# STM32-PROX.net
KiCad netlist of a schematic drawn in EAGLE
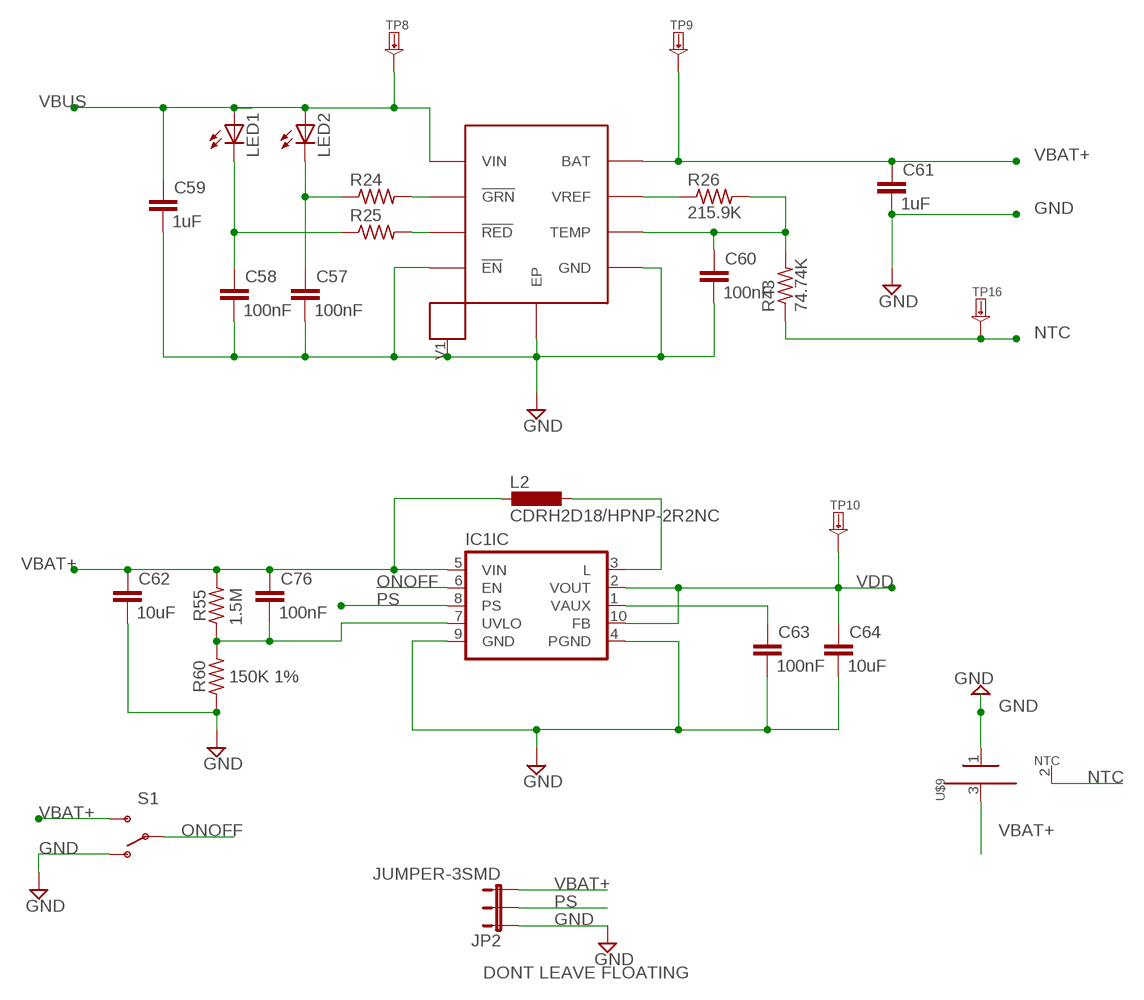
[diagram p0: schematic, sheet 1]
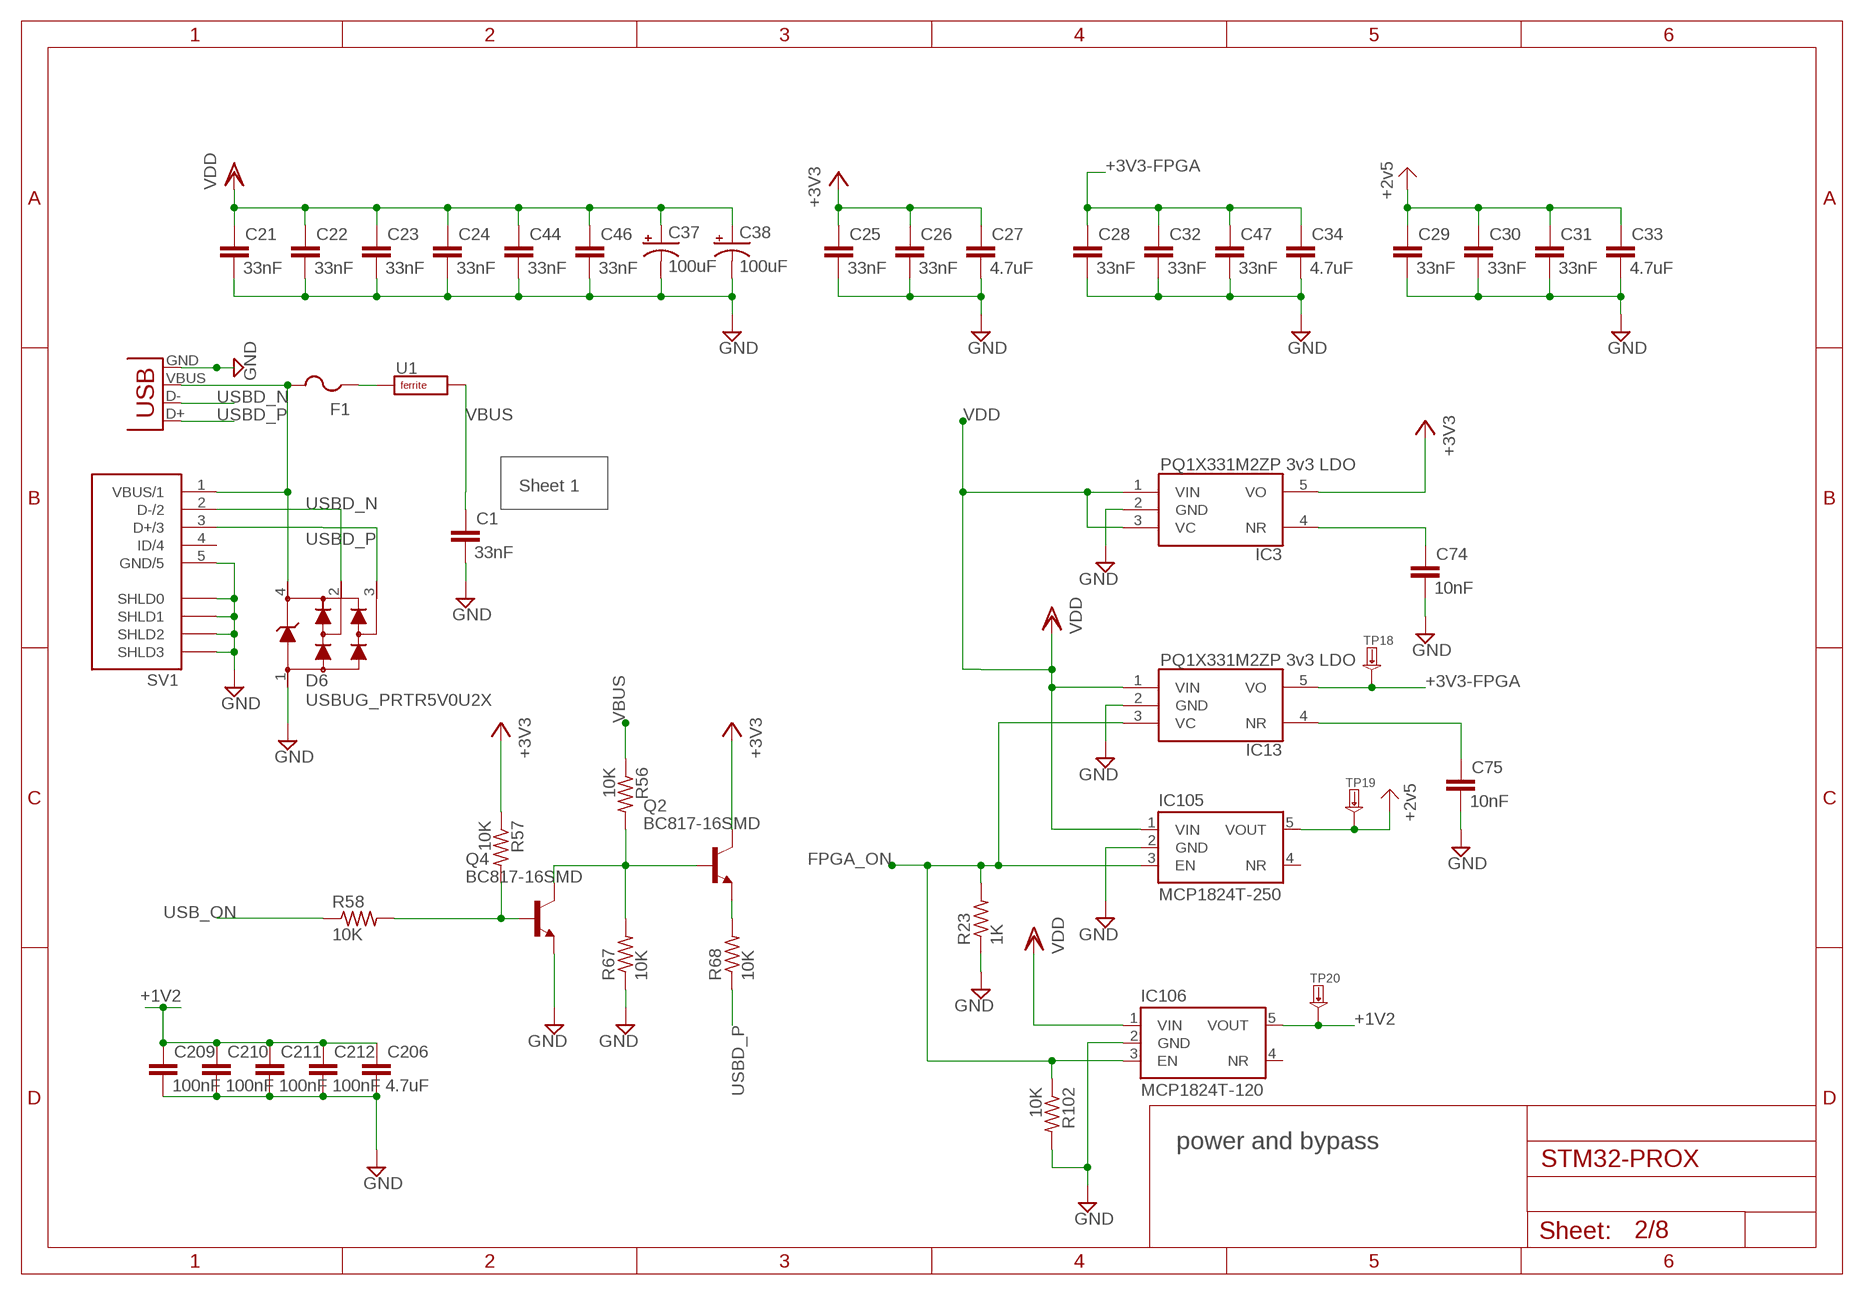
[diagram p1: schematic, sheet 2]
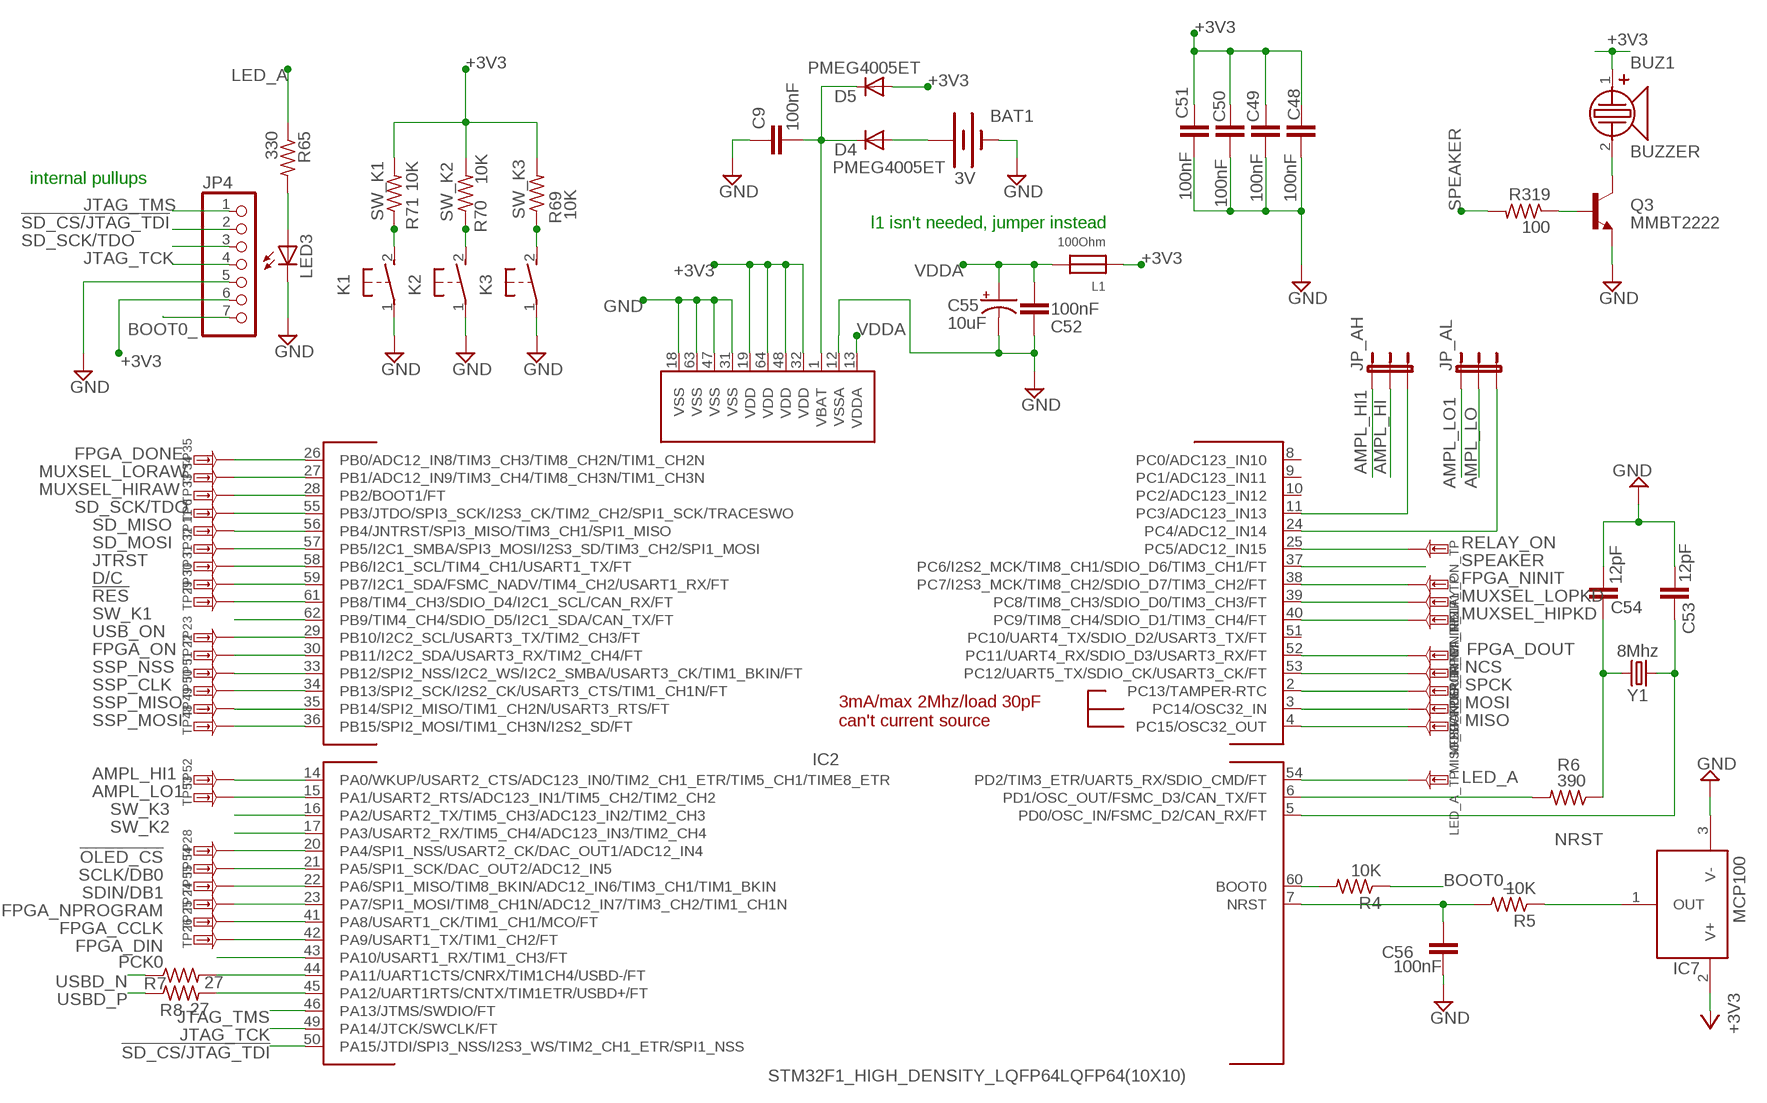
[diagram p2: schematic, sheet 3]
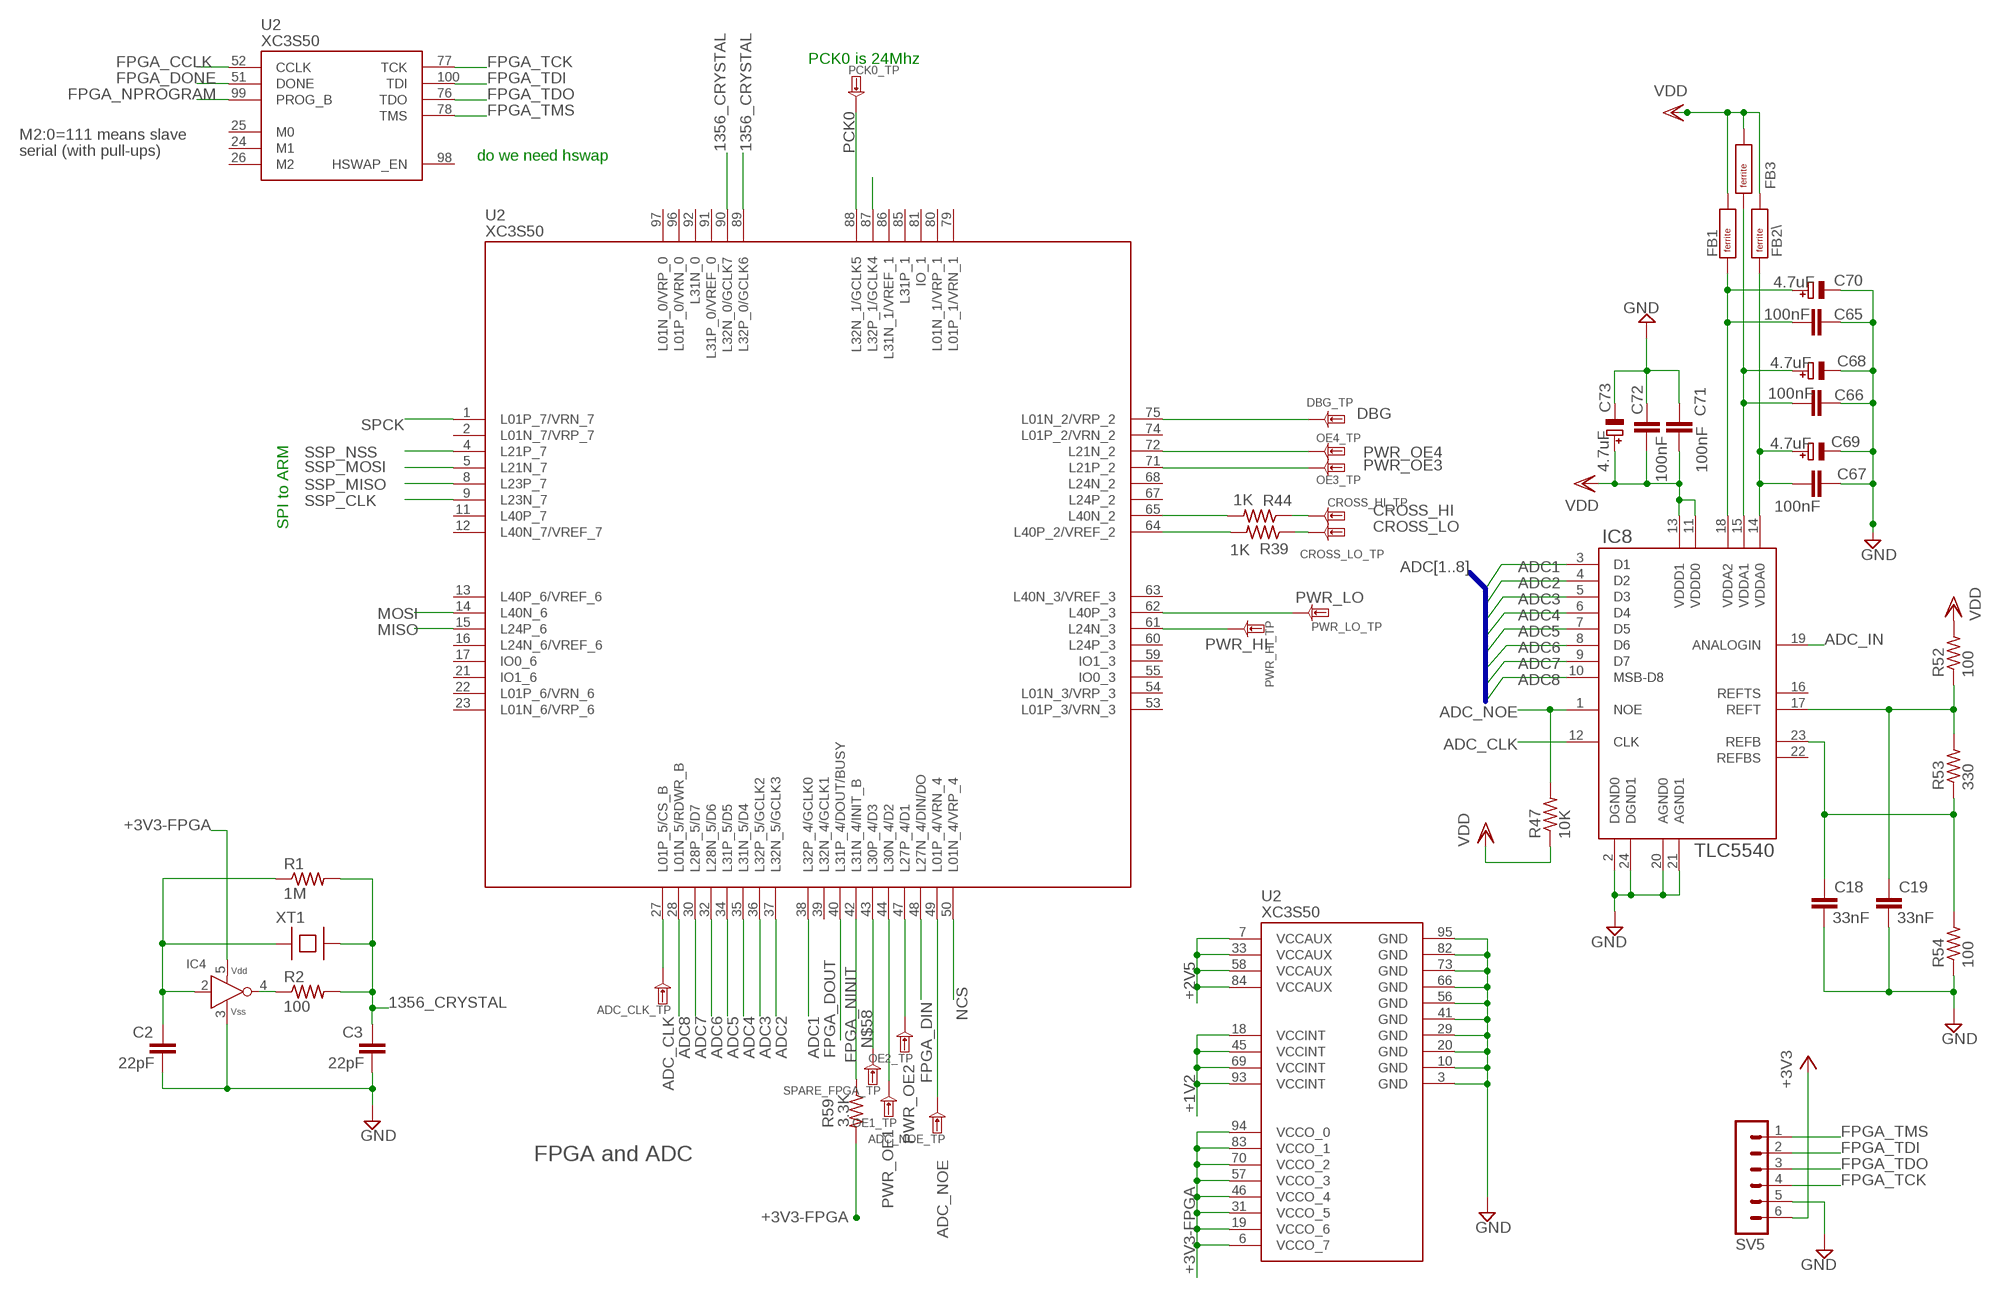
[diagram p3: schematic, sheet 4]
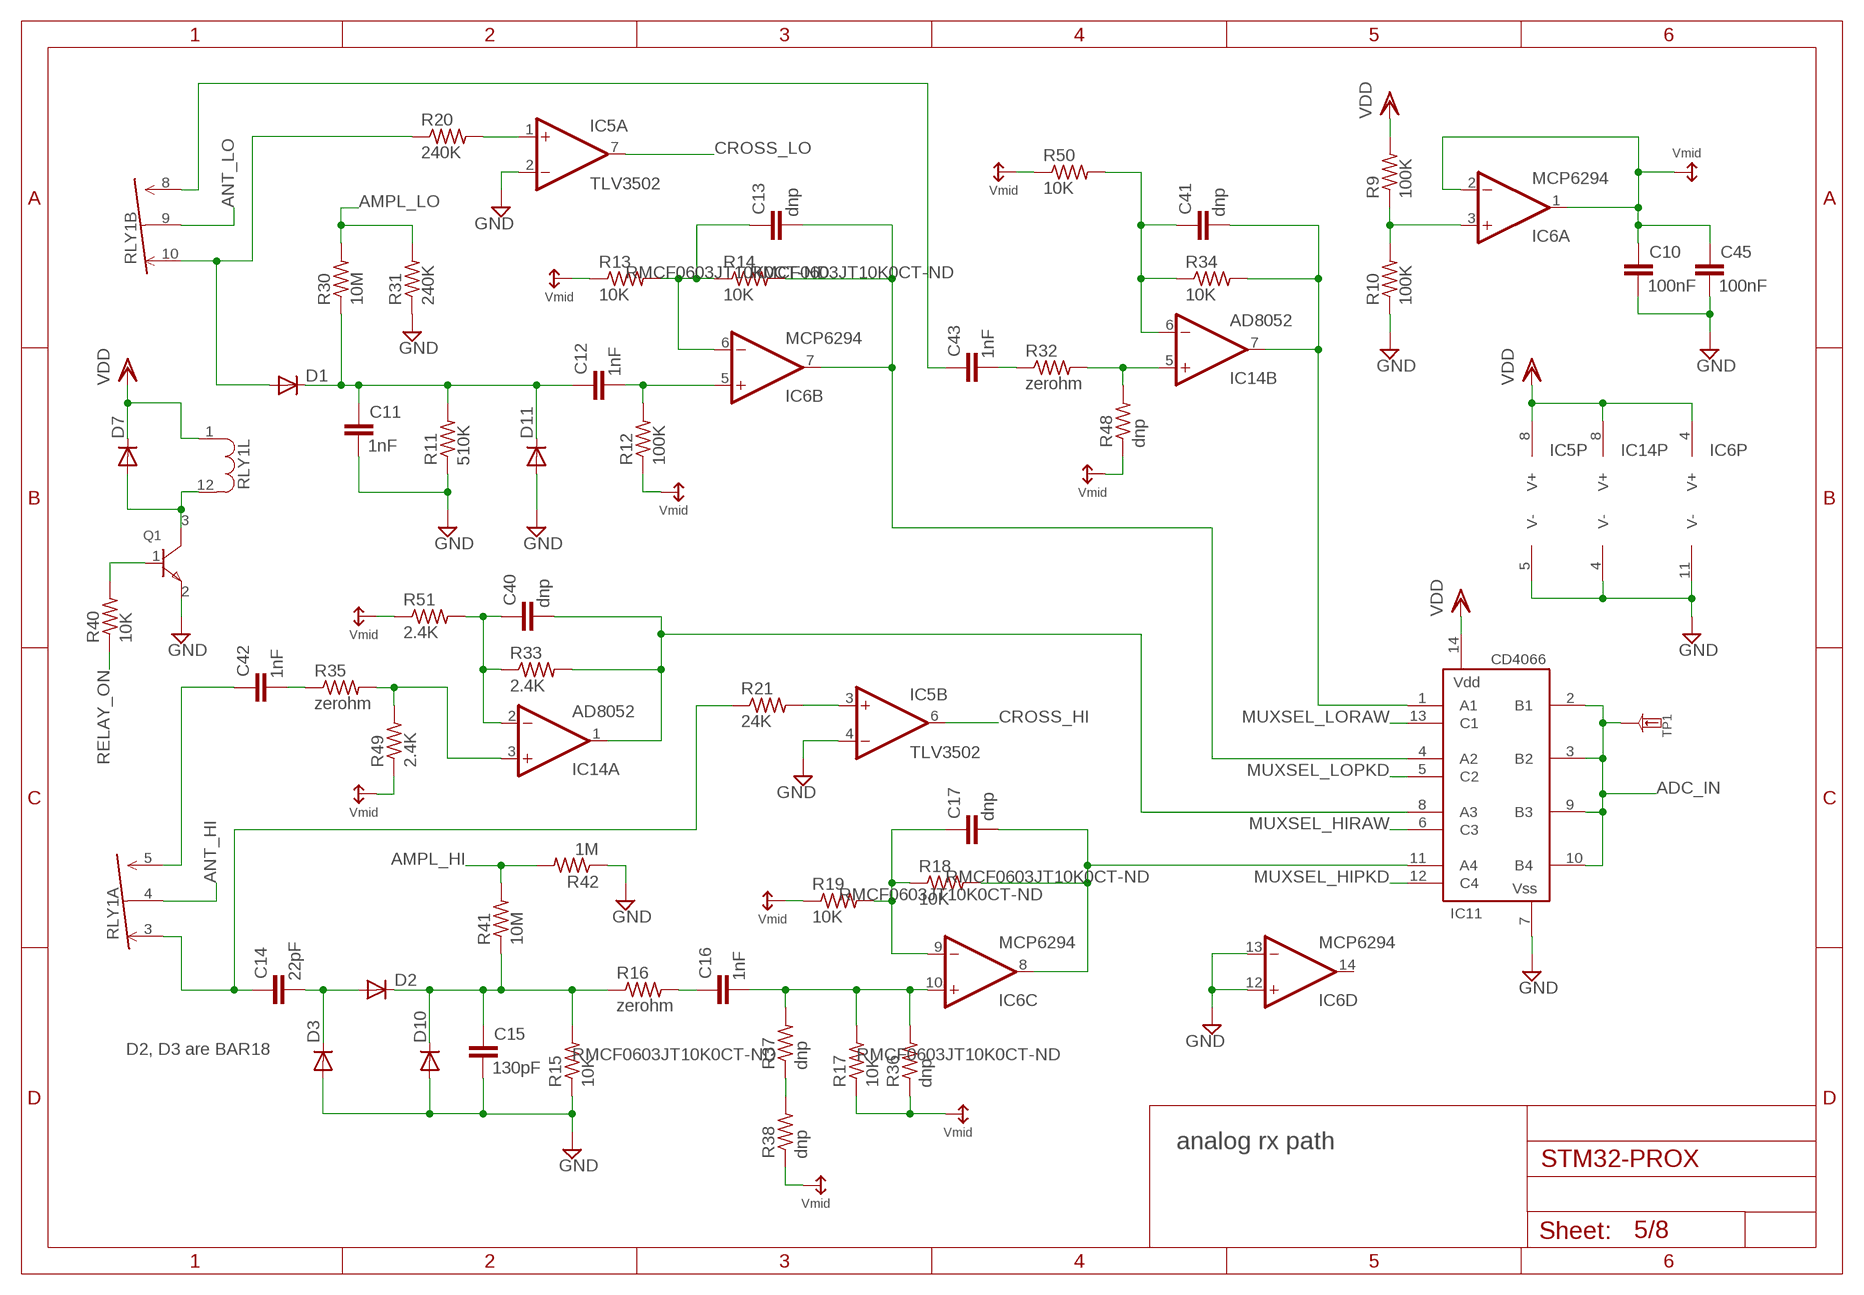
[diagram p4: schematic, sheet 5]
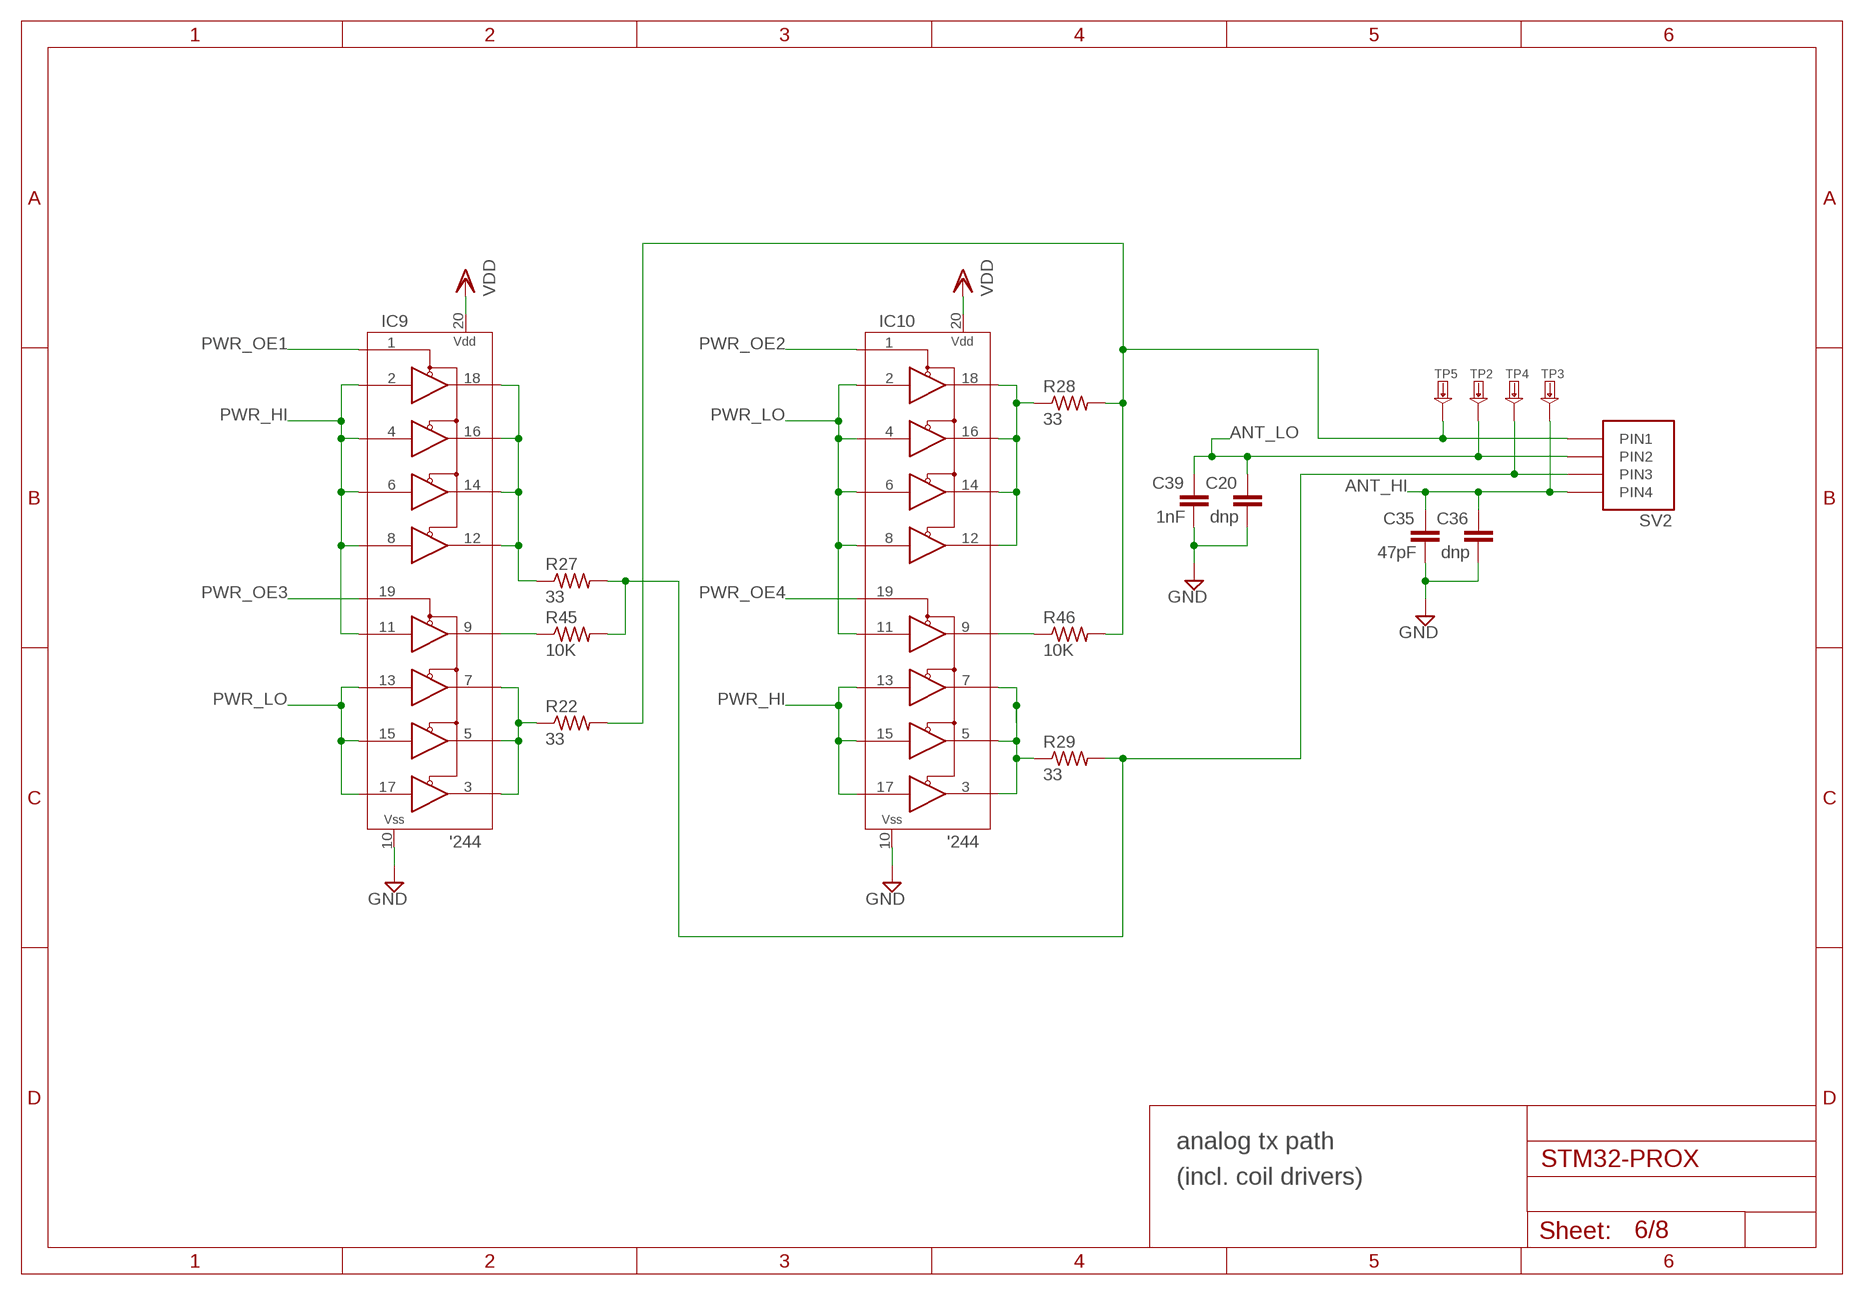
[diagram p5: schematic, sheet 6]
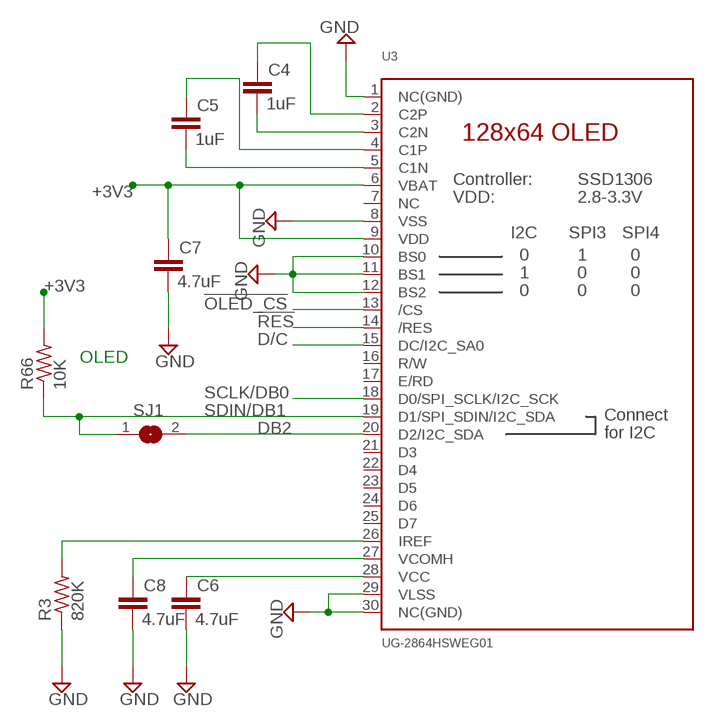
[diagram p6: schematic, sheet 7]
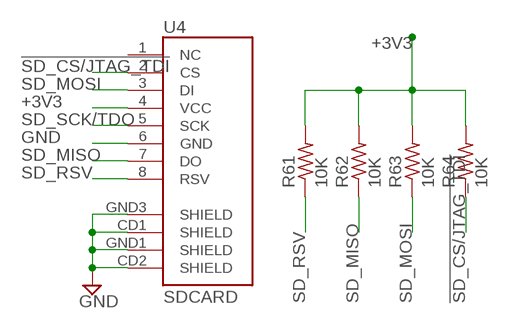
[diagram p7: schematic, sheet 8]

(export (version "E")
  (design (tool "Eeschema 10.0.6"))
  (components
    (comp (ref "C57")
      (value "100nF")
      (footprint "eagle-import:RLC_0603")
      (fields (field (name "MPN") "CL10B104KO8NNNC"))
      (libsource (lib "eagle-import") (part "CAPACITORRLC_0603"))
    )
    (comp (ref "C58")
      (value "100nF")
      (footprint "eagle-import:RLC_0603")
      (fields (field (name "MPN") "CL10B104KO8NNNC"))
      (libsource (lib "eagle-import") (part "CAPACITORRLC_0603"))
    )
    (comp (ref "C59")
      (value "1uF")
      (footprint "eagle-import:RLC_0603")
      (fields (field (name "MPN") "CC0603ZRY5V7BB105"))
      (libsource (lib "eagle-import") (part "CAPACITORRLC_0603"))
    )
    (comp (ref "C60")
      (value "100nF")
      (footprint "eagle-import:RLC_0603")
      (fields (field (name "MPN") "CL10B104KO8NNNC"))
      (libsource (lib "eagle-import") (part "CAPACITORRLC_0603"))
    )
    (comp (ref "C61")
      (value "1uF")
      (footprint "eagle-import:RLC_0603")
      (fields (field (name "MPN") "CC0603ZRY5V7BB105"))
      (libsource (lib "eagle-import") (part "CAPACITORRLC_0603"))
    )
    (comp (ref "C62")
      (value "10uF")
      (footprint "eagle-import:RLC_0603")
      (fields (field (name "MPN") "C1608X5R1C106M080AB"))
      (libsource (lib "eagle-import") (part "CAPACITORRLC_0603"))
    )
    (comp (ref "C63")
      (value "100nF")
      (footprint "eagle-import:RLC_0603")
      (fields (field (name "MPN") "CL10B104KO8NNNC"))
      (libsource (lib "eagle-import") (part "CAPACITORRLC_0603"))
    )
    (comp (ref "C64")
      (value "10uF")
      (footprint "eagle-import:RLC_0603")
      (fields (field (name "MPN") "C1608X5R1C106M080AB"))
      (libsource (lib "eagle-import") (part "CAPACITORRLC_0603"))
    )
    (comp (ref "C76")
      (value "100nF")
      (footprint "eagle-import:RLC_0603")
      (fields (field (name "MPN") "CL10B104KO8NNNC"))
      (libsource (lib "eagle-import") (part "CAPACITORRLC_0603"))
    )
    (comp (ref "IC1")
      (value "IC_TPS6120XQFN10")
      (footprint "eagle-import:QFN-10")
      (fields (field (name "MPN") "TPS61202DRCT"))
      (libsource (lib "eagle-import") (part "IC_TPS6120XQFN10"))
    )
    (comp (ref "JP2")
      (value "JUMPER-3SMD")
      (footprint "eagle-import:SJ_3")
      (fields (field (name "MPN") "NONE"))
      (libsource (lib "eagle-import") (part "JUMPER-3SMD"))
    )
    (comp (ref "L2")
      (value "CDRH2D18/HPNP-2R2NC")
      (footprint "eagle-import:CDRH2D18")
      (libsource (lib "eagle-import") (part "CDRH2D18"))
    )
    (comp (ref "LED1")
      (value "LED_LEDSML0603")
      (footprint "eagle-import:LED_SML0603")
      (fields (field (name "MF") "LG Q971-KN-1"))
      (libsource (lib "eagle-import") (part "LED_LEDSML0603"))
    )
    (comp (ref "LED2")
      (value "LED_LEDSML0603")
      (footprint "eagle-import:LED_SML0603")
      (fields (field (name "MF") "LS Q971-KN-1"))
      (libsource (lib "eagle-import") (part "LED_LEDSML0603"))
    )
    (comp (ref "R24")
      (value "RESISTORRLC_0603")
      (footprint "eagle-import:RLC_0603@1")
      (libsource (lib "eagle-import") (part "RESISTORRLC_0603"))
    )
    (comp (ref "R25")
      (value "RESISTORRLC_0603")
      (footprint "eagle-import:RLC_0603@1")
      (libsource (lib "eagle-import") (part "RESISTORRLC_0603"))
    )
    (comp (ref "R26")
      (value "215.9K")
      (footprint "eagle-import:RLC_0603@1")
      (fields (field (name "MPN") "CRCW0603215KFKEA"))
      (libsource (lib "eagle-import") (part "RESISTORRLC_0603"))
    )
    (comp (ref "R43")
      (value "74.74K")
      (footprint "eagle-import:RLC_0603@1")
      (fields (field (name "MPN") "RMCF0603JT75K0"))
      (libsource (lib "eagle-import") (part "RESISTORRLC_0603"))
    )
    (comp (ref "R55")
      (value "1.5M")
      (footprint "eagle-import:RLC_0603@1")
      (fields (field (name "MPN") "ESR03EZPJ155") (field (name "TOLERANCE") "5%"))
      (libsource (lib "eagle-import") (part "RESISTORRLC_0603"))
    )
    (comp (ref "R60")
      (value "150K 1%")
      (footprint "eagle-import:RLC_0603@1")
      (fields (field (name "MPN") "ESR03EZPF1503") (field (name "TOLERANCE") "1%"))
      (libsource (lib "eagle-import") (part "RESISTORRLC_0603"))
    )
    (comp (ref "S1")
      (value "SWITCH-SPDT-SMD-A")
      (footprint "eagle-import:SWITCH-SPST-SMD-A")
      (libsource (lib "eagle-import") (part "SWITCH-SPDT-SMD-A"))
    )
    (comp (ref "TP8")
      (value "TESTPAD0.7MM-ROUND-DRILLED")
      (footprint "eagle-import:TESTPAD-PTH-0.7MM")
      (fields (field (name "MPN") "NONE"))
      (libsource (lib "eagle-import") (part "TESTPAD0.7MM-ROUND-DRILLED"))
    )
    (comp (ref "TP9")
      (value "TESTPADKEYSTONE-SMD")
      (footprint "eagle-import:--MERGED_KEYSTONE-SMD-TESTPOINT-5015")
      (fields (field (name "MPN") "NONE"))
      (libsource (lib "eagle-import") (part "--MERGED_TESTPADKEYSTONE-SMD"))
    )
    (comp (ref "TP10")
      (value "TESTPADKEYSTONE-SMD")
      (footprint "eagle-import:--MERGED_KEYSTONE-SMD-TESTPOINT-5015")
      (fields (field (name "MPN") "NONE"))
      (libsource (lib "eagle-import") (part "--MERGED_TESTPADKEYSTONE-SMD"))
    )
    (comp (ref "TP16")
      (value "TESTPAD")
      (footprint "eagle-import:SMD-TESTPOINT")
      (libsource (lib "eagle-import") (part "TESTPAD"))
    )
    (comp (ref "U$7")
      (value "MC34674")
      (footprint "eagle-import:UDFN-EP")
      (fields
        (field (name "DIGIKEY") "MC34674AEPR2TR-ND")
        (field (name "MF") "MC34674AEPR2")
        (field (name "MOUSER") "841-MC34674AEPR2")
        (field (name "MPN") "MC34674AEPR2")
        (field (name "OC_NEWARK") "unknown")
        (field (name "PARTNO") "MC34674AEPR2")
      )
      (libsource (lib "eagle-import") (part "MC34674"))
    )
    (comp (ref "U$9")
      (value "BATT")
      (footprint "eagle-import:BATT")
      (fields (field (name "MF") "MC34674AEPR2"))
      (libsource (lib "eagle-import") (part "BATT"))
    )
    (comp (ref "C1")
      (value "33nF")
      (footprint "eagle-import:RLC_0603")
      (fields (field (name "MPN") "CC0603KRX7R9BB333"))
      (libsource (lib "eagle-import") (part "CAPACITORRLC_0603"))
    )
    (comp (ref "C21")
      (value "33nF")
      (footprint "eagle-import:RLC_0603")
      (fields (field (name "MPN") "CC0603KRX7R9BB333"))
      (libsource (lib "eagle-import") (part "CAPACITORRLC_0603"))
    )
    (comp (ref "C22")
      (value "33nF")
      (footprint "eagle-import:RLC_0603")
      (fields (field (name "MPN") "CC0603KRX7R9BB333"))
      (libsource (lib "eagle-import") (part "CAPACITORRLC_0603"))
    )
    (comp (ref "C23")
      (value "33nF")
      (footprint "eagle-import:RLC_0603")
      (fields (field (name "MPN") "CC0603KRX7R9BB333"))
      (libsource (lib "eagle-import") (part "CAPACITORRLC_0603"))
    )
    (comp (ref "C24")
      (value "33nF")
      (footprint "eagle-import:RLC_0603")
      (fields (field (name "MPN") "CC0603KRX7R9BB333"))
      (libsource (lib "eagle-import") (part "CAPACITORRLC_0603"))
    )
    (comp (ref "C25")
      (value "33nF")
      (footprint "eagle-import:RLC_0603")
      (fields (field (name "MPN") "CC0603KRX7R9BB333"))
      (libsource (lib "eagle-import") (part "CAPACITORRLC_0603"))
    )
    (comp (ref "C26")
      (value "33nF")
      (footprint "eagle-import:RLC_0603")
      (fields (field (name "MPN") "CC0603KRX7R9BB333"))
      (libsource (lib "eagle-import") (part "CAPACITORRLC_0603"))
    )
    (comp (ref "C27")
      (value "4.7uF")
      (footprint "eagle-import:RLC_1210")
      (fields (field (name "MPN") "CL32B475KOINNNE"))
      (libsource (lib "eagle-import") (part "CAPACITOR1210"))
    )
    (comp (ref "C28")
      (value "33nF")
      (footprint "eagle-import:RLC_0603")
      (fields (field (name "MPN") "CC0603KRX7R9BB333"))
      (libsource (lib "eagle-import") (part "CAPACITORRLC_0603"))
    )
    (comp (ref "C29")
      (value "33nF")
      (footprint "eagle-import:RLC_0603")
      (fields (field (name "MPN") "CC0603KRX7R9BB333"))
      (libsource (lib "eagle-import") (part "CAPACITORRLC_0603"))
    )
    (comp (ref "C30")
      (value "33nF")
      (footprint "eagle-import:RLC_0603")
      (fields (field (name "MPN") "CC0603KRX7R9BB333"))
      (libsource (lib "eagle-import") (part "CAPACITORRLC_0603"))
    )
    (comp (ref "C31")
      (value "33nF")
      (footprint "eagle-import:RLC_0603")
      (fields (field (name "MPN") "CC0603KRX7R9BB333"))
      (libsource (lib "eagle-import") (part "CAPACITORRLC_0603"))
    )
    (comp (ref "C32")
      (value "33nF")
      (footprint "eagle-import:RLC_0603")
      (fields (field (name "MPN") "CC0603KRX7R9BB333"))
      (libsource (lib "eagle-import") (part "CAPACITORRLC_0603"))
    )
    (comp (ref "C33")
      (value "4.7uF")
      (footprint "eagle-import:RLC_1210")
      (fields (field (name "MPN") "CL32B475KOINNNE"))
      (libsource (lib "eagle-import") (part "CAPACITOR1210"))
    )
    (comp (ref "C34")
      (value "4.7uF")
      (footprint "eagle-import:RLC_1210")
      (fields (field (name "MPN") "CL32B475KOINNNE"))
      (libsource (lib "eagle-import") (part "CAPACITOR1210"))
    )
    (comp (ref "C37")
      (value "100uF")
      (footprint "eagle-import:D_7343-31R")
      (fields (field (name "MPN") "T491D107K010AT"))
      (libsource (lib "eagle-import") (part "CPOL-USD/7343-31R"))
    )
    (comp (ref "C38")
      (value "100uF")
      (footprint "eagle-import:D_7343-31R")
      (fields (field (name "MPN") "T491D107K010AT"))
      (libsource (lib "eagle-import") (part "CPOL-USD/7343-31R"))
    )
    (comp (ref "C44")
      (value "33nF")
      (footprint "eagle-import:RLC_0603")
      (fields (field (name "MPN") "CC0603KRX7R9BB333"))
      (libsource (lib "eagle-import") (part "CAPACITORRLC_0603"))
    )
    (comp (ref "C46")
      (value "33nF")
      (footprint "eagle-import:RLC_0603")
      (fields (field (name "MPN") "CC0603KRX7R9BB333"))
      (libsource (lib "eagle-import") (part "CAPACITORRLC_0603"))
    )
    (comp (ref "C47")
      (value "33nF")
      (footprint "eagle-import:RLC_0603")
      (fields (field (name "MPN") "CC0603KRX7R9BB333"))
      (libsource (lib "eagle-import") (part "CAPACITORRLC_0603"))
    )
    (comp (ref "C74")
      (value "10nF")
      (footprint "eagle-import:RLC_0603")
      (fields (field (name "MPN") "CC0603KRX7R9BB333"))
      (libsource (lib "eagle-import") (part "CAPACITORRLC_0603"))
    )
    (comp (ref "C75")
      (value "10nF")
      (footprint "eagle-import:RLC_0603")
      (fields (field (name "MPN") "CC0603KRX7R9BB333"))
      (libsource (lib "eagle-import") (part "CAPACITORRLC_0603"))
    )
    (comp (ref "C206")
      (value "4.7uF")
      (footprint "eagle-import:RLC_0603")
      (fields (field (name "MPN") "EMK107ABJ475KA-T"))
      (libsource (lib "eagle-import") (part "CAPACITORRLC_0603"))
    )
    (comp (ref "C209")
      (value "100nF")
      (footprint "eagle-import:RLC_0603")
      (fields (field (name "MPN") "CL10B104KO8NNNC"))
      (libsource (lib "eagle-import") (part "CAPACITORRLC_0603"))
    )
    (comp (ref "C210")
      (value "100nF")
      (footprint "eagle-import:RLC_0603")
      (fields (field (name "MPN") "CL10B104KO8NNNC"))
      (libsource (lib "eagle-import") (part "CAPACITORRLC_0603"))
    )
    (comp (ref "C211")
      (value "100nF")
      (footprint "eagle-import:RLC_0603")
      (fields (field (name "MPN") "CL10B104KO8NNNC"))
      (libsource (lib "eagle-import") (part "CAPACITORRLC_0603"))
    )
    (comp (ref "C212")
      (value "100nF")
      (footprint "eagle-import:RLC_0603")
      (fields (field (name "MPN") "CL10B104KO8NNNC"))
      (libsource (lib "eagle-import") (part "CAPACITORRLC_0603"))
    )
    (comp (ref "D6")
      (value "USBUG_PRTR5V0U2X")
      (footprint "eagle-import:USBUG_SOT143B")
      (libsource (lib "eagle-import") (part "USBUG_PRTR5V0U2X"))
    )
    (comp (ref "F1")
      (value "PTCFUSE-1812")
      (footprint "eagle-import:1812")
      (fields (field (name "MPN") "MICROSMD050F-2"))
      (libsource (lib "eagle-import") (part "PTCFUSE-1812"))
    )
    (comp (ref "IC3")
      (value "PQ1X331M2ZP-3V3-LDO-SOT-23-5")
      (footprint "eagle-import:SOT-23-5")
      (fields (field (name "MPN") "LP2985-33DBVR"))
      (libsource (lib "eagle-import") (part "PQ1X331M2ZP-3V3-LDO-SOT-23-5"))
    )
    (comp (ref "IC13")
      (value "PQ1X331M2ZP-3V3-LDO-SOT-23-5")
      (footprint "eagle-import:SOT-23-5")
      (fields (field (name "MPN") "LP2985-33DBVR"))
      (libsource (lib "eagle-import") (part "PQ1X331M2ZP-3V3-LDO-SOT-23-5"))
    )
    (comp (ref "IC105")
      (value "MCP1824T-250")
      (footprint "eagle-import:SOT-23-5")
      (fields (field (name "MPN") "MCP1824T-2502E/OT"))
      (libsource (lib "eagle-import") (part "TPS79925"))
    )
    (comp (ref "IC106")
      (value "MCP1824T-120")
      (footprint "eagle-import:SOT-23-5")
      (fields (field (name "MPN") "MCP1824T-1202E/OT"))
      (libsource (lib "eagle-import") (part "TPS79912"))
    )
    (comp (ref "Q2")
      (value "BC817-16SMD")
      (footprint "eagle-import:SOT23-BEC")
      (libsource (lib "eagle-import") (part "BC817SMD-16"))
    )
    (comp (ref "Q4")
      (value "BC817-16SMD")
      (footprint "eagle-import:SOT23-BEC")
      (libsource (lib "eagle-import") (part "BC817SMD-16"))
    )
    (comp (ref "R23")
      (value "1K")
      (footprint "eagle-import:RLC_0603@1")
      (fields (field (name "MPN") "RMCF0603JT1K00"))
      (libsource (lib "eagle-import") (part "RESISTORRLC_0603"))
    )
    (comp (ref "R56")
      (value "10K")
      (footprint "eagle-import:RLC_0603@1")
      (fields (field (name "MPN") "RMCF0603JT10K0"))
      (libsource (lib "eagle-import") (part "RESISTORRLC_0603"))
    )
    (comp (ref "R57")
      (value "10K")
      (footprint "eagle-import:RLC_0603@1")
      (fields (field (name "MPN") "RMCF0603JT10K0"))
      (libsource (lib "eagle-import") (part "RESISTORRLC_0603"))
    )
    (comp (ref "R58")
      (value "10K")
      (footprint "eagle-import:RLC_0603@1")
      (fields (field (name "MPN") "RMCF0603JT10K0"))
      (libsource (lib "eagle-import") (part "RESISTORRLC_0603"))
    )
    (comp (ref "R67")
      (value "10K")
      (footprint "eagle-import:RLC_0603@1")
      (fields (field (name "MPN") "RMCF0603JT10K0"))
      (libsource (lib "eagle-import") (part "RESISTORRLC_0603"))
    )
    (comp (ref "R68")
      (value "10K")
      (footprint "eagle-import:RLC_0603@1")
      (fields (field (name "MPN") "RMCF0603JT10K0"))
      (libsource (lib "eagle-import") (part "RESISTORRLC_0603"))
    )
    (comp (ref "R102")
      (value "10K")
      (footprint "eagle-import:RLC_0603@1")
      (fields (field (name "MPN") "RMCF0603JT10K0"))
      (libsource (lib "eagle-import") (part "RESISTORRLC_0603"))
    )
    (comp (ref "SV1")
      (value "USB-MINIB")
      (footprint "eagle-import:USB-MINIB-SMD")
      (libsource (lib "eagle-import") (part "USB-MINIB"))
    )
    (comp (ref "TP18")
      (value "TESTPAD")
      (footprint "eagle-import:SMD-TESTPOINT")
      (libsource (lib "eagle-import") (part "TESTPAD"))
    )
    (comp (ref "TP19")
      (value "TESTPAD")
      (footprint "eagle-import:SMD-TESTPOINT")
      (libsource (lib "eagle-import") (part "TESTPAD"))
    )
    (comp (ref "TP20")
      (value "TESTPAD")
      (footprint "eagle-import:SMD-TESTPOINT")
      (libsource (lib "eagle-import") (part "TESTPAD"))
    )
    (comp (ref "U1")
      (value "FERRITE0805")
      (footprint "eagle-import:RLC_0805")
      (fields (field (name "MF") "MPZ2012S300A"))
      (libsource (lib "eagle-import") (part "FERRITE0805"))
    )
    (comp (ref "USB-MICRO")
      (value "USB-MICROB")
      (footprint "eagle-import:USB-MICROB")
      (fields (field (name "MF") "1981568-1"))
      (libsource (lib "eagle-import") (part "USB-MICROB"))
    )
    (comp (ref "C4")
      (value "1uF")
      (footprint "eagle-import:RLC_0603")
      (fields (field (name "MPN") "CC0805ZRY5V8BB105"))
      (libsource (lib "eagle-import") (part "CAPACITORRLC_0603"))
    )
    (comp (ref "C5")
      (value "1uF")
      (footprint "eagle-import:RLC_0603")
      (fields (field (name "MPN") "CC0805ZRY5V8BB105"))
      (libsource (lib "eagle-import") (part "CAPACITORRLC_0603"))
    )
    (comp (ref "C6")
      (value "4.7uF")
      (footprint "eagle-import:RLC_0603")
      (fields (field (name "MPN") "CL21A475KOFNNNE"))
      (libsource (lib "eagle-import") (part "CAPACITORRLC_0603"))
    )
    (comp (ref "C7")
      (value "4.7uF")
      (footprint "eagle-import:RLC_0603")
      (fields (field (name "MPN") "CL21A475KOFNNNE"))
      (libsource (lib "eagle-import") (part "CAPACITORRLC_0603"))
    )
    (comp (ref "C8")
      (value "4.7uF")
      (footprint "eagle-import:RLC_0603")
      (fields (field (name "MPN") "CL21A475KOFNNNE"))
      (libsource (lib "eagle-import") (part "CAPACITORRLC_0603"))
    )
    (comp (ref "R3")
      (value "820K")
      (footprint "eagle-import:RLC_0603@1")
      (fields (field (name "MPN") "RC0603JR-07820KL"))
      (libsource (lib "eagle-import") (part "RESISTORRLC_0603"))
    )
    (comp (ref "R66")
      (value "10K")
      (footprint "eagle-import:RLC_0603@1")
      (fields (field (name "MPN") "RC0603JR-07820KL"))
      (libsource (lib "eagle-import") (part "RESISTORRLC_0603"))
    )
    (comp (ref "SJ1")
      (value "SOLDERJUMPERREFLOW")
      (footprint "eagle-import:SOLDERJUMPER_REFLOW")
      (fields (field (name "MPN") "NONE"))
      (libsource (lib "eagle-import") (part "SOLDERJUMPERREFLOW"))
    )
    (comp (ref "U3")
      (value "UG-2864HSWEG01")
      (footprint "eagle-import:MICROBUILDER_UG-2864HSWEG01_0.96IN_WRAPAROUND")
      (libsource (lib "eagle-import") (part "MICROBUILDER_DISP_OLED_UG-2864HSWEG010.96{dblquote}"))
    )
    (comp (ref "ADC_CLK_TP")
      (value "TESTPAD")
      (footprint "eagle-import:SMD-TESTPOINT")
      (libsource (lib "eagle-import") (part "TESTPAD"))
    )
    (comp (ref "ADC_NOE_TP")
      (value "TESTPAD")
      (footprint "eagle-import:SMD-TESTPOINT")
      (libsource (lib "eagle-import") (part "TESTPAD"))
    )
    (comp (ref "C2")
      (value "22pF")
      (footprint "eagle-import:RLC_0603")
      (fields (field (name "MPN") "C1608C0G1H220J080AA"))
      (libsource (lib "eagle-import") (part "CAPACITORRLC_0603"))
    )
    (comp (ref "C3")
      (value "22pF")
      (footprint "eagle-import:RLC_0603")
      (fields (field (name "MPN") "C1608C0G1H220J080AA"))
      (libsource (lib "eagle-import") (part "CAPACITORRLC_0603"))
    )
    (comp (ref "C18")
      (value "33nF")
      (footprint "eagle-import:RLC_0603")
      (fields (field (name "MPN") "CC0603KRX7R9BB333"))
      (libsource (lib "eagle-import") (part "CAPACITORRLC_0603"))
    )
    (comp (ref "C19")
      (value "33nF")
      (footprint "eagle-import:RLC_0603")
      (fields (field (name "MPN") "CC0603KRX7R9BB333"))
      (libsource (lib "eagle-import") (part "CAPACITORRLC_0603"))
    )
    (comp (ref "C65")
      (value "100nF")
      (footprint "eagle-import:RLC_0603")
      (fields (field (name "MPN") "CC0603KRX7R9BB333"))
      (libsource (lib "eagle-import") (part "CAPACITORRLC_0603"))
    )
    (comp (ref "C66")
      (value "100nF")
      (footprint "eagle-import:RLC_0603")
      (fields (field (name "MPN") "CC0603KRX7R9BB333"))
      (libsource (lib "eagle-import") (part "CAPACITORRLC_0603"))
    )
    (comp (ref "C67")
      (value "100nF")
      (footprint "eagle-import:RLC_0603")
      (fields (field (name "MPN") "CC0603KRX7R9BB333"))
      (libsource (lib "eagle-import") (part "CAPACITORRLC_0603"))
    )
    (comp (ref "C68")
      (value "4.7uF")
      (footprint "eagle-import:EIA3216-18_A-R")
      (libsource (lib "eagle-import") (part "CAP_TANTALUMA/3216_REFLOW"))
    )
    (comp (ref "C69")
      (value "4.7uF")
      (footprint "eagle-import:EIA3216-18_A-R")
      (libsource (lib "eagle-import") (part "CAP_TANTALUMA/3216_REFLOW"))
    )
    (comp (ref "C70")
      (value "4.7uF")
      (footprint "eagle-import:EIA3216-18_A-R")
      (libsource (lib "eagle-import") (part "CAP_TANTALUMA/3216_REFLOW"))
    )
    (comp (ref "C71")
      (value "100nF")
      (footprint "eagle-import:RLC_0603")
      (fields (field (name "MPN") "CC0603KRX7R9BB333"))
      (libsource (lib "eagle-import") (part "CAPACITORRLC_0603"))
    )
    (comp (ref "C72")
      (value "100nF")
      (footprint "eagle-import:RLC_0603")
      (fields (field (name "MPN") "CC0603KRX7R9BB333"))
      (libsource (lib "eagle-import") (part "CAPACITORRLC_0603"))
    )
    (comp (ref "C73")
      (value "4.7uF")
      (footprint "eagle-import:EIA3216-18_A-R")
      (libsource (lib "eagle-import") (part "CAP_TANTALUMA/3216_REFLOW"))
    )
    (comp (ref "CROSS_HI_TP")
      (value "TESTPAD")
      (footprint "eagle-import:SMD-TESTPOINT")
      (libsource (lib "eagle-import") (part "TESTPAD"))
    )
    (comp (ref "CROSS_LO_TP")
      (value "TESTPAD")
      (footprint "eagle-import:SMD-TESTPOINT")
      (libsource (lib "eagle-import") (part "TESTPAD"))
    )
    (comp (ref "DBG_TP")
      (value "TESTPAD")
      (footprint "eagle-import:SMD-TESTPOINT")
      (libsource (lib "eagle-import") (part "TESTPAD"))
    )
    (comp (ref "FB1")
      (value "FERRITERLC_0603")
      (footprint "eagle-import:RLC_0603@1")
      (fields (field (name "PARTNO") "BLM31PG601SN1L"))
      (libsource (lib "eagle-import") (part "FERRITERLC_0603"))
    )
    (comp (ref "FB2\\")
      (value "FERRITERLC_0603")
      (footprint "eagle-import:RLC_0603@1")
      (fields (field (name "PARTNO") "BLM31PG601SN1L"))
      (libsource (lib "eagle-import") (part "FERRITERLC_0603"))
    )
    (comp (ref "FB3")
      (value "FERRITERLC_0603")
      (footprint "eagle-import:RLC_0603@1")
      (fields (field (name "PARTNO") "BLM31PG601SN1L"))
      (libsource (lib "eagle-import") (part "FERRITERLC_0603"))
    )
    (comp (ref "IC4")
      (value "HCU-INVERTER")
      (footprint "eagle-import:SMV-5")
      (fields (field (name "MF") "NC7SZ04M5X"))
      (libsource (lib "eagle-import") (part "HCU-INVERTER"))
    )
    (comp (ref "IC8")
      (value "TLC5540")
      (footprint "eagle-import:TSSOP-24")
      (fields (field (name "MPN") "TLC5540IPW"))
      (libsource (lib "eagle-import") (part "TLC5540"))
    )
    (comp (ref "OE1_TP")
      (value "TESTPAD")
      (footprint "eagle-import:SMD-TESTPOINT")
      (libsource (lib "eagle-import") (part "TESTPAD"))
    )
    (comp (ref "OE2_TP")
      (value "TESTPAD")
      (footprint "eagle-import:SMD-TESTPOINT")
      (libsource (lib "eagle-import") (part "TESTPAD"))
    )
    (comp (ref "OE3_TP")
      (value "TESTPAD")
      (footprint "eagle-import:SMD-TESTPOINT")
      (libsource (lib "eagle-import") (part "TESTPAD"))
    )
    (comp (ref "OE4_TP")
      (value "TESTPAD")
      (footprint "eagle-import:SMD-TESTPOINT")
      (libsource (lib "eagle-import") (part "TESTPAD"))
    )
    (comp (ref "PCK0_TP")
      (value "TESTPAD")
      (footprint "eagle-import:SMD-TESTPOINT")
      (libsource (lib "eagle-import") (part "TESTPAD"))
    )
    (comp (ref "PWR_HI_TP")
      (value "TESTPAD")
      (footprint "eagle-import:SMD-TESTPOINT")
      (libsource (lib "eagle-import") (part "TESTPAD"))
    )
    (comp (ref "PWR_LO_TP")
      (value "TESTPAD")
      (footprint "eagle-import:SMD-TESTPOINT")
      (libsource (lib "eagle-import") (part "TESTPAD"))
    )
    (comp (ref "R1")
      (value "1M")
      (footprint "eagle-import:RLC_0603@1")
      (fields (field (name "MPN") "RC0603JR-071ML"))
      (libsource (lib "eagle-import") (part "RESISTORRLC_0603"))
    )
    (comp (ref "R2")
      (value "100")
      (footprint "eagle-import:RLC_0603@1")
      (fields (field (name "MPN") "RMCF0603JT100R"))
      (libsource (lib "eagle-import") (part "RESISTORRLC_0603"))
    )
    (comp (ref "R39")
      (value "1K")
      (footprint "eagle-import:RLC_0603@1")
      (fields (field (name "MPN") "RMCF0603JT1K00"))
      (libsource (lib "eagle-import") (part "RESISTORRLC_0603"))
    )
    (comp (ref "R44")
      (value "1K")
      (footprint "eagle-import:RLC_0603@1")
      (fields (field (name "MPN") "RMCF0603JT1K00"))
      (libsource (lib "eagle-import") (part "RESISTORRLC_0603"))
    )
    (comp (ref "R47")
      (value "10K")
      (footprint "eagle-import:RLC_0603@1")
      (fields (field (name "MPN") "RMCF0603JT10K0"))
      (libsource (lib "eagle-import") (part "RESISTORRLC_0603"))
    )
    (comp (ref "R52")
      (value "100")
      (footprint "eagle-import:RLC_0603@1")
      (fields (field (name "MPN") "RMCF0603JT100R"))
      (libsource (lib "eagle-import") (part "RESISTORRLC_0603"))
    )
    (comp (ref "R53")
      (value "330")
      (footprint "eagle-import:RLC_0603@1")
      (fields (field (name "MPN") "RMCF0603JT330R"))
      (libsource (lib "eagle-import") (part "RESISTORRLC_0603"))
    )
    (comp (ref "R54")
      (value "100")
      (footprint "eagle-import:RLC_0603@1")
      (fields (field (name "MPN") "RMCF0603JT100R"))
      (libsource (lib "eagle-import") (part "RESISTORRLC_0603"))
    )
    (comp (ref "R59")
      (value "3.3K")
      (footprint "eagle-import:RLC_0603@1")
      (fields (field (name "MPN") "RMCF0603JT3K30"))
      (libsource (lib "eagle-import") (part "RESISTORRLC_0603"))
    )
    (comp (ref "SPARE_FPGA_TP")
      (value "TESTPAD")
      (footprint "eagle-import:SMD-TESTPOINT")
      (libsource (lib "eagle-import") (part "TESTPAD"))
    )
    (comp (ref "SV5")
      (value "HEADER-MALE-6X1")
      (footprint "eagle-import:HEADER-MALE-6X1-0.100-UNKEYED")
      (libsource (lib "eagle-import") (part "HEADER-MALE-6X1"))
    )
    (comp (ref "U2")
      (value "XC3S50")
      (footprint "eagle-import:VQ100")
      (fields
        (field (name "MPN") "XC3S50-5VQ100C (not on bom)")
        (field (name "OC_NEWARK") "unknown")
        (field (name "PARTNO") "XC3S50-5VQ100C (not on bom)")
      )
      (libsource (lib "eagle-import") (part "XC3S50"))
    )
    (comp (ref "XT1")
      (value "XTAL-SMD-CITIZEN-CS10")
      (footprint "eagle-import:XTAL-SMD-CITIZEN-CS10")
      (fields (field (name "MF") "ABM3-13.560MHZ-B2-T"))
      (libsource (lib "eagle-import") (part "XTAL-SMD-CITIZEN-CS10"))
    )
    (comp (ref "R61")
      (value "10K")
      (footprint "eagle-import:RLC_0603@1")
      (fields (field (name "MPN") "RMCF0603JT10K0"))
      (libsource (lib "eagle-import") (part "RESISTORRLC_0603"))
    )
    (comp (ref "R62")
      (value "10K")
      (footprint "eagle-import:RLC_0603@1")
      (fields (field (name "MPN") "RMCF0603JT10K0"))
      (libsource (lib "eagle-import") (part "RESISTORRLC_0603"))
    )
    (comp (ref "R63")
      (value "10K")
      (footprint "eagle-import:RLC_0603@1")
      (fields (field (name "MPN") "RMCF0603JT10K0"))
      (libsource (lib "eagle-import") (part "RESISTORRLC_0603"))
    )
    (comp (ref "R64")
      (value "10K")
      (footprint "eagle-import:RLC_0603@1")
      (fields (field (name "MPN") "RMCF0603JT10K0"))
      (libsource (lib "eagle-import") (part "RESISTORRLC_0603"))
    )
    (comp (ref "U4")
      (value "SDCARD")
      (footprint "eagle-import:MICRO-SD-SOCKET-PP")
      (libsource (lib "eagle-import") (part "USD-SOCKETNEW"))
    )
    (comp (ref "BAT1")
      (value "3V")
      (footprint "eagle-import:NSL_SPARKFUN_BATTCON_12MM")
      (fields (field (name "MPN") "BK-885-TR"))
      (libsource (lib "eagle-import") (part "NSL_SPARKFUN_BATTERY12MM"))
    )
    (comp (ref "BUZ1")
      (value "BUZZER")
      (footprint "eagle-import:BUZZER")
      (fields (field (name "MF") "CCV-084B16"))
      (libsource (lib "eagle-import") (part "BUZZER"))
    )
    (comp (ref "C9")
      (value "100nF")
      (footprint "eagle-import:RLC_0603")
      (fields (field (name "MPN") "CL21F104ZBCNNNC"))
      (libsource (lib "eagle-import") (part "CAPACITORRLC_0603"))
    )
    (comp (ref "C48")
      (value "100nF")
      (footprint "eagle-import:RLC_0603")
      (fields (field (name "MPN") "CL21F104ZBCNNNC"))
      (libsource (lib "eagle-import") (part "CAPACITORRLC_0603"))
    )
    (comp (ref "C49")
      (value "100nF")
      (footprint "eagle-import:RLC_0603")
      (fields (field (name "MPN") "CL21F104ZBCNNNC"))
      (libsource (lib "eagle-import") (part "CAPACITORRLC_0603"))
    )
    (comp (ref "C50")
      (value "100nF")
      (footprint "eagle-import:RLC_0603")
      (fields (field (name "MPN") "CL21F104ZBCNNNC"))
      (libsource (lib "eagle-import") (part "CAPACITORRLC_0603"))
    )
    (comp (ref "C51")
      (value "100nF")
      (footprint "eagle-import:RLC_0603")
      (fields (field (name "MPN") "CL21F104ZBCNNNC"))
      (libsource (lib "eagle-import") (part "CAPACITORRLC_0603"))
    )
    (comp (ref "C52")
      (value "100nF")
      (footprint "eagle-import:RLC_0603")
      (fields (field (name "MPN") "CL21F104ZBCNNNC"))
      (libsource (lib "eagle-import") (part "CAPACITORRLC_0603"))
    )
    (comp (ref "C53")
      (value "12pF")
      (footprint "eagle-import:RLC_0603")
      (fields (field (name "MPN") "CL21C120JBANNNC"))
      (libsource (lib "eagle-import") (part "CAPACITORRLC_0603"))
    )
    (comp (ref "C54")
      (value "12pF")
      (footprint "eagle-import:RLC_0603")
      (fields (field (name "MPN") "CL21C120JBANNNC"))
      (libsource (lib "eagle-import") (part "CAPACITORRLC_0603"))
    )
    (comp (ref "C55")
      (value "10uF")
      (footprint "eagle-import:EIA3216-KIT")
      (fields (field (name "MF") "TAJA106M006RNJ"))
      (libsource (lib "eagle-import") (part "CAP_POL1206-KIT"))
    )
    (comp (ref "C56")
      (value "100nF")
      (footprint "eagle-import:RLC_0603")
      (fields (field (name "MPN") "CL21F104ZBCNNNC"))
      (libsource (lib "eagle-import") (part "CAPACITORRLC_0603"))
    )
    (comp (ref "D4")
      (value "PMEG4005ET")
      (footprint "eagle-import:SOT23-3")
      (fields (field (name "MPN") "PMEG4005ET,215"))
      (libsource (lib "eagle-import") (part "DIODESOT23"))
    )
    (comp (ref "D5")
      (value "PMEG4005ET")
      (footprint "eagle-import:SOT23-3")
      (fields (field (name "MPN") "PMEG4005ET,215"))
      (libsource (lib "eagle-import") (part "DIODESOT23"))
    )
    (comp (ref "FPGA_DOUT_TP")
      (value "TESTPAD")
      (footprint "eagle-import:SMD-TESTPOINT")
      (libsource (lib "eagle-import") (part "TESTPAD"))
    )
    (comp (ref "FPGA_NINIT_TP")
      (value "TESTPAD")
      (footprint "eagle-import:SMD-TESTPOINT")
      (libsource (lib "eagle-import") (part "TESTPAD"))
    )
    (comp (ref "FPGA_NINIT_TP1")
      (value "TESTPAD")
      (footprint "eagle-import:SMD-TESTPOINT")
      (libsource (lib "eagle-import") (part "TESTPAD"))
    )
    (comp (ref "FPGA_NINIT_TP2")
      (value "TESTPAD")
      (footprint "eagle-import:SMD-TESTPOINT")
      (libsource (lib "eagle-import") (part "TESTPAD"))
    )
    (comp (ref "IC2")
      (value "STM32F1_HIGH_DENSITY_LQFP64LQFP64(10X10)")
      (footprint "eagle-import:LQFP64A_PACKAGE")
      (libsource (lib "eagle-import") (part "STM32F1_HIGH_DENSITY_LQFP64LQFP64(10X10)"))
    )
    (comp (ref "IC7")
      (value "MCP100")
      (footprint "eagle-import:SOT23-3LEAD")
      (fields (field (name "MPN") "MCP100T-270I/TT"))
      (libsource (lib "eagle-import") (part "MCP100"))
    )
    (comp (ref "JP4")
      (value "HEADER-1X7ROUND")
      (footprint "eagle-import:1X07_ROUND")
      (libsource (lib "eagle-import") (part "HEADER-1X7ROUND"))
    )
    (comp (ref "JP_AH")
      (value "JUMPER-3SMD")
      (footprint "eagle-import:SJ_3")
      (libsource (lib "eagle-import") (part "JUMPER-3SMD"))
    )
    (comp (ref "JP_AL")
      (value "JUMPER-3SMD")
      (footprint "eagle-import:SJ_3")
      (libsource (lib "eagle-import") (part "JUMPER-3SMD"))
    )
    (comp (ref "K1")
      (value "5-XX")
      (footprint "eagle-import:B3F-5XX")
      (fields (field (name "MF") "PTS635SL50 LFS"))
      (libsource (lib "eagle-import") (part "5-XX"))
    )
    (comp (ref "K2")
      (value "5-XX")
      (footprint "eagle-import:B3F-5XX")
      (fields (field (name "MF") "PTS635SL50 LFS"))
      (libsource (lib "eagle-import") (part "5-XX"))
    )
    (comp (ref "K3")
      (value "5-XX")
      (footprint "eagle-import:B3F-5XX")
      (fields (field (name "MF") "PTS635SL50 LFS"))
      (libsource (lib "eagle-import") (part "5-XX"))
    )
    (comp (ref "L1")
      (value "100Ohm")
      (footprint "eagle-import:0603")
      (fields (field (name "MPN") "NONE"))
      (libsource (lib "eagle-import") (part "FERRITE1"))
    )
    (comp (ref "LED3")
      (value "LED_LEDSML0603")
      (footprint "eagle-import:LED_SML0603")
      (fields (field (name "MF") "LY Q976-P1S2-36"))
      (libsource (lib "eagle-import") (part "LED_LEDSML0603"))
    )
    (comp (ref "LED_A_TP")
      (value "TESTPAD")
      (footprint "eagle-import:SMD-TESTPOINT")
      (libsource (lib "eagle-import") (part "TESTPAD"))
    )
    (comp (ref "MISO_TP")
      (value "TESTPAD")
      (footprint "eagle-import:SMD-TESTPOINT")
      (libsource (lib "eagle-import") (part "TESTPAD"))
    )
    (comp (ref "MOSI_TP")
      (value "TESTPAD")
      (footprint "eagle-import:SMD-TESTPOINT")
      (libsource (lib "eagle-import") (part "TESTPAD"))
    )
    (comp (ref "NCS_TP")
      (value "TESTPAD")
      (footprint "eagle-import:SMD-TESTPOINT")
      (libsource (lib "eagle-import") (part "TESTPAD"))
    )
    (comp (ref "Q3")
      (value "MMBT2222")
      (footprint "eagle-import:SOT-23-3")
      (fields (field (name "MPN") "MMBT2222A-7-F"))
      (libsource (lib "eagle-import") (part "TRANSISTOR_NPNSOT23"))
    )
    (comp (ref "R4")
      (value "10K")
      (footprint "eagle-import:RLC_0603@1")
      (fields (field (name "DIGIKEY") "RMCF0603JT10K0CT-ND") (field (name "MPN") "RMCF0603JT10K0"))
      (libsource (lib "eagle-import") (part "RESISTORRLC_0603"))
    )
    (comp (ref "R5")
      (value "10K")
      (footprint "eagle-import:RLC_0603@1")
      (fields (field (name "DIGIKEY") "RMCF0603JT10K0CT-ND") (field (name "MPN") "RMCF0603JT10K0"))
      (libsource (lib "eagle-import") (part "RESISTORRLC_0603"))
    )
    (comp (ref "R6")
      (value "390")
      (footprint "eagle-import:RLC_0603@1")
      (fields (field (name "MPN") "RMCF0603JT390R"))
      (libsource (lib "eagle-import") (part "RESISTORRLC_0603"))
    )
    (comp (ref "R7")
      (value "27")
      (footprint "eagle-import:RLC_0603@1")
      (fields (field (name "MPN") "RMCF0603JT27R0"))
      (libsource (lib "eagle-import") (part "RESISTORRLC_0603"))
    )
    (comp (ref "R8")
      (value "27")
      (footprint "eagle-import:RLC_0603@1")
      (fields (field (name "MPN") "RMCF0603JT27R0"))
      (libsource (lib "eagle-import") (part "RESISTORRLC_0603"))
    )
    (comp (ref "R65")
      (value "330")
      (footprint "eagle-import:RLC_0603@1")
      (fields (field (name "MPN") "RMCF0603JT330R"))
      (libsource (lib "eagle-import") (part "RESISTORRLC_0603"))
    )
    (comp (ref "R69")
      (value "10K")
      (footprint "eagle-import:RLC_0603@1")
      (fields (field (name "MPN") "RMCF0603JT10K0"))
      (libsource (lib "eagle-import") (part "RESISTORRLC_0603"))
    )
    (comp (ref "R70")
      (value "10K")
      (footprint "eagle-import:RLC_0603@1")
      (fields (field (name "MPN") "RMCF0603JT10K0"))
      (libsource (lib "eagle-import") (part "RESISTORRLC_0603"))
    )
    (comp (ref "R71")
      (value "10K")
      (footprint "eagle-import:RLC_0603@1")
      (fields (field (name "MPN") "RMCF0603JT10K0"))
      (libsource (lib "eagle-import") (part "RESISTORRLC_0603"))
    )
    (comp (ref "R319")
      (value "100")
      (footprint "eagle-import:RLC_0603@1")
      (fields (field (name "MPN") "RMCF0603JT100R"))
      (libsource (lib "eagle-import") (part "RESISTORRLC_0603"))
    )
    (comp (ref "RELAY_ON_TP")
      (value "TESTPAD")
      (footprint "eagle-import:SMD-TESTPOINT")
      (libsource (lib "eagle-import") (part "TESTPAD"))
    )
    (comp (ref "SPCK_TP")
      (value "TESTPAD")
      (footprint "eagle-import:SMD-TESTPOINT")
      (libsource (lib "eagle-import") (part "TESTPAD"))
    )
    (comp (ref "TP6")
      (value "TESTPAD")
      (footprint "eagle-import:SMD-TESTPOINT")
      (libsource (lib "eagle-import") (part "TESTPAD"))
    )
    (comp (ref "TP11")
      (value "TESTPAD")
      (footprint "eagle-import:SMD-TESTPOINT")
      (libsource (lib "eagle-import") (part "TESTPAD"))
    )
    (comp (ref "TP22")
      (value "TESTPAD")
      (footprint "eagle-import:SMD-TESTPOINT")
      (libsource (lib "eagle-import") (part "TESTPAD"))
    )
    (comp (ref "TP23")
      (value "TESTPAD")
      (footprint "eagle-import:SMD-TESTPOINT")
      (libsource (lib "eagle-import") (part "TESTPAD"))
    )
    (comp (ref "TP24")
      (value "TESTPAD")
      (footprint "eagle-import:SMD-TESTPOINT")
      (libsource (lib "eagle-import") (part "TESTPAD"))
    )
    (comp (ref "TP25")
      (value "TESTPAD")
      (footprint "eagle-import:SMD-TESTPOINT")
      (libsource (lib "eagle-import") (part "TESTPAD"))
    )
    (comp (ref "TP26")
      (value "TESTPAD")
      (footprint "eagle-import:SMD-TESTPOINT")
      (libsource (lib "eagle-import") (part "TESTPAD"))
    )
    (comp (ref "TP28")
      (value "TESTPAD")
      (footprint "eagle-import:SMD-TESTPOINT")
      (libsource (lib "eagle-import") (part "TESTPAD"))
    )
    (comp (ref "TP29")
      (value "TESTPAD")
      (footprint "eagle-import:SMD-TESTPOINT")
      (libsource (lib "eagle-import") (part "TESTPAD"))
    )
    (comp (ref "TP30")
      (value "TESTPAD")
      (footprint "eagle-import:SMD-TESTPOINT")
      (libsource (lib "eagle-import") (part "TESTPAD"))
    )
    (comp (ref "TP31")
      (value "TESTPAD")
      (footprint "eagle-import:SMD-TESTPOINT")
      (libsource (lib "eagle-import") (part "TESTPAD"))
    )
    (comp (ref "TP32")
      (value "TESTPAD")
      (footprint "eagle-import:SMD-TESTPOINT")
      (libsource (lib "eagle-import") (part "TESTPAD"))
    )
    (comp (ref "TP33")
      (value "TESTPAD")
      (footprint "eagle-import:SMD-TESTPOINT")
      (libsource (lib "eagle-import") (part "TESTPAD"))
    )
    (comp (ref "TP34")
      (value "TESTPAD")
      (footprint "eagle-import:SMD-TESTPOINT")
      (libsource (lib "eagle-import") (part "TESTPAD"))
    )
    (comp (ref "TP35")
      (value "TESTPAD")
      (footprint "eagle-import:SMD-TESTPOINT")
      (libsource (lib "eagle-import") (part "TESTPAD"))
    )
    (comp (ref "TP48")
      (value "TESTPAD")
      (footprint "eagle-import:SMD-TESTPOINT")
      (libsource (lib "eagle-import") (part "TESTPAD"))
    )
    (comp (ref "TP49")
      (value "TESTPAD")
      (footprint "eagle-import:SMD-TESTPOINT")
      (libsource (lib "eagle-import") (part "TESTPAD"))
    )
    (comp (ref "TP50")
      (value "TESTPAD")
      (footprint "eagle-import:SMD-TESTPOINT")
      (libsource (lib "eagle-import") (part "TESTPAD"))
    )
    (comp (ref "TP51")
      (value "TESTPAD")
      (footprint "eagle-import:SMD-TESTPOINT")
      (libsource (lib "eagle-import") (part "TESTPAD"))
    )
    (comp (ref "TP52")
      (value "TESTPAD")
      (footprint "eagle-import:SMD-TESTPOINT")
      (libsource (lib "eagle-import") (part "TESTPAD"))
    )
    (comp (ref "TP53")
      (value "TESTPAD")
      (footprint "eagle-import:SMD-TESTPOINT")
      (libsource (lib "eagle-import") (part "TESTPAD"))
    )
    (comp (ref "TP54")
      (value "TESTPAD")
      (footprint "eagle-import:SMD-TESTPOINT")
      (libsource (lib "eagle-import") (part "TESTPAD"))
    )
    (comp (ref "TP55")
      (value "TESTPAD")
      (footprint "eagle-import:SMD-TESTPOINT")
      (libsource (lib "eagle-import") (part "TESTPAD"))
    )
    (comp (ref "Y1")
      (value "8Mhz")
      (footprint "eagle-import:CRYSTAL-TXC-7A")
      (fields (field (name "MPN") "7A-8.000MAAE-T"))
      (libsource (lib "eagle-import") (part "CRYSTALTXC-7A"))
    )
    (comp (ref "C20")
      (value "dnp")
      (footprint "eagle-import:RLC_0603")
      (libsource (lib "eagle-import") (part "CAPACITORRLC_0603"))
    )
    (comp (ref "C35")
      (value "47pF")
      (footprint "eagle-import:RLC_0603")
      (fields (field (name "MPN") "CL10C470JB8NNNC"))
      (libsource (lib "eagle-import") (part "CAPACITORRLC_0603"))
    )
    (comp (ref "C36")
      (value "dnp")
      (footprint "eagle-import:RLC_0603")
      (libsource (lib "eagle-import") (part "CAPACITORRLC_0603"))
    )
    (comp (ref "C39")
      (value "1nF")
      (footprint "eagle-import:RLC_0603")
      (fields (field (name "MPN") "GRM188R71H102KA01D"))
      (libsource (lib "eagle-import") (part "CAPACITORRLC_0603"))
    )
    (comp (ref "IC9")
      (value "74XX244")
      (footprint "eagle-import:TSSOP-20")
      (fields (field (name "MF") "74AC244TTR"))
      (libsource (lib "eagle-import") (part "74XX244-OCTAL-TRISTATE-BUFFERS"))
    )
    (comp (ref "IC10")
      (value "74XX244")
      (footprint "eagle-import:TSSOP-20")
      (fields (field (name "MF") "74AC244TTR"))
      (libsource (lib "eagle-import") (part "74XX244-OCTAL-TRISTATE-BUFFERS"))
    )
    (comp (ref "R22")
      (value "33")
      (footprint "eagle-import:RLC_0603@1")
      (fields (field (name "MPN") "RC0603JR-0733RL"))
      (libsource (lib "eagle-import") (part "RESISTORRLC_0603"))
    )
    (comp (ref "R27")
      (value "33")
      (footprint "eagle-import:RLC_0603@1")
      (fields (field (name "MPN") "RC0603JR-0733RL"))
      (libsource (lib "eagle-import") (part "RESISTORRLC_0603"))
    )
    (comp (ref "R28")
      (value "33")
      (footprint "eagle-import:RLC_0603@1")
      (fields (field (name "MPN") "RC0603JR-0733RL"))
      (libsource (lib "eagle-import") (part "RESISTORRLC_0603"))
    )
    (comp (ref "R29")
      (value "33")
      (footprint "eagle-import:RLC_0603@1")
      (fields (field (name "MPN") "RC0603JR-0733RL"))
      (libsource (lib "eagle-import") (part "RESISTORRLC_0603"))
    )
    (comp (ref "R45")
      (value "10K")
      (footprint "eagle-import:RLC_0603@1")
      (fields (field (name "MPN") "RMCF0603JT10K0"))
      (libsource (lib "eagle-import") (part "RESISTORRLC_0603"))
    )
    (comp (ref "R46")
      (value "10K")
      (footprint "eagle-import:RLC_0603@1")
      (fields (field (name "MPN") "RMCF0603JT10K0"))
      (libsource (lib "eagle-import") (part "RESISTORRLC_0603"))
    )
    (comp (ref "SV2")
      (value "HIROSE-MQ172-4POS")
      (footprint "eagle-import:HIROSE-MQ172-4POS")
      (fields (field (name "MF") "MQ172X-4PA(66)"))
      (libsource (lib "eagle-import") (part "HIROSE-MQ172-4POS"))
    )
    (comp (ref "TP2")
      (value "TESTPADKEYSTONE-SMD")
      (footprint "eagle-import:KEYSTONE-SMD-TESTPOINT-5015")
      (libsource (lib "eagle-import") (part "TESTPADKEYSTONE-SMD"))
    )
    (comp (ref "TP3")
      (value "TESTPADKEYSTONE-SMD")
      (footprint "eagle-import:KEYSTONE-SMD-TESTPOINT-5015")
      (libsource (lib "eagle-import") (part "TESTPADKEYSTONE-SMD"))
    )
    (comp (ref "TP4")
      (value "TESTPADKEYSTONE-SMD")
      (footprint "eagle-import:KEYSTONE-SMD-TESTPOINT-5015")
      (libsource (lib "eagle-import") (part "TESTPADKEYSTONE-SMD"))
    )
    (comp (ref "TP5")
      (value "TESTPADKEYSTONE-SMD")
      (footprint "eagle-import:KEYSTONE-SMD-TESTPOINT-5015")
      (libsource (lib "eagle-import") (part "TESTPADKEYSTONE-SMD"))
    )
    (comp (ref "C10")
      (value "100nF")
      (footprint "eagle-import:RLC_0603")
      (fields (field (name "MPN") "CL10B104KO8NNNC"))
      (libsource (lib "eagle-import") (part "CAPACITORRLC_0603"))
    )
    (comp (ref "C11")
      (value "1nF")
      (footprint "eagle-import:RLC_0603")
      (fields (field (name "MPN") "GRM188R71H102KA01D"))
      (libsource (lib "eagle-import") (part "CAPACITORRLC_0603"))
    )
    (comp (ref "C12")
      (value "1nF")
      (footprint "eagle-import:RLC_0603")
      (fields (field (name "MPN") "GRM188R71H102KA01D"))
      (libsource (lib "eagle-import") (part "CAPACITORRLC_0603"))
    )
    (comp (ref "C13")
      (value "dnp")
      (footprint "eagle-import:RLC_0603")
      (libsource (lib "eagle-import") (part "CAPACITORRLC_0603"))
    )
    (comp (ref "C14")
      (value "22pF")
      (footprint "eagle-import:RLC_0603")
      (fields (field (name "MPN") "C1608C0G1H220J080AA"))
      (libsource (lib "eagle-import") (part "CAPACITORRLC_0603"))
    )
    (comp (ref "C15")
      (value "130pF")
      (footprint "eagle-import:RLC_0603")
      (fields (field (name "MPN") "GRM1885C1H131JA01D"))
      (libsource (lib "eagle-import") (part "CAPACITORRLC_0603"))
    )
    (comp (ref "C16")
      (value "1nF")
      (footprint "eagle-import:RLC_0603")
      (fields (field (name "MPN") "GRM188R71H102KA01D"))
      (libsource (lib "eagle-import") (part "CAPACITORRLC_0603"))
    )
    (comp (ref "C17")
      (value "dnp")
      (footprint "eagle-import:RLC_0603")
      (libsource (lib "eagle-import") (part "CAPACITORRLC_0603"))
    )
    (comp (ref "C40")
      (value "dnp")
      (footprint "eagle-import:RLC_0603")
      (libsource (lib "eagle-import") (part "CAPACITORRLC_0603"))
    )
    (comp (ref "C41")
      (value "dnp")
      (footprint "eagle-import:RLC_0603")
      (libsource (lib "eagle-import") (part "CAPACITORRLC_0603"))
    )
    (comp (ref "C42")
      (value "1nF")
      (footprint "eagle-import:RLC_0603")
      (fields (field (name "MPN") "GRM188R71H102KA01D"))
      (libsource (lib "eagle-import") (part "CAPACITORRLC_0603"))
    )
    (comp (ref "C43")
      (value "1nF")
      (footprint "eagle-import:RLC_0603")
      (fields (field (name "MPN") "GRM188R71H102KA01D"))
      (libsource (lib "eagle-import") (part "CAPACITORRLC_0603"))
    )
    (comp (ref "C45")
      (value "100nF")
      (footprint "eagle-import:RLC_0603")
      (fields (field (name "MPN") "CL10B104KO8NNNC"))
      (libsource (lib "eagle-import") (part "CAPACITORRLC_0603"))
    )
    (comp (ref "D1")
      (value "DIODE-SMD-SOT23")
      (footprint "eagle-import:SOT23-3LEAD")
      (fields (field (name "MF") "BAS 21 E6327"))
      (libsource (lib "eagle-import") (part "DIODE-SMD-SOT23"))
    )
    (comp (ref "D2")
      (value "DIODE-SMD-SOT23")
      (footprint "eagle-import:SOT23-3LEAD")
      (fields (field (name "MF") "BAS 21 E6327"))
      (libsource (lib "eagle-import") (part "DIODE-SMD-SOT23"))
    )
    (comp (ref "D3")
      (value "DIODE-SMD-SOT23")
      (footprint "eagle-import:SOT23-3LEAD")
      (fields (field (name "MF") "BAS 21 E6327"))
      (libsource (lib "eagle-import") (part "DIODE-SMD-SOT23"))
    )
    (comp (ref "D7")
      (value "DIODE-SMD-SOT23")
      (footprint "eagle-import:SOT23-3LEAD")
      (libsource (lib "eagle-import") (part "DIODE-SMD-SOT23"))
    )
    (comp (ref "D10")
      (value "DIODE-SMD-SOT23")
      (footprint "eagle-import:SOT23-3LEAD")
      (libsource (lib "eagle-import") (part "DIODE-SMD-SOT23"))
    )
    (comp (ref "D11")
      (value "DIODE-SMD-SOT23")
      (footprint "eagle-import:SOT23-3LEAD")
      (libsource (lib "eagle-import") (part "DIODE-SMD-SOT23"))
    )
    (comp (ref "IC5")
      (value "TLV3502")
      (footprint "eagle-import:SOT-23-8-OR-MSOP-8")
      (fields
        (field (name "MPN") "TLV3502AIDCNT")
        (field (name "DIGIKEY") "296-18147-1-ND")
        (field (name "OC_NEWARK") "unknown")
        (field (name "PARTNO") "TLV3502AIDCNT")
      )
      (libsource (lib "eagle-import") (part "COMP-TLV3502SOT-23-8-OR-MSOP-8"))
    )
    (comp (ref "IC6")
      (value "MCP6294")
      (footprint "eagle-import:TSSOP-14")
      (fields
        (field (name "DIGIKEY") "MCP6294-E/ST-ND")
        (field (name "MPN") "MCP6294-E/ST")
        (field (name "OC_NEWARK") "unknown")
        (field (name "PARTNO") "MCP6294-E/ST")
      )
      (libsource (lib "eagle-import") (part "OPAMP-TLC2274"))
    )
    (comp (ref "IC11")
      (value "CD4066")
      (footprint "eagle-import:TSSOP-14")
      (fields (field (name "MPN") "CD4066BPWR"))
      (libsource (lib "eagle-import") (part "CD4066"))
    )
    (comp (ref "IC14")
      (value "AD8052")
      (footprint "eagle-import:MSOP8")
      (fields
        (field (name "MPN") "AD8052ARMZ")
        (field (name "DIGIKEY") "AD8052ARMZ-ND")
        (field (name "OC_NEWARK") "unknown")
        (field (name "PARTNO") "AD8052ARMZ")
      )
      (libsource (lib "eagle-import") (part "OPAMP-AD8052"))
    )
    (comp (ref "Q1")
      (value "NPN-SOT23-2N3904")
      (footprint "eagle-import:SOT23-3LEAD")
      (fields (field (name "MF") "PMBT3904,215"))
      (libsource (lib "eagle-import") (part "NPN-SOT23-2N3904"))
    )
    (comp (ref "R9")
      (value "100K")
      (footprint "eagle-import:RLC_0603@1")
      (fields (field (name "MPN") "RC0603JR-07100KL"))
      (libsource (lib "eagle-import") (part "RESISTORRLC_0603"))
    )
    (comp (ref "R10")
      (value "100K")
      (footprint "eagle-import:RLC_0603@1")
      (fields (field (name "MPN") "RC0603JR-07100KL"))
      (libsource (lib "eagle-import") (part "RESISTORRLC_0603"))
    )
    (comp (ref "R11")
      (value "510K")
      (footprint "eagle-import:RLC_0603@1")
      (fields (field (name "MPN") "ERJ-3GEYJ514V"))
      (libsource (lib "eagle-import") (part "RESISTORRLC_0603"))
    )
    (comp (ref "R12")
      (value "100K")
      (footprint "eagle-import:RLC_0603@1")
      (fields (field (name "MPN") "RC0603JR-07100KL"))
      (libsource (lib "eagle-import") (part "RESISTORRLC_0603"))
    )
    (comp (ref "R13")
      (value "10K")
      (footprint "eagle-import:RLC_0603@1")
      (fields (field (name "DIGIKEY") "RMCF0603JT10K0CT-ND") (field (name "MPN") "RMCF0603JT10K0"))
      (libsource (lib "eagle-import") (part "RESISTORRLC_0603"))
    )
    (comp (ref "R14")
      (value "10K")
      (footprint "eagle-import:RLC_0603@1")
      (fields (field (name "DIGIKEY") "RMCF0603JT10K0CT-ND") (field (name "MPN") "RMCF0603JT10K0"))
      (libsource (lib "eagle-import") (part "RESISTORRLC_0603"))
    )
    (comp (ref "R15")
      (value "10K")
      (footprint "eagle-import:RLC_0603@1")
      (fields (field (name "DIGIKEY") "RMCF0603JT10K0CT-ND") (field (name "MPN") "RMCF0603JT10K0"))
      (libsource (lib "eagle-import") (part "RESISTORRLC_0603"))
    )
    (comp (ref "R16")
      (value "zerohm")
      (footprint "eagle-import:RLC_0603@1")
      (libsource (lib "eagle-import") (part "RESISTORRLC_0603"))
    )
    (comp (ref "R17")
      (value "10K")
      (footprint "eagle-import:RLC_0603@1")
      (fields (field (name "DIGIKEY") "RMCF0603JT10K0CT-ND") (field (name "MPN") "RMCF0603JT10K0"))
      (libsource (lib "eagle-import") (part "RESISTORRLC_0603"))
    )
    (comp (ref "R18")
      (value "10K")
      (footprint "eagle-import:RLC_0603@1")
      (fields (field (name "DIGIKEY") "RMCF0603JT10K0CT-ND") (field (name "MPN") "RMCF0603JT10K0"))
      (libsource (lib "eagle-import") (part "RESISTORRLC_0603"))
    )
    (comp (ref "R19")
      (value "10K")
      (footprint "eagle-import:RLC_0603@1")
      (fields (field (name "DIGIKEY") "RMCF0603JT10K0CT-ND") (field (name "MPN") "RMCF0603JT10K0"))
      (libsource (lib "eagle-import") (part "RESISTORRLC_0603"))
    )
    (comp (ref "R20")
      (value "240K")
      (footprint "eagle-import:RLC_0603@1")
      (fields (field (name "MPN") "RC1608J244CS"))
      (libsource (lib "eagle-import") (part "RESISTORRLC_0603"))
    )
    (comp (ref "R21")
      (value "24K")
      (footprint "eagle-import:RLC_0603@1")
      (fields (field (name "MPN") "RC0603JR-0724KL"))
      (libsource (lib "eagle-import") (part "RESISTORRLC_0603"))
    )
    (comp (ref "R30")
      (value "10M")
      (footprint "eagle-import:RLC_0603@1")
      (fields (field (name "MPN") "RC0603JR-0710ML"))
      (libsource (lib "eagle-import") (part "RESISTORRLC_0603"))
    )
    (comp (ref "R31")
      (value "240K")
      (footprint "eagle-import:RLC_0603@1")
      (fields (field (name "MPN") "RC1608J244CS"))
      (libsource (lib "eagle-import") (part "RESISTORRLC_0603"))
    )
    (comp (ref "R32")
      (value "zerohm")
      (footprint "eagle-import:RLC_0603@1")
      (libsource (lib "eagle-import") (part "RESISTORRLC_0603"))
    )
    (comp (ref "R33")
      (value "2.4K")
      (footprint "eagle-import:RLC_0603@1")
      (fields (field (name "MPN") "RC0603FR-072K4L"))
      (libsource (lib "eagle-import") (part "RESISTORRLC_0603"))
    )
    (comp (ref "R34")
      (value "10K")
      (footprint "eagle-import:RLC_0603@1")
      (fields (field (name "MPN") "RMCF0603JT10K0"))
      (libsource (lib "eagle-import") (part "RESISTORRLC_0603"))
    )
    (comp (ref "R35")
      (value "zerohm")
      (footprint "eagle-import:RLC_0603@1")
      (libsource (lib "eagle-import") (part "RESISTORRLC_0603"))
    )
    (comp (ref "R36")
      (value "dnp")
      (footprint "eagle-import:RLC_0603@1")
      (libsource (lib "eagle-import") (part "RESISTORRLC_0603"))
    )
    (comp (ref "R37")
      (value "dnp")
      (footprint "eagle-import:RLC_0603@1")
      (libsource (lib "eagle-import") (part "RESISTORRLC_0603"))
    )
    (comp (ref "R38")
      (value "dnp")
      (footprint "eagle-import:RLC_0603@1")
      (libsource (lib "eagle-import") (part "RESISTORRLC_0603"))
    )
    (comp (ref "R40")
      (value "10K")
      (footprint "eagle-import:RLC_0603@1")
      (fields (field (name "MPN") "RMCF0603JT10K0"))
      (libsource (lib "eagle-import") (part "RESISTORRLC_0603"))
    )
    (comp (ref "R41")
      (value "10M")
      (footprint "eagle-import:RLC_0603@1")
      (fields (field (name "MPN") "RC0603JR-0710ML"))
      (libsource (lib "eagle-import") (part "RESISTORRLC_0603"))
    )
    (comp (ref "R42")
      (value "1M")
      (footprint "eagle-import:RLC_0603@1")
      (fields (field (name "MPN") "RC0603JR-071ML"))
      (libsource (lib "eagle-import") (part "RESISTORRLC_0603"))
    )
    (comp (ref "R48")
      (value "dnp")
      (footprint "eagle-import:RLC_0603@1")
      (libsource (lib "eagle-import") (part "RESISTORRLC_0603"))
    )
    (comp (ref "R49")
      (value "2.4K")
      (footprint "eagle-import:RLC_0603@1")
      (fields (field (name "MPN") "RC0603FR-072K4L"))
      (libsource (lib "eagle-import") (part "RESISTORRLC_0603"))
    )
    (comp (ref "R50")
      (value "10K")
      (footprint "eagle-import:RLC_0603@1")
      (fields (field (name "MPN") "RMCF0603JT10K0"))
      (libsource (lib "eagle-import") (part "RESISTORRLC_0603"))
    )
    (comp (ref "R51")
      (value "2.4K")
      (footprint "eagle-import:RLC_0603@1")
      (fields (field (name "MPN") "RC0603FR-072K4L"))
      (libsource (lib "eagle-import") (part "RESISTORRLC_0603"))
    )
    (comp (ref "RLY1")
      (value "G6S-2H")
      (footprint "eagle-import:G6S-2F")
      (libsource (lib "eagle-import") (part "G6S-2H"))
    )
    (comp (ref "TP1")
      (value "TESTPAD")
      (footprint "eagle-import:SMD-TESTPOINT")
      (libsource (lib "eagle-import") (part "TESTPAD"))
    )
  )
  (nets
    (net (code "1") (name "+1V2") (class "Default")
      (node (ref "C206") (pin "1") (pinfunction "1_1") (pintype "passive"))
      (node (ref "C209") (pin "1") (pinfunction "1_1") (pintype "passive"))
      (node (ref "C210") (pin "1") (pinfunction "1_1") (pintype "passive"))
      (node (ref "C211") (pin "1") (pinfunction "1_1") (pintype "passive"))
      (node (ref "C212") (pin "1") (pinfunction "1_1") (pintype "passive"))
      (node (ref "IC106") (pin "5") (pinfunction "VOUT_5") (pintype "bidirectional"))
      (node (ref "TP20") (pin "1") (pinfunction "P$1_1") (pintype "bidirectional"))
      (node (ref "U2") (pin "18") (pinfunction "VCCINT_18") (pintype "power_in"))
      (node (ref "U2") (pin "45") (pinfunction "VCCINT_45") (pintype "power_in"))
      (node (ref "U2") (pin "69") (pinfunction "VCCINT_69") (pintype "power_in"))
      (node (ref "U2") (pin "93") (pinfunction "VCCINT_93") (pintype "power_in"))
    )
    (net (code "2") (name "+2V5") (class "Default")
      (node (ref "C29") (pin "1") (pinfunction "1_1") (pintype "passive"))
      (node (ref "C30") (pin "1") (pinfunction "1_1") (pintype "passive"))
      (node (ref "C31") (pin "1") (pinfunction "1_1") (pintype "passive"))
      (node (ref "C33") (pin "1") (pinfunction "1_1") (pintype "passive"))
      (node (ref "IC105") (pin "5") (pinfunction "VOUT_5") (pintype "bidirectional"))
      (node (ref "TP19") (pin "1") (pinfunction "P$1_1") (pintype "bidirectional"))
      (node (ref "U2") (pin "33") (pinfunction "VCCAUX_33") (pintype "power_in"))
      (node (ref "U2") (pin "58") (pinfunction "VCCAUX_58") (pintype "power_in"))
      (node (ref "U2") (pin "7") (pinfunction "VCCAUX_7") (pintype "power_in"))
      (node (ref "U2") (pin "84") (pinfunction "VCCAUX_84") (pintype "power_in"))
    )
    (net (code "3") (name "+3V3") (class "Default")
      (node (ref "BUZ1") (pin "1") (pinfunction "1_1") (pintype "passive"))
      (node (ref "C25") (pin "1") (pinfunction "1_1") (pintype "passive"))
      (node (ref "C26") (pin "1") (pinfunction "1_1") (pintype "passive"))
      (node (ref "C27") (pin "1") (pinfunction "1_1") (pintype "passive"))
      (node (ref "C48") (pin "1") (pinfunction "1_1") (pintype "passive"))
      (node (ref "C49") (pin "1") (pinfunction "1_1") (pintype "passive"))
      (node (ref "C50") (pin "1") (pinfunction "1_1") (pintype "passive"))
      (node (ref "C51") (pin "1") (pinfunction "1_1") (pintype "passive"))
      (node (ref "C7") (pin "1") (pinfunction "1_1") (pintype "passive"))
      (node (ref "D5") (pin "1") (pinfunction "A_1") (pintype "passive"))
      (node (ref "IC2") (pin "19") (pinfunction "VDD_19") (pintype "power_in"))
      (node (ref "IC2") (pin "32") (pinfunction "VDD_32") (pintype "power_in"))
      (node (ref "IC2") (pin "48") (pinfunction "VDD_48") (pintype "power_in"))
      (node (ref "IC2") (pin "64") (pinfunction "VDD_64") (pintype "power_in"))
      (node (ref "IC3") (pin "5") (pinfunction "VO_5") (pintype "bidirectional"))
      (node (ref "IC7") (pin "2") (pinfunction "V+_2") (pintype "bidirectional"))
      (node (ref "JP4") (pin "6") (pinfunction "6_6") (pintype "passive"))
      (node (ref "L1") (pin "1") (pinfunction "P$1_1") (pintype "bidirectional"))
      (node (ref "Q2") (pin "C") (pinfunction "C_C") (pintype "passive"))
      (node (ref "R57") (pin "1") (pinfunction "1_1") (pintype "passive"))
      (node (ref "R61") (pin "2") (pinfunction "2_2") (pintype "passive"))
      (node (ref "R62") (pin "2") (pinfunction "2_2") (pintype "passive"))
      (node (ref "R63") (pin "2") (pinfunction "2_2") (pintype "passive"))
      (node (ref "R64") (pin "2") (pinfunction "2_2") (pintype "passive"))
      (node (ref "R66") (pin "2") (pinfunction "2_2") (pintype "passive"))
      (node (ref "R69") (pin "2") (pinfunction "2_2") (pintype "passive"))
      (node (ref "R70") (pin "2") (pinfunction "2_2") (pintype "passive"))
      (node (ref "R71") (pin "2") (pinfunction "2_2") (pintype "passive"))
      (node (ref "SV5") (pin "6") (pinfunction "6_6") (pintype "passive"))
      (node (ref "U3") (pin "6") (pinfunction "VBAT_6") (pintype "input"))
      (node (ref "U3") (pin "9") (pinfunction "VDD_9") (pintype "power_in"))
      (node (ref "U4") (pin "4") (pinfunction "VCC_4") (pintype "bidirectional"))
    )
    (net (code "4") (name "+3V3-FPGA") (class "Default")
      (node (ref "C28") (pin "1") (pinfunction "1_1") (pintype "passive"))
      (node (ref "C32") (pin "1") (pinfunction "1_1") (pintype "passive"))
      (node (ref "C34") (pin "1") (pinfunction "1_1") (pintype "passive"))
      (node (ref "C47") (pin "1") (pinfunction "1_1") (pintype "passive"))
      (node (ref "IC13") (pin "5") (pinfunction "VO_5") (pintype "bidirectional"))
      (node (ref "IC4") (pin "5") (pinfunction "VDD_5") (pintype "bidirectional"))
      (node (ref "R59") (pin "2") (pinfunction "2_2") (pintype "passive"))
      (node (ref "TP18") (pin "1") (pinfunction "P$1_1") (pintype "bidirectional"))
      (node (ref "U2") (pin "19") (pinfunction "VCCO_6_19") (pintype "bidirectional"))
      (node (ref "U2") (pin "31") (pinfunction "VCCO_5_31") (pintype "bidirectional"))
      (node (ref "U2") (pin "46") (pinfunction "VCCO_4_46") (pintype "bidirectional"))
      (node (ref "U2") (pin "57") (pinfunction "VCCO_3_57") (pintype "bidirectional"))
      (node (ref "U2") (pin "6") (pinfunction "VCCO_7_6") (pintype "bidirectional"))
      (node (ref "U2") (pin "70") (pinfunction "VCCO_2_70") (pintype "bidirectional"))
      (node (ref "U2") (pin "83") (pinfunction "VCCO_1_83") (pintype "bidirectional"))
      (node (ref "U2") (pin "94") (pinfunction "VCCO_0_94") (pintype "bidirectional"))
    )
    (net (code "6") (name "1356_CRYSTAL") (class "Default")
      (node (ref "C3") (pin "1") (pinfunction "1_1") (pintype "passive"))
      (node (ref "R1") (pin "2") (pinfunction "2_2") (pintype "passive"))
      (node (ref "R2") (pin "2") (pinfunction "2_2") (pintype "passive"))
      (node (ref "U2") (pin "89") (pinfunction "L32P_0/GCLK6_89") (pintype "bidirectional"))
      (node (ref "U2") (pin "90") (pinfunction "L32N_0/GCLK7_90") (pintype "bidirectional"))
      (node (ref "XT1") (pin "B") (pinfunction "B_B") (pintype "bidirectional"))
    )
    (net (code "7") (name "ADC1") (class "Default")
      (node (ref "IC8") (pin "3") (pinfunction "D1_3") (pintype "bidirectional"))
      (node (ref "U2") (pin "38") (pinfunction "L32P_4/GCLK0_38") (pintype "bidirectional"))
    )
    (net (code "8") (name "ADC2") (class "Default")
      (node (ref "IC8") (pin "4") (pinfunction "D2_4") (pintype "bidirectional"))
      (node (ref "U2") (pin "37") (pinfunction "L32N_5/GCLK3_37") (pintype "bidirectional"))
    )
    (net (code "9") (name "ADC3") (class "Default")
      (node (ref "IC8") (pin "5") (pinfunction "D3_5") (pintype "bidirectional"))
      (node (ref "U2") (pin "36") (pinfunction "L32P_5/GCLK2_36") (pintype "bidirectional"))
    )
    (net (code "10") (name "ADC4") (class "Default")
      (node (ref "IC8") (pin "6") (pinfunction "D4_6") (pintype "bidirectional"))
      (node (ref "U2") (pin "35") (pinfunction "L31N_5/D4_35") (pintype "bidirectional"))
    )
    (net (code "11") (name "ADC5") (class "Default")
      (node (ref "IC8") (pin "7") (pinfunction "D5_7") (pintype "bidirectional"))
      (node (ref "U2") (pin "34") (pinfunction "L31P_5/D5_34") (pintype "bidirectional"))
    )
    (net (code "12") (name "ADC6") (class "Default")
      (node (ref "IC8") (pin "8") (pinfunction "D6_8") (pintype "bidirectional"))
      (node (ref "U2") (pin "32") (pinfunction "L28N_5/D6_32") (pintype "bidirectional"))
    )
    (net (code "13") (name "ADC7") (class "Default")
      (node (ref "IC8") (pin "9") (pinfunction "D7_9") (pintype "bidirectional"))
      (node (ref "U2") (pin "30") (pinfunction "L28P_5/D7_30") (pintype "bidirectional"))
    )
    (net (code "14") (name "ADC8") (class "Default")
      (node (ref "IC8") (pin "10") (pinfunction "MSB-D8_10") (pintype "bidirectional"))
      (node (ref "U2") (pin "28") (pinfunction "L01N_5/RDWR_B_28") (pintype "bidirectional"))
    )
    (net (code "15") (name "ADC_CLK") (class "Default")
      (node (ref "ADC_CLK_TP") (pin "1") (pinfunction "P$1_1") (pintype "bidirectional"))
      (node (ref "IC8") (pin "12") (pinfunction "CLK_12") (pintype "bidirectional"))
      (node (ref "U2") (pin "27") (pinfunction "L01P_5/CS_B_27") (pintype "bidirectional"))
    )
    (net (code "16") (name "ADC_IN") (class "Default")
      (node (ref "IC11") (pin "10") (pinfunction "B4_10") (pintype "passive"))
      (node (ref "IC11") (pin "2") (pinfunction "B1_2") (pintype "passive"))
      (node (ref "IC11") (pin "3") (pinfunction "B2_3") (pintype "passive"))
      (node (ref "IC11") (pin "9") (pinfunction "B3_9") (pintype "passive"))
      (node (ref "IC8") (pin "19") (pinfunction "ANALOGIN_19") (pintype "bidirectional"))
      (node (ref "TP1") (pin "1") (pinfunction "P$1_1") (pintype "bidirectional"))
    )
    (net (code "17") (name "ADC_NOE") (class "Default")
      (node (ref "ADC_NOE_TP") (pin "1") (pinfunction "P$1_1") (pintype "bidirectional"))
      (node (ref "IC8") (pin "1") (pinfunction "NOE_1") (pintype "bidirectional"))
      (node (ref "R47") (pin "2") (pinfunction "2_2") (pintype "passive"))
      (node (ref "U2") (pin "49") (pinfunction "L01P_4/VRN_4_49") (pintype "bidirectional"))
    )
    (net (code "18") (name "AMPL_HI") (class "Default")
      (node (ref "JP_AH") (pin "2") (pinfunction "2_2") (pintype "passive"))
      (node (ref "R41") (pin "2") (pinfunction "2_2") (pintype "passive"))
      (node (ref "R42") (pin "2") (pinfunction "2_2") (pintype "passive"))
    )
    (net (code "19") (name "AMPL_HI1") (class "Default")
      (node (ref "IC2") (pin "14") (pinfunction "PA0/WKUP/USART2_CTS/ADC123_IN0/TIM2_CH1_ETR/TIM5_CH1/TIME8_ETR_14") (pintype "bidirectional"))
      (node (ref "JP_AH") (pin "1") (pinfunction "1_1") (pintype "passive"))
      (node (ref "TP52") (pin "1") (pinfunction "P$1_1") (pintype "bidirectional"))
    )
    (net (code "20") (name "AMPL_LO") (class "Default")
      (node (ref "JP_AL") (pin "2") (pinfunction "2_2") (pintype "passive"))
      (node (ref "R30") (pin "2") (pinfunction "2_2") (pintype "passive"))
      (node (ref "R31") (pin "2") (pinfunction "2_2") (pintype "passive"))
    )
    (net (code "21") (name "AMPL_LO1") (class "Default")
      (node (ref "IC2") (pin "15") (pinfunction "PA1/USART2_RTS/ADC123_IN1/TIM5_CH2/TIM2_CH2_15") (pintype "bidirectional"))
      (node (ref "JP_AL") (pin "1") (pinfunction "1_1") (pintype "passive"))
      (node (ref "TP53") (pin "1") (pinfunction "P$1_1") (pintype "bidirectional"))
    )
    (net (code "22") (name "ANT_HI") (class "Default")
      (node (ref "C35") (pin "1") (pinfunction "1_1") (pintype "passive"))
      (node (ref "C36") (pin "1") (pinfunction "1_1") (pintype "passive"))
      (node (ref "RLY1") (pin "4") (pinfunction "COM_4") (pintype "passive"))
      (node (ref "SV2") (pin "4") (pinfunction "PIN4_4") (pintype "passive"))
      (node (ref "TP3") (pin "1") (pinfunction "P$1_1") (pintype "bidirectional"))
    )
    (net (code "23") (name "ANT_LO") (class "Default")
      (node (ref "C20") (pin "1") (pinfunction "1_1") (pintype "passive"))
      (node (ref "C39") (pin "1") (pinfunction "1_1") (pintype "passive"))
      (node (ref "RLY1") (pin "9") (pinfunction "COM_9") (pintype "passive"))
      (node (ref "SV2") (pin "2") (pinfunction "PIN2_2") (pintype "passive"))
      (node (ref "TP2") (pin "1") (pinfunction "P$1_1") (pintype "bidirectional"))
    )
    (net (code "24") (name "BOOT0_") (class "Default")
      (node (ref "JP4") (pin "7") (pinfunction "7_7") (pintype "passive"))
      (node (ref "R4") (pin "1") (pinfunction "1_1") (pintype "passive"))
    )
    (net (code "25") (name "CROSS_HI") (class "Default")
      (node (ref "CROSS_HI_TP") (pin "1") (pinfunction "P$1_1") (pintype "bidirectional"))
      (node (ref "IC5") (pin "6") (pinfunction "OUT_6") (pintype "output"))
      (node (ref "R44") (pin "1") (pinfunction "1_1") (pintype "passive"))
    )
    (net (code "26") (name "CROSS_LO") (class "Default")
      (node (ref "CROSS_LO_TP") (pin "1") (pinfunction "P$1_1") (pintype "bidirectional"))
      (node (ref "IC5") (pin "7") (pinfunction "OUT_7") (pintype "output"))
      (node (ref "R39") (pin "1") (pinfunction "1_1") (pintype "passive"))
    )
    (net (code "27") (name "DB2") (class "Default")
      (node (ref "SJ1") (pin "2") (pinfunction "2_2") (pintype "passive"))
      (node (ref "U3") (pin "20") (pinfunction "D2/I2C_SDA_20") (pintype "bidirectional"))
    )
    (net (code "28") (name "DBG") (class "Default")
      (node (ref "DBG_TP") (pin "1") (pinfunction "P$1_1") (pintype "bidirectional"))
      (node (ref "U2") (pin "75") (pinfunction "L01N_2/VRP_2_75") (pintype "bidirectional"))
    )
    (net (code "29") (name "D{slash}C") (class "Default")
      (node (ref "IC2") (pin "59") (pinfunction "PB7/I2C1_SDA/FSMC_NADV/TIM4_CH2/USART1_RX/FT_59") (pintype "bidirectional"))
      (node (ref "TP30") (pin "1") (pinfunction "P$1_1") (pintype "bidirectional"))
      (node (ref "U3") (pin "15") (pinfunction "DC/I2C_SA0_15") (pintype "input"))
    )
    (net (code "30") (name "FPGA_CCLK") (class "Default")
      (node (ref "IC2") (pin "41") (pinfunction "PA8/USART1_CK/TIM1_CH1/MCO/FT_41") (pintype "bidirectional"))
      (node (ref "TP25") (pin "1") (pinfunction "P$1_1") (pintype "bidirectional"))
      (node (ref "U2") (pin "52") (pinfunction "CCLK_52") (pintype "bidirectional"))
    )
    (net (code "31") (name "FPGA_DIN") (class "Default")
      (node (ref "IC2") (pin "42") (pinfunction "PA9/USART1_TX/TIM1_CH2/FT_42") (pintype "bidirectional"))
      (node (ref "TP26") (pin "1") (pinfunction "P$1_1") (pintype "bidirectional"))
      (node (ref "U2") (pin "48") (pinfunction "L27N_4/DIN/DO_48") (pintype "bidirectional"))
    )
    (net (code "32") (name "FPGA_DONE") (class "Default")
      (node (ref "IC2") (pin "26") (pinfunction "PB0/ADC12_IN8/TIM3_CH3/TIM8_CH2N/TIM1_CH2N_26") (pintype "bidirectional"))
      (node (ref "TP35") (pin "1") (pinfunction "P$1_1") (pintype "bidirectional"))
      (node (ref "U2") (pin "51") (pinfunction "DONE_51") (pintype "bidirectional"))
    )
    (net (code "33") (name "FPGA_DOUT") (class "Default")
      (node (ref "FPGA_DOUT_TP") (pin "1") (pinfunction "P$1_1") (pintype "bidirectional"))
      (node (ref "IC2") (pin "52") (pinfunction "PC11/UART4_RX/SDIO_D3/USART3_RX/FT_52") (pintype "bidirectional"))
      (node (ref "U2") (pin "40") (pinfunction "L31P_4/DOUT/BUSY_40") (pintype "bidirectional"))
    )
    (net (code "34") (name "FPGA_NINIT") (class "Default")
      (node (ref "FPGA_NINIT_TP") (pin "1") (pinfunction "P$1_1") (pintype "bidirectional"))
      (node (ref "IC2") (pin "38") (pinfunction "PC7/I2S3_MCK/TIM8_CH2/SDIO_D7/TIM3_CH2/FT_38") (pintype "bidirectional"))
      (node (ref "R59") (pin "1") (pinfunction "1_1") (pintype "passive"))
      (node (ref "U2") (pin "42") (pinfunction "L31N_4/INIT_B_42") (pintype "bidirectional"))
    )
    (net (code "35") (name "FPGA_NPROGRAM") (class "Default")
      (node (ref "IC2") (pin "23") (pinfunction "PA7/SPI1_MOSI/TIM8_CH1N/ADC12_IN7/TIM3_CH2/TIM1_CH1N_23") (pintype "bidirectional"))
      (node (ref "TP24") (pin "1") (pinfunction "P$1_1") (pintype "bidirectional"))
      (node (ref "U2") (pin "99") (pinfunction "PROG_B_99") (pintype "bidirectional"))
    )
    (net (code "36") (name "FPGA_ON") (class "Default")
      (node (ref "IC105") (pin "3") (pinfunction "EN_3") (pintype "bidirectional"))
      (node (ref "IC106") (pin "3") (pinfunction "EN_3") (pintype "bidirectional"))
      (node (ref "IC13") (pin "3") (pinfunction "VC_3") (pintype "bidirectional"))
      (node (ref "IC2") (pin "30") (pinfunction "PB11/I2C2_SDA/USART3_RX/TIM2_CH4/FT_30") (pintype "bidirectional"))
      (node (ref "R102") (pin "1") (pinfunction "1_1") (pintype "passive"))
      (node (ref "R23") (pin "2") (pinfunction "2_2") (pintype "passive"))
      (node (ref "TP22") (pin "1") (pinfunction "P$1_1") (pintype "bidirectional"))
    )
    (net (code "37") (name "FPGA_TCK") (class "Default")
      (node (ref "SV5") (pin "4") (pinfunction "4_4") (pintype "passive"))
      (node (ref "U2") (pin "77") (pinfunction "TCK_77") (pintype "bidirectional"))
    )
    (net (code "38") (name "FPGA_TDI") (class "Default")
      (node (ref "SV5") (pin "2") (pinfunction "2_2") (pintype "passive"))
      (node (ref "U2") (pin "100") (pinfunction "TDI_100") (pintype "bidirectional"))
    )
    (net (code "39") (name "FPGA_TDO") (class "Default")
      (node (ref "SV5") (pin "3") (pinfunction "3_3") (pintype "passive"))
      (node (ref "U2") (pin "76") (pinfunction "TDO_76") (pintype "bidirectional"))
    )
    (net (code "40") (name "FPGA_TMS") (class "Default")
      (node (ref "SV5") (pin "1") (pinfunction "1_1") (pintype "passive"))
      (node (ref "U2") (pin "78") (pinfunction "TMS_78") (pintype "bidirectional"))
    )
    (net (code "41") (name "GND") (class "Default")
      (node (ref "BAT1") (pin "GND") (pinfunction "-_GND") (pintype "power_in"))
      (node (ref "C1") (pin "2") (pinfunction "2_2") (pintype "passive"))
      (node (ref "C10") (pin "2") (pinfunction "2_2") (pintype "passive"))
      (node (ref "C11") (pin "2") (pinfunction "2_2") (pintype "passive"))
      (node (ref "C15") (pin "2") (pinfunction "2_2") (pintype "passive"))
      (node (ref "C18") (pin "2") (pinfunction "2_2") (pintype "passive"))
      (node (ref "C19") (pin "2") (pinfunction "2_2") (pintype "passive"))
      (node (ref "C2") (pin "2") (pinfunction "2_2") (pintype "passive"))
      (node (ref "C20") (pin "2") (pinfunction "2_2") (pintype "passive"))
      (node (ref "C206") (pin "2") (pinfunction "2_2") (pintype "passive"))
      (node (ref "C209") (pin "2") (pinfunction "2_2") (pintype "passive"))
      (node (ref "C21") (pin "2") (pinfunction "2_2") (pintype "passive"))
      (node (ref "C210") (pin "2") (pinfunction "2_2") (pintype "passive"))
      (node (ref "C211") (pin "2") (pinfunction "2_2") (pintype "passive"))
      (node (ref "C212") (pin "2") (pinfunction "2_2") (pintype "passive"))
      (node (ref "C22") (pin "2") (pinfunction "2_2") (pintype "passive"))
      (node (ref "C23") (pin "2") (pinfunction "2_2") (pintype "passive"))
      (node (ref "C24") (pin "2") (pinfunction "2_2") (pintype "passive"))
      (node (ref "C25") (pin "2") (pinfunction "2_2") (pintype "passive"))
      (node (ref "C26") (pin "2") (pinfunction "2_2") (pintype "passive"))
      (node (ref "C27") (pin "2") (pinfunction "2_2") (pintype "passive"))
      (node (ref "C28") (pin "2") (pinfunction "2_2") (pintype "passive"))
      (node (ref "C29") (pin "2") (pinfunction "2_2") (pintype "passive"))
      (node (ref "C3") (pin "2") (pinfunction "2_2") (pintype "passive"))
      (node (ref "C30") (pin "2") (pinfunction "2_2") (pintype "passive"))
      (node (ref "C31") (pin "2") (pinfunction "2_2") (pintype "passive"))
      (node (ref "C32") (pin "2") (pinfunction "2_2") (pintype "passive"))
      (node (ref "C33") (pin "2") (pinfunction "2_2") (pintype "passive"))
      (node (ref "C34") (pin "2") (pinfunction "2_2") (pintype "passive"))
      (node (ref "C35") (pin "2") (pinfunction "2_2") (pintype "passive"))
      (node (ref "C36") (pin "2") (pinfunction "2_2") (pintype "passive"))
      (node (ref "C37") (pin "-") (pinfunction "-_-") (pintype "passive"))
      (node (ref "C38") (pin "-") (pinfunction "-_-") (pintype "passive"))
      (node (ref "C39") (pin "2") (pinfunction "2_2") (pintype "passive"))
      (node (ref "C44") (pin "2") (pinfunction "2_2") (pintype "passive"))
      (node (ref "C45") (pin "2") (pinfunction "2_2") (pintype "passive"))
      (node (ref "C46") (pin "2") (pinfunction "2_2") (pintype "passive"))
      (node (ref "C47") (pin "2") (pinfunction "2_2") (pintype "passive"))
      (node (ref "C48") (pin "2") (pinfunction "2_2") (pintype "passive"))
      (node (ref "C49") (pin "2") (pinfunction "2_2") (pintype "passive"))
      (node (ref "C50") (pin "2") (pinfunction "2_2") (pintype "passive"))
      (node (ref "C51") (pin "2") (pinfunction "2_2") (pintype "passive"))
      (node (ref "C52") (pin "2") (pinfunction "2_2") (pintype "passive"))
      (node (ref "C53") (pin "1") (pinfunction "1_1") (pintype "passive"))
      (node (ref "C54") (pin "1") (pinfunction "1_1") (pintype "passive"))
      (node (ref "C55") (pin "C") (pinfunction "-_C") (pintype "passive"))
      (node (ref "C56") (pin "2") (pinfunction "2_2") (pintype "passive"))
      (node (ref "C57") (pin "2") (pinfunction "2_2") (pintype "passive"))
      (node (ref "C58") (pin "2") (pinfunction "2_2") (pintype "passive"))
      (node (ref "C59") (pin "2") (pinfunction "2_2") (pintype "passive"))
      (node (ref "C6") (pin "2") (pinfunction "2_2") (pintype "passive"))
      (node (ref "C60") (pin "2") (pinfunction "2_2") (pintype "passive"))
      (node (ref "C61") (pin "2") (pinfunction "2_2") (pintype "passive"))
      (node (ref "C62") (pin "2") (pinfunction "2_2") (pintype "passive"))
      (node (ref "C63") (pin "2") (pinfunction "2_2") (pintype "passive"))
      (node (ref "C64") (pin "2") (pinfunction "2_2") (pintype "passive"))
      (node (ref "C65") (pin "2") (pinfunction "2_2") (pintype "passive"))
      (node (ref "C66") (pin "2") (pinfunction "2_2") (pintype "passive"))
      (node (ref "C67") (pin "2") (pinfunction "2_2") (pintype "passive"))
      (node (ref "C68") (pin "-") (pinfunction "-_-") (pintype "passive"))
      (node (ref "C69") (pin "-") (pinfunction "-_-") (pintype "passive"))
      (node (ref "C7") (pin "2") (pinfunction "2_2") (pintype "passive"))
      (node (ref "C70") (pin "-") (pinfunction "-_-") (pintype "passive"))
      (node (ref "C71") (pin "2") (pinfunction "2_2") (pintype "passive"))
      (node (ref "C72") (pin "2") (pinfunction "2_2") (pintype "passive"))
      (node (ref "C73") (pin "-") (pinfunction "-_-") (pintype "passive"))
      (node (ref "C74") (pin "2") (pinfunction "2_2") (pintype "passive"))
      (node (ref "C75") (pin "2") (pinfunction "2_2") (pintype "passive"))
      (node (ref "C8") (pin "2") (pinfunction "2_2") (pintype "passive"))
      (node (ref "C9") (pin "1") (pinfunction "1_1") (pintype "passive"))
      (node (ref "D10") (pin "1") (pinfunction "A_1") (pintype "passive"))
      (node (ref "D11") (pin "1") (pinfunction "A_1") (pintype "passive"))
      (node (ref "D3") (pin "1") (pinfunction "A_1") (pintype "passive"))
      (node (ref "D6") (pin "1") (pinfunction "P$1_1") (pintype "passive"))
      (node (ref "IC1") (pin "4") (pinfunction "PGND_4") (pintype "power_in"))
      (node (ref "IC1") (pin "9") (pinfunction "GND_9") (pintype "power_in"))
      (node (ref "IC10") (pin "10") (pinfunction "VSS_10") (pintype "bidirectional"))
      (node (ref "IC105") (pin "2") (pinfunction "GND_2") (pintype "bidirectional"))
      (node (ref "IC106") (pin "2") (pinfunction "GND_2") (pintype "bidirectional"))
      (node (ref "IC11") (pin "7") (pinfunction "VSS_7") (pintype "bidirectional"))
      (node (ref "IC13") (pin "2") (pinfunction "GND_2") (pintype "bidirectional"))
      (node (ref "IC14") (pin "4") (pinfunction "V-_4") (pintype "bidirectional"))
      (node (ref "IC2") (pin "12") (pinfunction "VSSA_12") (pintype "power_in"))
      (node (ref "IC2") (pin "18") (pinfunction "VSS_18") (pintype "power_in"))
      (node (ref "IC2") (pin "31") (pinfunction "VSS_31") (pintype "power_in"))
      (node (ref "IC2") (pin "47") (pinfunction "VSS_47") (pintype "power_in"))
      (node (ref "IC2") (pin "63") (pinfunction "VSS_63") (pintype "power_in"))
      (node (ref "IC3") (pin "2") (pinfunction "GND_2") (pintype "bidirectional"))
      (node (ref "IC4") (pin "3") (pinfunction "VSS_3") (pintype "bidirectional"))
      (node (ref "IC5") (pin "2") (pinfunction "-IN_2") (pintype "input"))
      (node (ref "IC5") (pin "4") (pinfunction "-IN_4") (pintype "input"))
      (node (ref "IC5") (pin "5") (pinfunction "V-_5") (pintype "bidirectional"))
      (node (ref "IC6") (pin "11") (pinfunction "V-_11") (pintype "bidirectional"))
      (node (ref "IC6") (pin "12") (pinfunction "+IN_12") (pintype "input"))
      (node (ref "IC6") (pin "13") (pinfunction "-IN_13") (pintype "input"))
      (node (ref "IC7") (pin "3") (pinfunction "V-_3") (pintype "bidirectional"))
      (node (ref "IC8") (pin "2") (pinfunction "DGND0_2") (pintype "bidirectional"))
      (node (ref "IC8") (pin "20") (pinfunction "AGND0_20") (pintype "bidirectional"))
      (node (ref "IC8") (pin "21") (pinfunction "AGND1_21") (pintype "bidirectional"))
      (node (ref "IC8") (pin "24") (pinfunction "DGND1_24") (pintype "bidirectional"))
      (node (ref "IC9") (pin "10") (pinfunction "VSS_10") (pintype "bidirectional"))
      (node (ref "JP2") (pin "1") (pinfunction "1_1") (pintype "passive"))
      (node (ref "JP4") (pin "5") (pinfunction "5_5") (pintype "passive"))
      (node (ref "K1") (pin "1") (pinfunction "P_1") (pintype "passive"))
      (node (ref "K2") (pin "1") (pinfunction "P_1") (pintype "passive"))
      (node (ref "K3") (pin "1") (pinfunction "P_1") (pintype "passive"))
      (node (ref "LED3") (pin "C") (pinfunction "C_C") (pintype "passive"))
      (node (ref "Q1") (pin "2") (pinfunction "E_2") (pintype "bidirectional"))
      (node (ref "Q3") (pin "2") (pinfunction "E_2") (pintype "passive"))
      (node (ref "Q4") (pin "E") (pinfunction "E_E") (pintype "passive"))
      (node (ref "R10") (pin "1") (pinfunction "1_1") (pintype "passive"))
      (node (ref "R102") (pin "2") (pinfunction "2_2") (pintype "passive"))
      (node (ref "R11") (pin "1") (pinfunction "1_1") (pintype "passive"))
      (node (ref "R15") (pin "1") (pinfunction "1_1") (pintype "passive"))
      (node (ref "R23") (pin "1") (pinfunction "1_1") (pintype "passive"))
      (node (ref "R3") (pin "1") (pinfunction "1_1") (pintype "passive"))
      (node (ref "R31") (pin "1") (pinfunction "1_1") (pintype "passive"))
      (node (ref "R42") (pin "1") (pinfunction "1_1") (pintype "passive"))
      (node (ref "R54") (pin "1") (pinfunction "1_1") (pintype "passive"))
      (node (ref "R60") (pin "1") (pinfunction "1_1") (pintype "passive"))
      (node (ref "R67") (pin "1") (pinfunction "1_1") (pintype "passive"))
      (node (ref "S1") (pin "1") (pinfunction "O_1") (pintype "passive"))
      (node (ref "SV1") (pin "5") (pinfunction "GND/5_5") (pintype "bidirectional"))
      (node (ref "SV1") (pin "TAB0") (pinfunction "SHLD0_TAB0") (pintype "bidirectional"))
      (node (ref "SV1") (pin "TAB1") (pinfunction "SHLD1_TAB1") (pintype "bidirectional"))
      (node (ref "SV1") (pin "TAB2") (pinfunction "SHLD2_TAB2") (pintype "bidirectional"))
      (node (ref "SV1") (pin "TAB3") (pinfunction "SHLD3_TAB3") (pintype "bidirectional"))
      (node (ref "SV5") (pin "5") (pinfunction "5_5") (pintype "passive"))
      (node (ref "U$7") (pin "4") (pinfunction "~{EN}_4") (pintype "bidirectional"))
      (node (ref "U$7") (pin "5") (pinfunction "GND_5") (pintype "power_in"))
      (node (ref "U$7") (pin "9") (pinfunction "EP_9") (pintype "power_in"))
      (node (ref "U$7") (pin "V1") (pinfunction "V1_V1") (pintype "power_in"))
      (node (ref "U$9") (pin "1") (pinfunction "NEG_1") (pintype "power_in"))
      (node (ref "U2") (pin "10") (pinfunction "GND_10") (pintype "power_in"))
      (node (ref "U2") (pin "20") (pinfunction "GND_20") (pintype "power_in"))
      (node (ref "U2") (pin "29") (pinfunction "GND_29") (pintype "power_in"))
      (node (ref "U2") (pin "3") (pinfunction "GND_3") (pintype "power_in"))
      (node (ref "U2") (pin "41") (pinfunction "GND_41") (pintype "power_in"))
      (node (ref "U2") (pin "56") (pinfunction "GND_56") (pintype "power_in"))
      (node (ref "U2") (pin "66") (pinfunction "GND_66") (pintype "power_in"))
      (node (ref "U2") (pin "73") (pinfunction "GND_73") (pintype "power_in"))
      (node (ref "U2") (pin "82") (pinfunction "GND_82") (pintype "power_in"))
      (node (ref "U2") (pin "95") (pinfunction "GND_95") (pintype "power_in"))
      (node (ref "U3") (pin "1") (pinfunction "NC(GND)_1") (pintype "input"))
      (node (ref "U3") (pin "10") (pinfunction "BS0_10") (pintype "input"))
      (node (ref "U3") (pin "11") (pinfunction "BS1_11") (pintype "input"))
      (node (ref "U3") (pin "12") (pinfunction "BS2_12") (pintype "input"))
      (node (ref "U3") (pin "29") (pinfunction "VLSS_29") (pintype "power_in"))
      (node (ref "U3") (pin "30") (pinfunction "NC(GND)_30") (pintype "input"))
      (node (ref "U3") (pin "8") (pinfunction "VSS_8") (pintype "power_in"))
      (node (ref "U4") (pin "6") (pinfunction "GND_6") (pintype "bidirectional"))
      (node (ref "U4") (pin "CD1") (pinfunction "SHIELD_CD1") (pintype "bidirectional"))
      (node (ref "U4") (pin "CD2") (pinfunction "SHIELD_CD2") (pintype "bidirectional"))
      (node (ref "U4") (pin "GND1") (pinfunction "SHIELD_GND1") (pintype "bidirectional"))
      (node (ref "U4") (pin "GND3") (pinfunction "SHIELD_GND3") (pintype "bidirectional"))
      (node (ref "USB-MICRO") (pin "GND") (pinfunction "GND_GND") (pintype "bidirectional"))
    )
    (net (code "42") (name "JTAG_TCK") (class "Default")
      (node (ref "IC2") (pin "49") (pinfunction "PA14/JTCK/SWCLK/FT_49") (pintype "input"))
      (node (ref "JP4") (pin "4") (pinfunction "4_4") (pintype "passive"))
    )
    (net (code "43") (name "JTAG_TMS") (class "Default")
      (node (ref "IC2") (pin "46") (pinfunction "PA13/JTMS/SWDIO/FT_46") (pintype "input"))
      (node (ref "JP4") (pin "1") (pinfunction "1_1") (pintype "passive"))
    )
    (net (code "44") (name "JTRST") (class "Default")
      (node (ref "IC2") (pin "58") (pinfunction "PB6/I2C1_SCL/TIM4_CH1/USART1_TX/FT_58") (pintype "bidirectional"))
      (node (ref "TP31") (pin "1") (pinfunction "P$1_1") (pintype "bidirectional"))
    )
    (net (code "45") (name "LED_A") (class "Default")
      (node (ref "IC2") (pin "54") (pinfunction "PD2/TIM3_ETR/UART5_RX/SDIO_CMD/FT_54") (pintype "bidirectional"))
      (node (ref "LED_A_TP") (pin "1") (pinfunction "P$1_1") (pintype "bidirectional"))
      (node (ref "R65") (pin "1") (pinfunction "1_1") (pintype "passive"))
    )
    (net (code "46") (name "MISO") (class "Default")
      (node (ref "IC2") (pin "4") (pinfunction "PC15/OSC32_OUT_4") (pintype "bidirectional"))
      (node (ref "MISO_TP") (pin "1") (pinfunction "P$1_1") (pintype "bidirectional"))
      (node (ref "U2") (pin "15") (pinfunction "L24P_6_15") (pintype "bidirectional"))
    )
    (net (code "47") (name "MOSI") (class "Default")
      (node (ref "IC2") (pin "3") (pinfunction "PC14/OSC32_IN_3") (pintype "bidirectional"))
      (node (ref "MOSI_TP") (pin "1") (pinfunction "P$1_1") (pintype "bidirectional"))
      (node (ref "U2") (pin "14") (pinfunction "L40N_6_14") (pintype "bidirectional"))
    )
    (net (code "48") (name "MUXSEL_HIPKD") (class "Default")
      (node (ref "FPGA_NINIT_TP2") (pin "1") (pinfunction "P$1_1") (pintype "bidirectional"))
      (node (ref "IC11") (pin "12") (pinfunction "C4_12") (pintype "input"))
      (node (ref "IC2") (pin "40") (pinfunction "PC9/TIM8_CH4/SDIO_D1/TIM3_CH4/FT_40") (pintype "bidirectional"))
    )
    (net (code "49") (name "MUXSEL_HIRAW") (class "Default")
      (node (ref "IC11") (pin "6") (pinfunction "C3_6") (pintype "input"))
      (node (ref "IC2") (pin "28") (pinfunction "PB2/BOOT1/FT_28") (pintype "bidirectional"))
      (node (ref "TP33") (pin "1") (pinfunction "P$1_1") (pintype "bidirectional"))
    )
    (net (code "50") (name "MUXSEL_LOPKD") (class "Default")
      (node (ref "FPGA_NINIT_TP1") (pin "1") (pinfunction "P$1_1") (pintype "bidirectional"))
      (node (ref "IC11") (pin "5") (pinfunction "C2_5") (pintype "input"))
      (node (ref "IC2") (pin "39") (pinfunction "PC8/TIM8_CH3/SDIO_D0/TIM3_CH3/FT_39") (pintype "bidirectional"))
    )
    (net (code "51") (name "MUXSEL_LORAW") (class "Default")
      (node (ref "IC11") (pin "13") (pinfunction "C1_13") (pintype "input"))
      (node (ref "IC2") (pin "27") (pinfunction "PB1/ADC12_IN9/TIM3_CH4/TIM8_CH3N/TIM1_CH3N_27") (pintype "bidirectional"))
      (node (ref "TP34") (pin "1") (pinfunction "P$1_1") (pintype "bidirectional"))
    )
    (net (code "52") (name "N$58") (class "Default")
      (node (ref "SPARE_FPGA_TP") (pin "1") (pinfunction "P$1_1") (pintype "bidirectional"))
      (node (ref "U2") (pin "43") (pinfunction "L30P_4/D3_43") (pintype "bidirectional"))
    )
    (net (code "53") (name "NCS") (class "Default")
      (node (ref "IC2") (pin "53") (pinfunction "PC12/UART5_TX/SDIO_CK/USART3_CK/FT_53") (pintype "bidirectional"))
      (node (ref "NCS_TP") (pin "1") (pinfunction "P$1_1") (pintype "bidirectional"))
      (node (ref "U2") (pin "50") (pinfunction "L01N_4/VRP_4_50") (pintype "bidirectional"))
    )
    (net (code "54") (name "NRST") (class "Default")
      (node (ref "C56") (pin "1") (pinfunction "1_1") (pintype "passive"))
      (node (ref "IC2") (pin "7") (pinfunction "NRST_7") (pintype "input"))
      (node (ref "R5") (pin "2") (pinfunction "2_2") (pintype "passive"))
    )
    (net (code "55") (name "NTC") (class "Default")
      (node (ref "R43") (pin "1") (pinfunction "1_1") (pintype "passive"))
      (node (ref "TP16") (pin "1") (pinfunction "P$1_1") (pintype "bidirectional"))
      (node (ref "U$9") (pin "2") (pinfunction "NTC_2") (pintype "power_in"))
    )
    (net (code "56") (name "Net-(BAT1-+)") (class "Default")
      (node (ref "BAT1") (pin "PWR@1") (pinfunction "+_PWR@1") (pintype "power_in"))
      (node (ref "D4") (pin "1") (pinfunction "A_1") (pintype "passive"))
    )
    (net (code "57") (name "Net-(C16-Pad1)") (class "Default")
      (node (ref "C16") (pin "1") (pinfunction "1_1") (pintype "passive"))
      (node (ref "R16") (pin "2") (pinfunction "2_2") (pintype "passive"))
    )
    (net (code "58") (name "Net-(C42-Pad2)") (class "Default")
      (node (ref "C42") (pin "2") (pinfunction "2_2") (pintype "passive"))
      (node (ref "R35") (pin "1") (pinfunction "1_1") (pintype "passive"))
    )
    (net (code "59") (name "Net-(C43-Pad2)") (class "Default")
      (node (ref "C43") (pin "2") (pinfunction "2_2") (pintype "passive"))
      (node (ref "R32") (pin "1") (pinfunction "1_1") (pintype "passive"))
    )
    (net (code "60") (name "Net-(C57-Pad1)") (class "Default")
      (node (ref "C57") (pin "1") (pinfunction "1_1") (pintype "passive"))
      (node (ref "LED2") (pin "C") (pinfunction "C_C") (pintype "passive"))
      (node (ref "R24") (pin "1") (pinfunction "1_1") (pintype "passive"))
    )
    (net (code "61") (name "Net-(C58-Pad1)") (class "Default")
      (node (ref "C58") (pin "1") (pinfunction "1_1") (pintype "passive"))
      (node (ref "LED1") (pin "C") (pinfunction "C_C") (pintype "passive"))
      (node (ref "R25") (pin "1") (pinfunction "1_1") (pintype "passive"))
    )
    (net (code "62") (name "Net-(D1-A)") (class "Default")
      (node (ref "D1") (pin "1") (pinfunction "A_1") (pintype "passive"))
      (node (ref "R20") (pin "1") (pinfunction "1_1") (pintype "passive"))
      (node (ref "RLY1") (pin "10") (pinfunction "NC_10") (pintype "passive"))
    )
    (net (code "63") (name "Net-(D1-C)") (class "Default")
      (node (ref "C11") (pin "1") (pinfunction "1_1") (pintype "passive"))
      (node (ref "C12") (pin "1") (pinfunction "1_1") (pintype "passive"))
      (node (ref "D1") (pin "3") (pinfunction "C_3") (pintype "passive"))
      (node (ref "D11") (pin "3") (pinfunction "C_3") (pintype "passive"))
      (node (ref "R11") (pin "2") (pinfunction "2_2") (pintype "passive"))
      (node (ref "R30") (pin "1") (pinfunction "1_1") (pintype "passive"))
    )
    (net (code "64") (name "Net-(D2-A)") (class "Default")
      (node (ref "C14") (pin "2") (pinfunction "2_2") (pintype "passive"))
      (node (ref "D2") (pin "1") (pinfunction "A_1") (pintype "passive"))
      (node (ref "D3") (pin "3") (pinfunction "C_3") (pintype "passive"))
    )
    (net (code "65") (name "Net-(D4-C)") (class "Default")
      (node (ref "C9") (pin "2") (pinfunction "2_2") (pintype "passive"))
      (node (ref "D4") (pin "3") (pinfunction "C_3") (pintype "passive"))
      (node (ref "D5") (pin "3") (pinfunction "C_3") (pintype "passive"))
      (node (ref "IC2") (pin "1") (pinfunction "VBAT_1") (pintype "passive"))
    )
    (net (code "66") (name "Net-(D6-P$4)") (class "Default")
      (node (ref "D6") (pin "4") (pinfunction "P$4_4") (pintype "passive"))
      (node (ref "F1") (pin "2") (pinfunction "2_2") (pintype "passive"))
      (node (ref "SV1") (pin "1") (pinfunction "VBUS/1_1") (pintype "bidirectional"))
      (node (ref "USB-MICRO") (pin "VBUS") (pinfunction "VBUS_VBUS") (pintype "bidirectional"))
    )
    (net (code "67") (name "Net-(D7-A)") (class "Default")
      (node (ref "D7") (pin "1") (pinfunction "A_1") (pintype "passive"))
      (node (ref "Q1") (pin "3") (pinfunction "C_3") (pintype "bidirectional"))
      (node (ref "RLY1") (pin "12") (pinfunction "P$2_12") (pintype "passive"))
    )
    (net (code "68") (name "Net-(D10-C)") (class "Default")
      (node (ref "C15") (pin "1") (pinfunction "1_1") (pintype "passive"))
      (node (ref "D10") (pin "3") (pinfunction "C_3") (pintype "passive"))
      (node (ref "D2") (pin "3") (pinfunction "C_3") (pintype "passive"))
      (node (ref "R15") (pin "2") (pinfunction "2_2") (pintype "passive"))
      (node (ref "R16") (pin "1") (pinfunction "1_1") (pintype "passive"))
      (node (ref "R41") (pin "1") (pinfunction "1_1") (pintype "passive"))
    )
    (net (code "69") (name "Net-(FB1-A)") (class "Default")
      (node (ref "C65") (pin "1") (pinfunction "1_1") (pintype "passive"))
      (node (ref "C70") (pin "+") (pinfunction "+_+") (pintype "passive"))
      (node (ref "FB1") (pin "1") (pinfunction "A_1") (pintype "bidirectional"))
      (node (ref "IC8") (pin "18") (pinfunction "VDDA2_18") (pintype "bidirectional"))
    )
    (net (code "70") (name "Net-(FB2\\-A)") (class "Default")
      (node (ref "C67") (pin "1") (pinfunction "1_1") (pintype "passive"))
      (node (ref "C69") (pin "+") (pinfunction "+_+") (pintype "passive"))
      (node (ref "FB2\\") (pin "1") (pinfunction "A_1") (pintype "bidirectional"))
      (node (ref "IC8") (pin "14") (pinfunction "VDDA0_14") (pintype "bidirectional"))
    )
    (net (code "71") (name "Net-(FB3-A)") (class "Default")
      (node (ref "C66") (pin "1") (pinfunction "1_1") (pintype "passive"))
      (node (ref "C68") (pin "+") (pinfunction "+_+") (pintype "passive"))
      (node (ref "FB3") (pin "1") (pinfunction "A_1") (pintype "bidirectional"))
      (node (ref "IC8") (pin "15") (pinfunction "VDDA1_15") (pintype "bidirectional"))
    )
    (net (code "72") (name "Net-(IC1B-L)") (class "Default")
      (node (ref "IC1") (pin "3") (pinfunction "L_3") (pintype "input"))
      (node (ref "L2") (pin "P$2") (pinfunction "2_P$2") (pintype "passive"))
    )
    (net (code "73") (name "Net-(IC1B-UVLO)") (class "Default")
      (node (ref "C76") (pin "2") (pinfunction "2_2") (pintype "passive"))
      (node (ref "IC1") (pin "7") (pinfunction "UVLO_7") (pintype "input"))
      (node (ref "R55") (pin "1") (pinfunction "1_1") (pintype "passive"))
      (node (ref "R60") (pin "2") (pinfunction "2_2") (pintype "passive"))
    )
    (net (code "74") (name "Net-(IC1B-VAUX)") (class "Default")
      (node (ref "C63") (pin "1") (pinfunction "1_1") (pintype "passive"))
      (node (ref "IC1") (pin "1") (pinfunction "VAUX_1") (pintype "bidirectional"))
    )
    (net (code "75") (name "Net-(IC2-BOOT0)") (class "Default")
      (node (ref "IC2") (pin "60") (pinfunction "BOOT0_60") (pintype "input"))
      (node (ref "R4") (pin "2") (pinfunction "2_2") (pintype "passive"))
    )
    (net (code "76") (name "Net-(IC2-PA11{slash}UART1CTS{slash}CNRX{slash}TIM1CH4{slash}USBD-{slash}FT)") (class "Default")
      (node (ref "IC2") (pin "44") (pinfunction "PA11/UART1CTS/CNRX/TIM1CH4/USBD-/FT_44") (pintype "bidirectional"))
      (node (ref "R7") (pin "2") (pinfunction "2_2") (pintype "passive"))
    )
    (net (code "77") (name "Net-(IC2-PA12{slash}UART1RTS{slash}CNTX{slash}TIM1ETR{slash}USBD+{slash}FT)") (class "Default")
      (node (ref "IC2") (pin "45") (pinfunction "PA12/UART1RTS/CNTX/TIM1ETR/USBD+/FT_45") (pintype "bidirectional"))
      (node (ref "R8") (pin "2") (pinfunction "2_2") (pintype "passive"))
    )
    (net (code "78") (name "Net-(IC2-PC3{slash}ADC123_IN13)") (class "Default")
      (node (ref "IC2") (pin "11") (pinfunction "PC3/ADC123_IN13_11") (pintype "bidirectional"))
      (node (ref "JP_AH") (pin "3") (pinfunction "3_3") (pintype "passive"))
    )
    (net (code "79") (name "Net-(IC2-PC4{slash}ADC12_IN14)") (class "Default")
      (node (ref "IC2") (pin "24") (pinfunction "PC4/ADC12_IN14_24") (pintype "bidirectional"))
      (node (ref "JP_AL") (pin "3") (pinfunction "3_3") (pintype "passive"))
    )
    (net (code "80") (name "Net-(IC2-PD0{slash}OSC_IN{slash}FSMC_D2{slash}CAN_RX{slash}FT)") (class "Default")
      (node (ref "C53") (pin "2") (pinfunction "2_2") (pintype "passive"))
      (node (ref "IC2") (pin "5") (pinfunction "PD0/OSC_IN/FSMC_D2/CAN_RX/FT_5") (pintype "bidirectional"))
      (node (ref "Y1") (pin "P$1") (pinfunction "1_P$1") (pintype "passive"))
    )
    (net (code "81") (name "Net-(IC2-PD1{slash}OSC_OUT{slash}FSMC_D3{slash}CAN_TX{slash}FT)") (class "Default")
      (node (ref "IC2") (pin "6") (pinfunction "PD1/OSC_OUT/FSMC_D3/CAN_TX/FT_6") (pintype "bidirectional"))
      (node (ref "R6") (pin "2") (pinfunction "2_2") (pintype "passive"))
    )
    (net (code "82") (name "Net-(IC3-NR)") (class "Default")
      (node (ref "C74") (pin "1") (pinfunction "1_1") (pintype "passive"))
      (node (ref "IC3") (pin "4") (pinfunction "NR_4") (pintype "bidirectional"))
    )
    (net (code "83") (name "Net-(IC4-A)") (class "Default")
      (node (ref "C2") (pin "1") (pinfunction "1_1") (pintype "passive"))
      (node (ref "IC4") (pin "2") (pinfunction "A_2") (pintype "bidirectional"))
      (node (ref "R1") (pin "1") (pinfunction "1_1") (pintype "passive"))
      (node (ref "XT1") (pin "A") (pinfunction "A_A") (pintype "bidirectional"))
    )
    (net (code "84") (name "Net-(IC4-Y)") (class "Default")
      (node (ref "IC4") (pin "4") (pinfunction "Y_4") (pintype "bidirectional"))
      (node (ref "R2") (pin "1") (pinfunction "1_1") (pintype "passive"))
    )
    (net (code "85") (name "Net-(IC5A-+IN)") (class "Default")
      (node (ref "IC5") (pin "1") (pinfunction "+IN_1") (pintype "input"))
      (node (ref "R20") (pin "2") (pinfunction "2_2") (pintype "passive"))
    )
    (net (code "86") (name "Net-(IC5B-+IN)") (class "Default")
      (node (ref "IC5") (pin "3") (pinfunction "+IN_3") (pintype "input"))
      (node (ref "R21") (pin "2") (pinfunction "2_2") (pintype "passive"))
    )
    (net (code "87") (name "Net-(IC6A-+IN)") (class "Default")
      (node (ref "IC6") (pin "3") (pinfunction "+IN_3") (pintype "input"))
      (node (ref "R10") (pin "2") (pinfunction "2_2") (pintype "passive"))
      (node (ref "R9") (pin "1") (pinfunction "1_1") (pintype "passive"))
    )
    (net (code "88") (name "Net-(IC6B-+IN)") (class "Default")
      (node (ref "C12") (pin "2") (pinfunction "2_2") (pintype "passive"))
      (node (ref "IC6") (pin "5") (pinfunction "+IN_5") (pintype "input"))
      (node (ref "R12") (pin "2") (pinfunction "2_2") (pintype "passive"))
    )
    (net (code "89") (name "Net-(IC6B--IN)") (class "Default")
      (node (ref "C13") (pin "1") (pinfunction "1_1") (pintype "passive"))
      (node (ref "IC6") (pin "6") (pinfunction "-IN_6") (pintype "input"))
      (node (ref "R13") (pin "2") (pinfunction "2_2") (pintype "passive"))
      (node (ref "R14") (pin "1") (pinfunction "1_1") (pintype "passive"))
    )
    (net (code "90") (name "Net-(IC6C-+IN)") (class "Default")
      (node (ref "C16") (pin "2") (pinfunction "2_2") (pintype "passive"))
      (node (ref "IC6") (pin "10") (pinfunction "+IN_10") (pintype "input"))
      (node (ref "R17") (pin "2") (pinfunction "2_2") (pintype "passive"))
      (node (ref "R36") (pin "2") (pinfunction "2_2") (pintype "passive"))
      (node (ref "R37") (pin "2") (pinfunction "2_2") (pintype "passive"))
    )
    (net (code "91") (name "Net-(IC6C--IN)") (class "Default")
      (node (ref "C17") (pin "1") (pinfunction "1_1") (pintype "passive"))
      (node (ref "IC6") (pin "9") (pinfunction "-IN_9") (pintype "input"))
      (node (ref "R18") (pin "1") (pinfunction "1_1") (pintype "passive"))
      (node (ref "R19") (pin "2") (pinfunction "2_2") (pintype "passive"))
    )
    (net (code "92") (name "Net-(IC7-OUT)") (class "Default")
      (node (ref "IC7") (pin "1") (pinfunction "OUT_1") (pintype "bidirectional"))
      (node (ref "R5") (pin "1") (pinfunction "1_1") (pintype "passive"))
    )
    (net (code "93") (name "Net-(IC8-REFB)") (class "Default")
      (node (ref "C18") (pin "1") (pinfunction "1_1") (pintype "passive"))
      (node (ref "IC8") (pin "23") (pinfunction "REFB_23") (pintype "bidirectional"))
      (node (ref "R53") (pin "1") (pinfunction "1_1") (pintype "passive"))
      (node (ref "R54") (pin "2") (pinfunction "2_2") (pintype "passive"))
    )
    (net (code "94") (name "Net-(IC8-REFT)") (class "Default")
      (node (ref "C19") (pin "1") (pinfunction "1_1") (pintype "passive"))
      (node (ref "IC8") (pin "17") (pinfunction "REFT_17") (pintype "bidirectional"))
      (node (ref "R52") (pin "1") (pinfunction "1_1") (pintype "passive"))
      (node (ref "R53") (pin "2") (pinfunction "2_2") (pintype "passive"))
    )
    (net (code "95") (name "Net-(IC9-1Y1)") (class "Default")
      (node (ref "IC9") (pin "12") (pinfunction "1Y4_12") (pintype "bidirectional"))
      (node (ref "IC9") (pin "14") (pinfunction "1Y3_14") (pintype "bidirectional"))
      (node (ref "IC9") (pin "16") (pinfunction "1Y2_16") (pintype "bidirectional"))
      (node (ref "IC9") (pin "18") (pinfunction "1Y1_18") (pintype "bidirectional"))
      (node (ref "R27") (pin "1") (pinfunction "1_1") (pintype "passive"))
    )
    (net (code "96") (name "Net-(IC9-2Y1)") (class "Default")
      (node (ref "IC9") (pin "9") (pinfunction "2Y1_9") (pintype "bidirectional"))
      (node (ref "R45") (pin "1") (pinfunction "1_1") (pintype "passive"))
    )
    (net (code "97") (name "Net-(IC9-2Y2)") (class "Default")
      (node (ref "IC9") (pin "3") (pinfunction "2Y4_3") (pintype "bidirectional"))
      (node (ref "IC9") (pin "5") (pinfunction "2Y3_5") (pintype "bidirectional"))
      (node (ref "IC9") (pin "7") (pinfunction "2Y2_7") (pintype "bidirectional"))
      (node (ref "R22") (pin "1") (pinfunction "1_1") (pintype "passive"))
    )
    (net (code "98") (name "Net-(IC10-1Y1)") (class "Default")
      (node (ref "IC10") (pin "12") (pinfunction "1Y4_12") (pintype "bidirectional"))
      (node (ref "IC10") (pin "14") (pinfunction "1Y3_14") (pintype "bidirectional"))
      (node (ref "IC10") (pin "16") (pinfunction "1Y2_16") (pintype "bidirectional"))
      (node (ref "IC10") (pin "18") (pinfunction "1Y1_18") (pintype "bidirectional"))
      (node (ref "R28") (pin "1") (pinfunction "1_1") (pintype "passive"))
    )
    (net (code "99") (name "Net-(IC10-2Y1)") (class "Default")
      (node (ref "IC10") (pin "9") (pinfunction "2Y1_9") (pintype "bidirectional"))
      (node (ref "R46") (pin "1") (pinfunction "1_1") (pintype "passive"))
    )
    (net (code "100") (name "Net-(IC10-2Y2)") (class "Default")
      (node (ref "IC10") (pin "3") (pinfunction "2Y4_3") (pintype "bidirectional"))
      (node (ref "IC10") (pin "5") (pinfunction "2Y3_5") (pintype "bidirectional"))
      (node (ref "IC10") (pin "7") (pinfunction "2Y2_7") (pintype "bidirectional"))
      (node (ref "R29") (pin "1") (pinfunction "1_1") (pintype "passive"))
    )
    (net (code "101") (name "Net-(IC11-A1)") (class "Default")
      (node (ref "C41") (pin "2") (pinfunction "2_2") (pintype "passive"))
      (node (ref "IC11") (pin "1") (pinfunction "A1_1") (pintype "passive"))
      (node (ref "IC14") (pin "7") (pinfunction "OUT_7") (pintype "output"))
      (node (ref "R34") (pin "2") (pinfunction "2_2") (pintype "passive"))
    )
    (net (code "102") (name "Net-(IC11-A2)") (class "Default")
      (node (ref "C13") (pin "2") (pinfunction "2_2") (pintype "passive"))
      (node (ref "IC11") (pin "4") (pinfunction "A2_4") (pintype "passive"))
      (node (ref "IC6") (pin "7") (pinfunction "OUT_7") (pintype "output"))
      (node (ref "R14") (pin "2") (pinfunction "2_2") (pintype "passive"))
    )
    (net (code "103") (name "Net-(IC11-A3)") (class "Default")
      (node (ref "C40") (pin "2") (pinfunction "2_2") (pintype "passive"))
      (node (ref "IC11") (pin "8") (pinfunction "A3_8") (pintype "passive"))
      (node (ref "IC14") (pin "1") (pinfunction "OUT_1") (pintype "output"))
      (node (ref "R33") (pin "2") (pinfunction "2_2") (pintype "passive"))
    )
    (net (code "104") (name "Net-(IC11-A4)") (class "Default")
      (node (ref "C17") (pin "2") (pinfunction "2_2") (pintype "passive"))
      (node (ref "IC11") (pin "11") (pinfunction "A4_11") (pintype "passive"))
      (node (ref "IC6") (pin "8") (pinfunction "OUT_8") (pintype "output"))
      (node (ref "R18") (pin "2") (pinfunction "2_2") (pintype "passive"))
    )
    (net (code "105") (name "Net-(IC13-NR)") (class "Default")
      (node (ref "C75") (pin "1") (pinfunction "1_1") (pintype "passive"))
      (node (ref "IC13") (pin "4") (pinfunction "NR_4") (pintype "bidirectional"))
    )
    (net (code "106") (name "Net-(IC14A-+IN)") (class "Default")
      (node (ref "IC14") (pin "3") (pinfunction "+IN_3") (pintype "input"))
      (node (ref "R35") (pin "2") (pinfunction "2_2") (pintype "passive"))
      (node (ref "R49") (pin "2") (pinfunction "2_2") (pintype "passive"))
    )
    (net (code "107") (name "Net-(IC14A--IN)") (class "Default")
      (node (ref "C40") (pin "1") (pinfunction "1_1") (pintype "passive"))
      (node (ref "IC14") (pin "2") (pinfunction "-IN_2") (pintype "input"))
      (node (ref "R33") (pin "1") (pinfunction "1_1") (pintype "passive"))
      (node (ref "R51") (pin "2") (pinfunction "2_2") (pintype "passive"))
    )
    (net (code "108") (name "Net-(IC14B-+IN)") (class "Default")
      (node (ref "IC14") (pin "5") (pinfunction "+IN_5") (pintype "input"))
      (node (ref "R32") (pin "2") (pinfunction "2_2") (pintype "passive"))
      (node (ref "R48") (pin "2") (pinfunction "2_2") (pintype "passive"))
    )
    (net (code "109") (name "Net-(IC14B--IN)") (class "Default")
      (node (ref "C41") (pin "1") (pinfunction "1_1") (pintype "passive"))
      (node (ref "IC14") (pin "6") (pinfunction "-IN_6") (pintype "input"))
      (node (ref "R34") (pin "1") (pinfunction "1_1") (pintype "passive"))
      (node (ref "R50") (pin "2") (pinfunction "2_2") (pintype "passive"))
    )
    (net (code "110") (name "Net-(LED3-PadA)") (class "Default")
      (node (ref "LED3") (pin "A") (pinfunction "A_A") (pintype "passive"))
      (node (ref "R65") (pin "2") (pinfunction "2_2") (pintype "passive"))
    )
    (net (code "111") (name "Net-(Q1-B)") (class "Default")
      (node (ref "Q1") (pin "1") (pinfunction "B_1") (pintype "bidirectional"))
      (node (ref "R40") (pin "2") (pinfunction "2_2") (pintype "passive"))
    )
    (net (code "112") (name "Net-(Q2-PadB)") (class "Default")
      (node (ref "Q2") (pin "B") (pinfunction "B_B") (pintype "passive"))
      (node (ref "Q4") (pin "C") (pinfunction "C_C") (pintype "passive"))
      (node (ref "R56") (pin "2") (pinfunction "2_2") (pintype "passive"))
      (node (ref "R67") (pin "2") (pinfunction "2_2") (pintype "passive"))
    )
    (net (code "113") (name "Net-(Q2-PadE)") (class "Default")
      (node (ref "Q2") (pin "E") (pinfunction "E_E") (pintype "passive"))
      (node (ref "R68") (pin "2") (pinfunction "2_2") (pintype "passive"))
    )
    (net (code "114") (name "Net-(Q3-B)") (class "Default")
      (node (ref "Q3") (pin "1") (pinfunction "B_1") (pintype "passive"))
      (node (ref "R319") (pin "1") (pinfunction "1_1") (pintype "passive"))
    )
    (net (code "115") (name "Net-(Q3-C)") (class "Default")
      (node (ref "BUZ1") (pin "2") (pinfunction "2_2") (pintype "passive"))
      (node (ref "Q3") (pin "3") (pinfunction "C_3") (pintype "passive"))
    )
    (net (code "116") (name "Net-(Q4-PadB)") (class "Default")
      (node (ref "Q4") (pin "B") (pinfunction "B_B") (pintype "passive"))
      (node (ref "R57") (pin "2") (pinfunction "2_2") (pintype "passive"))
      (node (ref "R58") (pin "2") (pinfunction "2_2") (pintype "passive"))
    )
    (net (code "117") (name "Net-(R37-Pad1)") (class "Default")
      (node (ref "R37") (pin "1") (pinfunction "1_1") (pintype "passive"))
      (node (ref "R38") (pin "2") (pinfunction "2_2") (pintype "passive"))
    )
    (net (code "118") (name "Net-(RLY1A-NC)") (class "Default")
      (node (ref "C14") (pin "1") (pinfunction "1_1") (pintype "passive"))
      (node (ref "R21") (pin "1") (pinfunction "1_1") (pintype "passive"))
      (node (ref "RLY1") (pin "3") (pinfunction "NC_3") (pintype "passive"))
    )
    (net (code "119") (name "Net-(RLY1A-NO)") (class "Default")
      (node (ref "C42") (pin "1") (pinfunction "1_1") (pintype "passive"))
      (node (ref "RLY1") (pin "5") (pinfunction "NO_5") (pintype "passive"))
    )
    (net (code "120") (name "Net-(RLY1B-NO)") (class "Default")
      (node (ref "C43") (pin "1") (pinfunction "1_1") (pintype "passive"))
      (node (ref "RLY1") (pin "8") (pinfunction "NO_8") (pintype "passive"))
    )
    (net (code "121") (name "Net-(SV2-PIN1)") (class "Default")
      (node (ref "R22") (pin "2") (pinfunction "2_2") (pintype "passive"))
      (node (ref "R28") (pin "2") (pinfunction "2_2") (pintype "passive"))
      (node (ref "R46") (pin "2") (pinfunction "2_2") (pintype "passive"))
      (node (ref "SV2") (pin "1") (pinfunction "PIN1_1") (pintype "passive"))
      (node (ref "TP5") (pin "1") (pinfunction "P$1_1") (pintype "bidirectional"))
    )
    (net (code "122") (name "Net-(SV2-PIN3)") (class "Default")
      (node (ref "R27") (pin "2") (pinfunction "2_2") (pintype "passive"))
      (node (ref "R29") (pin "2") (pinfunction "2_2") (pintype "passive"))
      (node (ref "R45") (pin "2") (pinfunction "2_2") (pintype "passive"))
      (node (ref "SV2") (pin "3") (pinfunction "PIN3_3") (pintype "passive"))
      (node (ref "TP4") (pin "1") (pinfunction "P$1_1") (pintype "bidirectional"))
    )
    (net (code "123") (name "Net-(U$7A-TEMP)") (class "Default")
      (node (ref "C60") (pin "1") (pinfunction "1_1") (pintype "passive"))
      (node (ref "R26") (pin "2") (pinfunction "2_2") (pintype "passive"))
      (node (ref "R43") (pin "2") (pinfunction "2_2") (pintype "passive"))
      (node (ref "U$7") (pin "6") (pinfunction "TEMP_6") (pintype "bidirectional"))
    )
    (net (code "124") (name "Net-(U$7A-VREF)") (class "Default")
      (node (ref "R26") (pin "1") (pinfunction "1_1") (pintype "passive"))
      (node (ref "U$7") (pin "7") (pinfunction "VREF_7") (pintype "bidirectional"))
    )
    (net (code "125") (name "Net-(U$7A-~{GRN})") (class "Default")
      (node (ref "R24") (pin "2") (pinfunction "2_2") (pintype "passive"))
      (node (ref "U$7") (pin "2") (pinfunction "~{GRN}_2") (pintype "bidirectional"))
    )
    (net (code "126") (name "Net-(U$7A-~{RED})") (class "Default")
      (node (ref "R25") (pin "2") (pinfunction "2_2") (pintype "passive"))
      (node (ref "U$7") (pin "3") (pinfunction "~{RED}_3") (pintype "bidirectional"))
    )
    (net (code "127") (name "Net-(U1-A)") (class "Default")
      (node (ref "F1") (pin "1") (pinfunction "1_1") (pintype "passive"))
      (node (ref "U1") (pin "1") (pinfunction "A_1") (pintype "bidirectional"))
    )
    (net (code "128") (name "Net-(U2A-L40N_2)") (class "Default")
      (node (ref "R44") (pin "2") (pinfunction "2_2") (pintype "passive"))
      (node (ref "U2") (pin "65") (pinfunction "L40N_2_65") (pintype "bidirectional"))
    )
    (net (code "129") (name "Net-(U2A-L40P_2{slash}VREF_2)") (class "Default")
      (node (ref "R39") (pin "2") (pinfunction "2_2") (pintype "passive"))
      (node (ref "U2") (pin "64") (pinfunction "L40P_2/VREF_2_64") (pintype "bidirectional"))
    )
    (net (code "130") (name "Net-(U3-C1N)") (class "Default")
      (node (ref "C5") (pin "2") (pinfunction "2_2") (pintype "passive"))
      (node (ref "U3") (pin "5") (pinfunction "C1N_5") (pintype "input"))
    )
    (net (code "131") (name "Net-(U3-C1P)") (class "Default")
      (node (ref "C5") (pin "1") (pinfunction "1_1") (pintype "passive"))
      (node (ref "U3") (pin "4") (pinfunction "C1P_4") (pintype "input"))
    )
    (net (code "132") (name "Net-(U3-C2N)") (class "Default")
      (node (ref "C4") (pin "2") (pinfunction "2_2") (pintype "passive"))
      (node (ref "U3") (pin "3") (pinfunction "C2N_3") (pintype "input"))
    )
    (net (code "133") (name "Net-(U3-C2P)") (class "Default")
      (node (ref "C4") (pin "1") (pinfunction "1_1") (pintype "passive"))
      (node (ref "U3") (pin "2") (pinfunction "C2P_2") (pintype "input"))
    )
    (net (code "134") (name "Net-(U3-IREF)") (class "Default")
      (node (ref "R3") (pin "2") (pinfunction "2_2") (pintype "passive"))
      (node (ref "U3") (pin "26") (pinfunction "IREF_26") (pintype "input"))
    )
    (net (code "135") (name "Net-(U3-VCC)") (class "Default")
      (node (ref "C6") (pin "1") (pinfunction "1_1") (pintype "passive"))
      (node (ref "U3") (pin "28") (pinfunction "VCC_28") (pintype "power_in"))
    )
    (net (code "136") (name "Net-(U3-VCOMH)") (class "Default")
      (node (ref "C8") (pin "1") (pinfunction "1_1") (pintype "passive"))
      (node (ref "U3") (pin "27") (pinfunction "VCOMH_27") (pintype "output"))
    )
    (net (code "137") (name "Net-(Y1-2)") (class "Default")
      (node (ref "C54") (pin "2") (pinfunction "2_2") (pintype "passive"))
      (node (ref "R6") (pin "1") (pinfunction "1_1") (pintype "passive"))
      (node (ref "Y1") (pin "P$2") (pinfunction "2_P$2") (pintype "passive"))
    )
    (net (code "138") (name "ONOFF") (class "Default")
      (node (ref "IC1") (pin "6") (pinfunction "EN_6") (pintype "input"))
      (node (ref "S1") (pin "2") (pinfunction "P_2") (pintype "passive"))
    )
    (net (code "139") (name "PCK0") (class "Default")
      (node (ref "IC2") (pin "43") (pinfunction "PA10/USART1_RX/TIM1_CH3/FT_43") (pintype "bidirectional"))
      (node (ref "PCK0_TP") (pin "1") (pinfunction "P$1_1") (pintype "bidirectional"))
      (node (ref "U2") (pin "88") (pinfunction "L32N_1/GCLK5_88") (pintype "bidirectional"))
    )
    (net (code "140") (name "PS") (class "Default")
      (node (ref "IC1") (pin "8") (pinfunction "PS_8") (pintype "input"))
      (node (ref "JP2") (pin "2") (pinfunction "2_2") (pintype "passive"))
    )
    (net (code "141") (name "PWR_HI") (class "Default")
      (node (ref "IC10") (pin "13") (pinfunction "2A2_13") (pintype "bidirectional"))
      (node (ref "IC10") (pin "15") (pinfunction "2A3_15") (pintype "bidirectional"))
      (node (ref "IC10") (pin "17") (pinfunction "2A4_17") (pintype "bidirectional"))
      (node (ref "IC9") (pin "11") (pinfunction "2A1_11") (pintype "bidirectional"))
      (node (ref "IC9") (pin "2") (pinfunction "1A1_2") (pintype "bidirectional"))
      (node (ref "IC9") (pin "4") (pinfunction "1A2_4") (pintype "bidirectional"))
      (node (ref "IC9") (pin "6") (pinfunction "1A3_6") (pintype "bidirectional"))
      (node (ref "IC9") (pin "8") (pinfunction "1A4_8") (pintype "bidirectional"))
      (node (ref "PWR_HI_TP") (pin "1") (pinfunction "P$1_1") (pintype "bidirectional"))
      (node (ref "U2") (pin "61") (pinfunction "L24N_3_61") (pintype "bidirectional"))
    )
    (net (code "142") (name "PWR_LO") (class "Default")
      (node (ref "IC10") (pin "11") (pinfunction "2A1_11") (pintype "bidirectional"))
      (node (ref "IC10") (pin "2") (pinfunction "1A1_2") (pintype "bidirectional"))
      (node (ref "IC10") (pin "4") (pinfunction "1A2_4") (pintype "bidirectional"))
      (node (ref "IC10") (pin "6") (pinfunction "1A3_6") (pintype "bidirectional"))
      (node (ref "IC10") (pin "8") (pinfunction "1A4_8") (pintype "bidirectional"))
      (node (ref "IC9") (pin "13") (pinfunction "2A2_13") (pintype "bidirectional"))
      (node (ref "IC9") (pin "15") (pinfunction "2A3_15") (pintype "bidirectional"))
      (node (ref "IC9") (pin "17") (pinfunction "2A4_17") (pintype "bidirectional"))
      (node (ref "PWR_LO_TP") (pin "1") (pinfunction "P$1_1") (pintype "bidirectional"))
      (node (ref "U2") (pin "62") (pinfunction "L40P_3_62") (pintype "bidirectional"))
    )
    (net (code "143") (name "PWR_OE1") (class "Default")
      (node (ref "IC9") (pin "1") (pinfunction "1NOE_1") (pintype "bidirectional"))
      (node (ref "OE1_TP") (pin "1") (pinfunction "P$1_1") (pintype "bidirectional"))
      (node (ref "U2") (pin "44") (pinfunction "L30N_4/D2_44") (pintype "bidirectional"))
    )
    (net (code "144") (name "PWR_OE2") (class "Default")
      (node (ref "IC10") (pin "1") (pinfunction "1NOE_1") (pintype "bidirectional"))
      (node (ref "OE2_TP") (pin "1") (pinfunction "P$1_1") (pintype "bidirectional"))
      (node (ref "U2") (pin "47") (pinfunction "L27P_4/D1_47") (pintype "bidirectional"))
    )
    (net (code "145") (name "PWR_OE3") (class "Default")
      (node (ref "IC9") (pin "19") (pinfunction "2NOE_19") (pintype "bidirectional"))
      (node (ref "OE3_TP") (pin "1") (pinfunction "P$1_1") (pintype "bidirectional"))
      (node (ref "U2") (pin "71") (pinfunction "L21P_2_71") (pintype "bidirectional"))
    )
    (net (code "146") (name "PWR_OE4") (class "Default")
      (node (ref "IC10") (pin "19") (pinfunction "2NOE_19") (pintype "bidirectional"))
      (node (ref "OE4_TP") (pin "1") (pinfunction "P$1_1") (pintype "bidirectional"))
      (node (ref "U2") (pin "72") (pinfunction "L21N_2_72") (pintype "bidirectional"))
    )
    (net (code "147") (name "RELAY_ON") (class "Default")
      (node (ref "IC2") (pin "25") (pinfunction "PC5/ADC12_IN15_25") (pintype "bidirectional"))
      (node (ref "R40") (pin "1") (pinfunction "1_1") (pintype "passive"))
      (node (ref "RELAY_ON_TP") (pin "1") (pinfunction "P$1_1") (pintype "bidirectional"))
    )
    (net (code "148") (name "SCLK{slash}DB0") (class "Default")
      (node (ref "IC2") (pin "21") (pinfunction "PA5/SPI1_SCK/DAC_OUT2/ADC12_IN5_21") (pintype "bidirectional"))
      (node (ref "TP54") (pin "1") (pinfunction "P$1_1") (pintype "bidirectional"))
      (node (ref "U3") (pin "18") (pinfunction "D0/SPI_SCLK/I2C_SCK_18") (pintype "bidirectional"))
    )
    (net (code "149") (name "SDIN{slash}DB1") (class "Default")
      (node (ref "IC2") (pin "22") (pinfunction "PA6/SPI1_MISO/TIM8_BKIN/ADC12_IN6/TIM3_CH1/TIM1_BKIN_22") (pintype "bidirectional"))
      (node (ref "R66") (pin "1") (pinfunction "1_1") (pintype "passive"))
      (node (ref "SJ1") (pin "1") (pinfunction "1_1") (pintype "passive"))
      (node (ref "TP55") (pin "1") (pinfunction "P$1_1") (pintype "bidirectional"))
      (node (ref "U3") (pin "19") (pinfunction "D1/SPI_SDIN/I2C_SDA_19") (pintype "bidirectional"))
    )
    (net (code "150") (name "SD_MISO") (class "Default")
      (node (ref "IC2") (pin "56") (pinfunction "PB4/JNTRST/SPI3_MISO/TIM3_CH1/SPI1_MISO_56") (pintype "input"))
      (node (ref "R62") (pin "1") (pinfunction "1_1") (pintype "passive"))
      (node (ref "TP11") (pin "1") (pinfunction "P$1_1") (pintype "bidirectional"))
      (node (ref "U4") (pin "7") (pinfunction "DO_7") (pintype "bidirectional"))
    )
    (net (code "151") (name "SD_MOSI") (class "Default")
      (node (ref "IC2") (pin "57") (pinfunction "PB5/I2C1_SMBA/SPI3_MOSI/I2S3_SD/TIM3_CH2/SPI1_MOSI_57") (pintype "bidirectional"))
      (node (ref "R63") (pin "1") (pinfunction "1_1") (pintype "passive"))
      (node (ref "TP32") (pin "1") (pinfunction "P$1_1") (pintype "bidirectional"))
      (node (ref "U4") (pin "3") (pinfunction "DI_3") (pintype "bidirectional"))
    )
    (net (code "152") (name "SD_RSV") (class "Default")
      (node (ref "R61") (pin "1") (pinfunction "1_1") (pintype "passive"))
      (node (ref "U4") (pin "8") (pinfunction "RSV_8") (pintype "bidirectional"))
    )
    (net (code "153") (name "SD_SCK{slash}TDO") (class "Default")
      (node (ref "IC2") (pin "55") (pinfunction "PB3/JTDO/SPI3_SCK/I2S3_CK/TIM2_CH2/SPI1_SCK/TRACESWO_55") (pintype "output"))
      (node (ref "JP4") (pin "3") (pinfunction "3_3") (pintype "passive"))
      (node (ref "TP6") (pin "1") (pinfunction "P$1_1") (pintype "bidirectional"))
      (node (ref "U4") (pin "5") (pinfunction "SCK_5") (pintype "bidirectional"))
    )
    (net (code "154") (name "SPCK") (class "Default")
      (node (ref "IC2") (pin "2") (pinfunction "PC13/TAMPER-RTC_2") (pintype "bidirectional"))
      (node (ref "SPCK_TP") (pin "1") (pinfunction "P$1_1") (pintype "bidirectional"))
      (node (ref "U2") (pin "1") (pinfunction "L01P_7/VRN_7_1") (pintype "bidirectional"))
    )
    (net (code "155") (name "SPEAKER") (class "Default")
      (node (ref "IC2") (pin "37") (pinfunction "PC6/I2S2_MCK/TIM8_CH1/SDIO_D6/TIM3_CH1/FT_37") (pintype "bidirectional"))
      (node (ref "R319") (pin "2") (pinfunction "2_2") (pintype "passive"))
    )
    (net (code "156") (name "SSP_CLK") (class "Default")
      (node (ref "IC2") (pin "34") (pinfunction "PB13/SPI2_SCK/I2S2_CK/USART3_CTS/TIM1_CH1N/FT_34") (pintype "bidirectional"))
      (node (ref "TP50") (pin "1") (pinfunction "P$1_1") (pintype "bidirectional"))
      (node (ref "U2") (pin "9") (pinfunction "L23N_7_9") (pintype "bidirectional"))
    )
    (net (code "157") (name "SSP_MISO") (class "Default")
      (node (ref "IC2") (pin "35") (pinfunction "PB14/SPI2_MISO/TIM1_CH2N/USART3_RTS/FT_35") (pintype "bidirectional"))
      (node (ref "TP49") (pin "1") (pinfunction "P$1_1") (pintype "bidirectional"))
      (node (ref "U2") (pin "8") (pinfunction "L23P_7_8") (pintype "bidirectional"))
    )
    (net (code "158") (name "SSP_MOSI") (class "Default")
      (node (ref "IC2") (pin "36") (pinfunction "PB15/SPI2_MOSI/TIM1_CH3N/I2S2_SD/FT_36") (pintype "bidirectional"))
      (node (ref "TP48") (pin "1") (pinfunction "P$1_1") (pintype "bidirectional"))
      (node (ref "U2") (pin "5") (pinfunction "L21N_7_5") (pintype "bidirectional"))
    )
    (net (code "159") (name "SSP_NSS") (class "Default")
      (node (ref "IC2") (pin "33") (pinfunction "PB12/SPI2_NSS/I2C2_WS/I2C2_SMBA/USART3_CK/TIM1_BKIN/FT_33") (pintype "bidirectional"))
      (node (ref "TP51") (pin "1") (pinfunction "P$1_1") (pintype "bidirectional"))
      (node (ref "U2") (pin "4") (pinfunction "L21P_7_4") (pintype "bidirectional"))
    )
    (net (code "160") (name "SW_K1") (class "Default")
      (node (ref "IC2") (pin "62") (pinfunction "PB9/TIM4_CH4/SDIO_D5/I2C1_SDA/CAN_TX/FT_62") (pintype "bidirectional"))
      (node (ref "K1") (pin "2") (pinfunction "S_2") (pintype "passive"))
      (node (ref "R71") (pin "1") (pinfunction "1_1") (pintype "passive"))
    )
    (net (code "161") (name "SW_K2") (class "Default")
      (node (ref "IC2") (pin "17") (pinfunction "PA3/USART2_RX/TIM5_CH4/ADC123_IN3/TIM2_CH4_17") (pintype "bidirectional"))
      (node (ref "K2") (pin "2") (pinfunction "S_2") (pintype "passive"))
      (node (ref "R70") (pin "1") (pinfunction "1_1") (pintype "passive"))
    )
    (net (code "162") (name "SW_K3") (class "Default")
      (node (ref "IC2") (pin "16") (pinfunction "PA2/USART2_TX/TIM5_CH3/ADC123_IN2/TIM2_CH3_16") (pintype "bidirectional"))
      (node (ref "K3") (pin "2") (pinfunction "S_2") (pintype "passive"))
      (node (ref "R69") (pin "1") (pinfunction "1_1") (pintype "passive"))
    )
    (net (code "163") (name "USBD_N") (class "Default")
      (node (ref "D6") (pin "2") (pinfunction "P$2_2") (pintype "passive"))
      (node (ref "R7") (pin "1") (pinfunction "1_1") (pintype "passive"))
      (node (ref "SV1") (pin "2") (pinfunction "D-/2_2") (pintype "bidirectional"))
      (node (ref "USB-MICRO") (pin "D-") (pinfunction "D-_D-") (pintype "bidirectional"))
    )
    (net (code "164") (name "USBD_P") (class "Default")
      (node (ref "D6") (pin "3") (pinfunction "P$3_3") (pintype "passive"))
      (node (ref "R68") (pin "1") (pinfunction "1_1") (pintype "passive"))
      (node (ref "R8") (pin "1") (pinfunction "1_1") (pintype "passive"))
      (node (ref "SV1") (pin "3") (pinfunction "D+/3_3") (pintype "bidirectional"))
      (node (ref "USB-MICRO") (pin "D+") (pinfunction "D+_D+") (pintype "bidirectional"))
    )
    (net (code "165") (name "USB_ON") (class "Default")
      (node (ref "IC2") (pin "29") (pinfunction "PB10/I2C2_SCL/USART3_TX/TIM2_CH3/FT_29") (pintype "bidirectional"))
      (node (ref "R58") (pin "1") (pinfunction "1_1") (pintype "passive"))
      (node (ref "TP23") (pin "1") (pinfunction "P$1_1") (pintype "bidirectional"))
    )
    (net (code "166") (name "VBAT+") (class "Default")
      (node (ref "C61") (pin "1") (pinfunction "1_1") (pintype "passive"))
      (node (ref "C62") (pin "1") (pinfunction "1_1") (pintype "passive"))
      (node (ref "C76") (pin "1") (pinfunction "1_1") (pintype "passive"))
      (node (ref "IC1") (pin "5") (pinfunction "VIN_5") (pintype "input"))
      (node (ref "JP2") (pin "3") (pinfunction "3_3") (pintype "passive"))
      (node (ref "L2") (pin "P$1") (pinfunction "1_P$1") (pintype "passive"))
      (node (ref "R55") (pin "2") (pinfunction "2_2") (pintype "passive"))
      (node (ref "S1") (pin "3") (pinfunction "S_3") (pintype "passive"))
      (node (ref "TP9") (pin "1") (pinfunction "P$1_1") (pintype "bidirectional"))
      (node (ref "U$7") (pin "8") (pinfunction "BAT_8") (pintype "bidirectional"))
      (node (ref "U$9") (pin "3") (pinfunction "POS_3") (pintype "power_in"))
    )
    (net (code "167") (name "VBUS") (class "Default")
      (node (ref "C1") (pin "1") (pinfunction "1_1") (pintype "passive"))
      (node (ref "C59") (pin "1") (pinfunction "1_1") (pintype "passive"))
      (node (ref "LED1") (pin "A") (pinfunction "A_A") (pintype "passive"))
      (node (ref "LED2") (pin "A") (pinfunction "A_A") (pintype "passive"))
      (node (ref "R56") (pin "1") (pinfunction "1_1") (pintype "passive"))
      (node (ref "TP8") (pin "1") (pinfunction "P$1_1") (pintype "bidirectional"))
      (node (ref "U$7") (pin "1") (pinfunction "VIN_1") (pintype "bidirectional"))
      (node (ref "U1") (pin "2") (pinfunction "B_2") (pintype "bidirectional"))
    )
    (net (code "168") (name "VDD") (class "Default")
      (node (ref "C21") (pin "1") (pinfunction "1_1") (pintype "passive"))
      (node (ref "C22") (pin "1") (pinfunction "1_1") (pintype "passive"))
      (node (ref "C23") (pin "1") (pinfunction "1_1") (pintype "passive"))
      (node (ref "C24") (pin "1") (pinfunction "1_1") (pintype "passive"))
      (node (ref "C37") (pin "+") (pinfunction "+_+") (pintype "passive"))
      (node (ref "C38") (pin "+") (pinfunction "+_+") (pintype "passive"))
      (node (ref "C44") (pin "1") (pinfunction "1_1") (pintype "passive"))
      (node (ref "C46") (pin "1") (pinfunction "1_1") (pintype "passive"))
      (node (ref "C64") (pin "1") (pinfunction "1_1") (pintype "passive"))
      (node (ref "C71") (pin "1") (pinfunction "1_1") (pintype "passive"))
      (node (ref "C72") (pin "1") (pinfunction "1_1") (pintype "passive"))
      (node (ref "C73") (pin "+") (pinfunction "+_+") (pintype "passive"))
      (node (ref "D7") (pin "3") (pinfunction "C_3") (pintype "passive"))
      (node (ref "FB1") (pin "2") (pinfunction "B_2") (pintype "bidirectional"))
      (node (ref "FB2\\") (pin "2") (pinfunction "B_2") (pintype "bidirectional"))
      (node (ref "FB3") (pin "2") (pinfunction "B_2") (pintype "bidirectional"))
      (node (ref "IC1") (pin "10") (pinfunction "FB_10") (pintype "input"))
      (node (ref "IC1") (pin "2") (pinfunction "VOUT_2") (pintype "output"))
      (node (ref "IC10") (pin "20") (pinfunction "VDD_20") (pintype "bidirectional"))
      (node (ref "IC105") (pin "1") (pinfunction "VIN_1") (pintype "bidirectional"))
      (node (ref "IC106") (pin "1") (pinfunction "VIN_1") (pintype "bidirectional"))
      (node (ref "IC11") (pin "14") (pinfunction "VDD_14") (pintype "bidirectional"))
      (node (ref "IC13") (pin "1") (pinfunction "VIN_1") (pintype "bidirectional"))
      (node (ref "IC14") (pin "8") (pinfunction "V+_8") (pintype "bidirectional"))
      (node (ref "IC3") (pin "1") (pinfunction "VIN_1") (pintype "bidirectional"))
      (node (ref "IC3") (pin "3") (pinfunction "VC_3") (pintype "bidirectional"))
      (node (ref "IC5") (pin "8") (pinfunction "V+_8") (pintype "bidirectional"))
      (node (ref "IC6") (pin "4") (pinfunction "V+_4") (pintype "bidirectional"))
      (node (ref "IC8") (pin "11") (pinfunction "VDDD0_11") (pintype "bidirectional"))
      (node (ref "IC8") (pin "13") (pinfunction "VDDD1_13") (pintype "bidirectional"))
      (node (ref "IC9") (pin "20") (pinfunction "VDD_20") (pintype "bidirectional"))
      (node (ref "R47") (pin "1") (pinfunction "1_1") (pintype "passive"))
      (node (ref "R52") (pin "2") (pinfunction "2_2") (pintype "passive"))
      (node (ref "R9") (pin "2") (pinfunction "2_2") (pintype "passive"))
      (node (ref "RLY1") (pin "1") (pinfunction "P$1_1") (pintype "passive"))
      (node (ref "TP10") (pin "1") (pinfunction "P$1_1") (pintype "bidirectional"))
    )
    (net (code "169") (name "VDDA") (class "Default")
      (node (ref "C52") (pin "1") (pinfunction "1_1") (pintype "passive"))
      (node (ref "C55") (pin "A") (pinfunction "+_A") (pintype "passive"))
      (node (ref "IC2") (pin "13") (pinfunction "VDDA_13") (pintype "power_in"))
      (node (ref "L1") (pin "2") (pinfunction "P$2_2") (pintype "bidirectional"))
    )
    (net (code "170") (name "VMID") (class "Default")
      (node (ref "C10") (pin "1") (pinfunction "1_1") (pintype "passive"))
      (node (ref "C45") (pin "1") (pinfunction "1_1") (pintype "passive"))
      (node (ref "IC6") (pin "1") (pinfunction "OUT_1") (pintype "output"))
      (node (ref "IC6") (pin "2") (pinfunction "-IN_2") (pintype "input"))
      (node (ref "R12") (pin "1") (pinfunction "1_1") (pintype "passive"))
      (node (ref "R13") (pin "1") (pinfunction "1_1") (pintype "passive"))
      (node (ref "R17") (pin "1") (pinfunction "1_1") (pintype "passive"))
      (node (ref "R19") (pin "1") (pinfunction "1_1") (pintype "passive"))
      (node (ref "R36") (pin "1") (pinfunction "1_1") (pintype "passive"))
      (node (ref "R38") (pin "1") (pinfunction "1_1") (pintype "passive"))
      (node (ref "R48") (pin "1") (pinfunction "1_1") (pintype "passive"))
      (node (ref "R49") (pin "1") (pinfunction "1_1") (pintype "passive"))
      (node (ref "R50") (pin "1") (pinfunction "1_1") (pintype "passive"))
      (node (ref "R51") (pin "1") (pinfunction "1_1") (pintype "passive"))
    )
    (net (code "171") (name "unconnected-(IC2-PC0{slash}ADC123_IN10-Pad8)") (class "Default")
      (node (ref "IC2") (pin "8") (pinfunction "PC0/ADC123_IN10_8") (pintype "bidirectional"))
    )
    (net (code "172") (name "unconnected-(IC2-PC1{slash}ADC123_IN11-Pad9)") (class "Default")
      (node (ref "IC2") (pin "9") (pinfunction "PC1/ADC123_IN11_9") (pintype "bidirectional"))
    )
    (net (code "173") (name "unconnected-(IC2-PC2{slash}ADC123_IN12-Pad10)") (class "Default")
      (node (ref "IC2") (pin "10") (pinfunction "PC2/ADC123_IN12_10") (pintype "bidirectional"))
    )
    (net (code "174") (name "unconnected-(IC2-PC10{slash}UART4_TX{slash}SDIO_D2{slash}USART3_TX{slash}FT-Pad51)") (class "Default")
      (node (ref "IC2") (pin "51") (pinfunction "PC10/UART4_TX/SDIO_D2/USART3_TX/FT_51") (pintype "bidirectional"))
    )
    (net (code "175") (name "unconnected-(IC6D-OUT-Pad14)") (class "Default")
      (node (ref "IC6") (pin "14") (pinfunction "OUT_14") (pintype "output"))
    )
    (net (code "176") (name "unconnected-(IC8-REFBS-Pad22)") (class "Default")
      (node (ref "IC8") (pin "22") (pinfunction "REFBS_22") (pintype "bidirectional"))
    )
    (net (code "177") (name "unconnected-(IC8-REFTS-Pad16)") (class "Default")
      (node (ref "IC8") (pin "16") (pinfunction "REFTS_16") (pintype "bidirectional"))
    )
    (net (code "178") (name "unconnected-(IC105-NR-Pad4)") (class "Default")
      (node (ref "IC105") (pin "4") (pinfunction "NR_4") (pintype "bidirectional"))
    )
    (net (code "179") (name "unconnected-(IC106-NR-Pad4)") (class "Default")
      (node (ref "IC106") (pin "4") (pinfunction "NR_4") (pintype "bidirectional"))
    )
    (net (code "180") (name "unconnected-(SV1-ID{slash}4-Pad4)") (class "Default")
      (node (ref "SV1") (pin "4") (pinfunction "ID/4_4") (pintype "bidirectional"))
    )
    (net (code "181") (name "unconnected-(U2A-IO0_3-Pad55)") (class "Default")
      (node (ref "U2") (pin "55") (pinfunction "IO0_3_55") (pintype "bidirectional"))
    )
    (net (code "182") (name "unconnected-(U2A-IO0_6-Pad17)") (class "Default")
      (node (ref "U2") (pin "17") (pinfunction "IO0_6_17") (pintype "bidirectional"))
    )
    (net (code "183") (name "unconnected-(U2A-IO1_3-Pad59)") (class "Default")
      (node (ref "U2") (pin "59") (pinfunction "IO1_3_59") (pintype "bidirectional"))
    )
    (net (code "184") (name "unconnected-(U2A-IO1_6-Pad21)") (class "Default")
      (node (ref "U2") (pin "21") (pinfunction "IO1_6_21") (pintype "bidirectional"))
    )
    (net (code "185") (name "unconnected-(U2A-IO_1-Pad81)") (class "Default")
      (node (ref "U2") (pin "81") (pinfunction "IO_1_81") (pintype "bidirectional"))
    )
    (net (code "186") (name "unconnected-(U2A-L01N_0{slash}VRP_0-Pad97)") (class "Default")
      (node (ref "U2") (pin "97") (pinfunction "L01N_0/VRP_0_97") (pintype "bidirectional"))
    )
    (net (code "187") (name "unconnected-(U2A-L01N_1{slash}VRP_1-Pad80)") (class "Default")
      (node (ref "U2") (pin "80") (pinfunction "L01N_1/VRP_1_80") (pintype "bidirectional"))
    )
    (net (code "188") (name "unconnected-(U2A-L01N_3{slash}VRP_3-Pad54)") (class "Default")
      (node (ref "U2") (pin "54") (pinfunction "L01N_3/VRP_3_54") (pintype "bidirectional"))
    )
    (net (code "189") (name "unconnected-(U2A-L01N_6{slash}VRP_6-Pad23)") (class "Default")
      (node (ref "U2") (pin "23") (pinfunction "L01N_6/VRP_6_23") (pintype "bidirectional"))
    )
    (net (code "190") (name "unconnected-(U2A-L01N_7{slash}VRP_7-Pad2)") (class "Default")
      (node (ref "U2") (pin "2") (pinfunction "L01N_7/VRP_7_2") (pintype "bidirectional"))
    )
    (net (code "191") (name "unconnected-(U2A-L01P_0{slash}VRN_0-Pad96)") (class "Default")
      (node (ref "U2") (pin "96") (pinfunction "L01P_0/VRN_0_96") (pintype "bidirectional"))
    )
    (net (code "192") (name "unconnected-(U2A-L01P_1{slash}VRN_1-Pad79)") (class "Default")
      (node (ref "U2") (pin "79") (pinfunction "L01P_1/VRN_1_79") (pintype "bidirectional"))
    )
    (net (code "193") (name "unconnected-(U2A-L01P_2{slash}VRN_2-Pad74)") (class "Default")
      (node (ref "U2") (pin "74") (pinfunction "L01P_2/VRN_2_74") (pintype "bidirectional"))
    )
    (net (code "194") (name "unconnected-(U2A-L01P_3{slash}VRN_3-Pad53)") (class "Default")
      (node (ref "U2") (pin "53") (pinfunction "L01P_3/VRN_3_53") (pintype "bidirectional"))
    )
    (net (code "195") (name "unconnected-(U2A-L01P_6{slash}VRN_6-Pad22)") (class "Default")
      (node (ref "U2") (pin "22") (pinfunction "L01P_6/VRN_6_22") (pintype "bidirectional"))
    )
    (net (code "196") (name "unconnected-(U2A-L24N_2-Pad68)") (class "Default")
      (node (ref "U2") (pin "68") (pinfunction "L24N_2_68") (pintype "bidirectional"))
    )
    (net (code "197") (name "unconnected-(U2A-L24N_6{slash}VREF_6-Pad16)") (class "Default")
      (node (ref "U2") (pin "16") (pinfunction "L24N_6/VREF_6_16") (pintype "bidirectional"))
    )
    (net (code "198") (name "unconnected-(U2A-L24P_2-Pad67)") (class "Default")
      (node (ref "U2") (pin "67") (pinfunction "L24P_2_67") (pintype "bidirectional"))
    )
    (net (code "199") (name "unconnected-(U2A-L24P_3-Pad60)") (class "Default")
      (node (ref "U2") (pin "60") (pinfunction "L24P_3_60") (pintype "bidirectional"))
    )
    (net (code "200") (name "unconnected-(U2A-L31N_0-Pad92)") (class "Default")
      (node (ref "U2") (pin "92") (pinfunction "L31N_0_92") (pintype "bidirectional"))
    )
    (net (code "201") (name "unconnected-(U2A-L31N_1{slash}VREF_1-Pad86)") (class "Default")
      (node (ref "U2") (pin "86") (pinfunction "L31N_1/VREF_1_86") (pintype "bidirectional"))
    )
    (net (code "202") (name "unconnected-(U2A-L31P_0{slash}VREF_0-Pad91)") (class "Default")
      (node (ref "U2") (pin "91") (pinfunction "L31P_0/VREF_0_91") (pintype "bidirectional"))
    )
    (net (code "203") (name "unconnected-(U2A-L31P_1-Pad85)") (class "Default")
      (node (ref "U2") (pin "85") (pinfunction "L31P_1_85") (pintype "bidirectional"))
    )
    (net (code "204") (name "unconnected-(U2A-L32N_4{slash}GCLK1-Pad39)") (class "Default")
      (node (ref "U2") (pin "39") (pinfunction "L32N_4/GCLK1_39") (pintype "bidirectional"))
    )
    (net (code "205") (name "unconnected-(U2A-L32P_1{slash}GCLK4-Pad87)") (class "Default")
      (node (ref "U2") (pin "87") (pinfunction "L32P_1/GCLK4_87") (pintype "bidirectional"))
    )
    (net (code "206") (name "unconnected-(U2A-L40N_3{slash}VREF_3-Pad63)") (class "Default")
      (node (ref "U2") (pin "63") (pinfunction "L40N_3/VREF_3_63") (pintype "bidirectional"))
    )
    (net (code "207") (name "unconnected-(U2A-L40N_7{slash}VREF_7-Pad12)") (class "Default")
      (node (ref "U2") (pin "12") (pinfunction "L40N_7/VREF_7_12") (pintype "bidirectional"))
    )
    (net (code "208") (name "unconnected-(U2A-L40P_6{slash}VREF_6-Pad13)") (class "Default")
      (node (ref "U2") (pin "13") (pinfunction "L40P_6/VREF_6_13") (pintype "bidirectional"))
    )
    (net (code "209") (name "unconnected-(U2A-L40P_7-Pad11)") (class "Default")
      (node (ref "U2") (pin "11") (pinfunction "L40P_7_11") (pintype "bidirectional"))
    )
    (net (code "210") (name "unconnected-(U2B-HSWAP_EN-Pad98)") (class "Default")
      (node (ref "U2") (pin "98") (pinfunction "HSWAP_EN_98") (pintype "bidirectional"))
    )
    (net (code "211") (name "unconnected-(U2B-M0-Pad25)") (class "Default")
      (node (ref "U2") (pin "25") (pinfunction "M0_25") (pintype "bidirectional"))
    )
    (net (code "212") (name "unconnected-(U2B-M1-Pad24)") (class "Default")
      (node (ref "U2") (pin "24") (pinfunction "M1_24") (pintype "bidirectional"))
    )
    (net (code "213") (name "unconnected-(U2B-M2-Pad26)") (class "Default")
      (node (ref "U2") (pin "26") (pinfunction "M2_26") (pintype "bidirectional"))
    )
    (net (code "214") (name "unconnected-(U3-D3-Pad21)") (class "Default")
      (node (ref "U3") (pin "21") (pinfunction "D3_21") (pintype "bidirectional"))
    )
    (net (code "215") (name "unconnected-(U3-D4-Pad22)") (class "Default")
      (node (ref "U3") (pin "22") (pinfunction "D4_22") (pintype "bidirectional"))
    )
    (net (code "216") (name "unconnected-(U3-D5-Pad23)") (class "Default")
      (node (ref "U3") (pin "23") (pinfunction "D5_23") (pintype "bidirectional"))
    )
    (net (code "217") (name "unconnected-(U3-D6-Pad24)") (class "Default")
      (node (ref "U3") (pin "24") (pinfunction "D6_24") (pintype "bidirectional"))
    )
    (net (code "218") (name "unconnected-(U3-D7-Pad25)") (class "Default")
      (node (ref "U3") (pin "25") (pinfunction "D7_25") (pintype "bidirectional"))
    )
    (net (code "219") (name "unconnected-(U3-E{slash}RD-Pad17)") (class "Default")
      (node (ref "U3") (pin "17") (pinfunction "E/RD_17") (pintype "input"))
    )
    (net (code "220") (name "unconnected-(U3-NC-Pad7)") (class "Default")
      (node (ref "U3") (pin "7") (pinfunction "NC_7") (pintype "no_connect"))
    )
    (net (code "221") (name "unconnected-(U3-R{slash}W-Pad16)") (class "Default")
      (node (ref "U3") (pin "16") (pinfunction "R/W_16") (pintype "input"))
    )
    (net (code "222") (name "unconnected-(U4-NC-Pad1)") (class "Default")
      (node (ref "U4") (pin "1") (pinfunction "NC_1") (pintype "bidirectional"))
    )
    (net (code "223") (name "~{OLED_CS}") (class "Default")
      (node (ref "IC2") (pin "20") (pinfunction "PA4/SPI1_NSS/USART2_CK/DAC_OUT1/ADC12_IN4_20") (pintype "bidirectional"))
      (node (ref "TP28") (pin "1") (pinfunction "P$1_1") (pintype "bidirectional"))
      (node (ref "U3") (pin "13") (pinfunction "/CS_13") (pintype "input"))
    )
    (net (code "224") (name "~{RES}") (class "Default")
      (node (ref "IC2") (pin "61") (pinfunction "PB8/TIM4_CH3/SDIO_D4/I2C1_SCL/CAN_RX/FT_61") (pintype "bidirectional"))
      (node (ref "TP29") (pin "1") (pinfunction "P$1_1") (pintype "bidirectional"))
      (node (ref "U3") (pin "14") (pinfunction "/RES_14") (pintype "input"))
    )
    (net (code "225") (name "~{SD_CS{slash}JTAG_TDI}") (class "Default")
      (node (ref "IC2") (pin "50") (pinfunction "PA15/JTDI/SPI3_NSS/I2S3_WS/TIM2_CH1_ETR/SPI1_NSS_50") (pintype "input"))
      (node (ref "JP4") (pin "2") (pinfunction "2_2") (pintype "passive"))
      (node (ref "R64") (pin "1") (pinfunction "1_1") (pintype "passive"))
      (node (ref "U4") (pin "2") (pinfunction "CS_2") (pintype "bidirectional"))
    )
  )
)
